# Replicape_B4.net
KiCad netlist of a schematic drawn in EAGLE
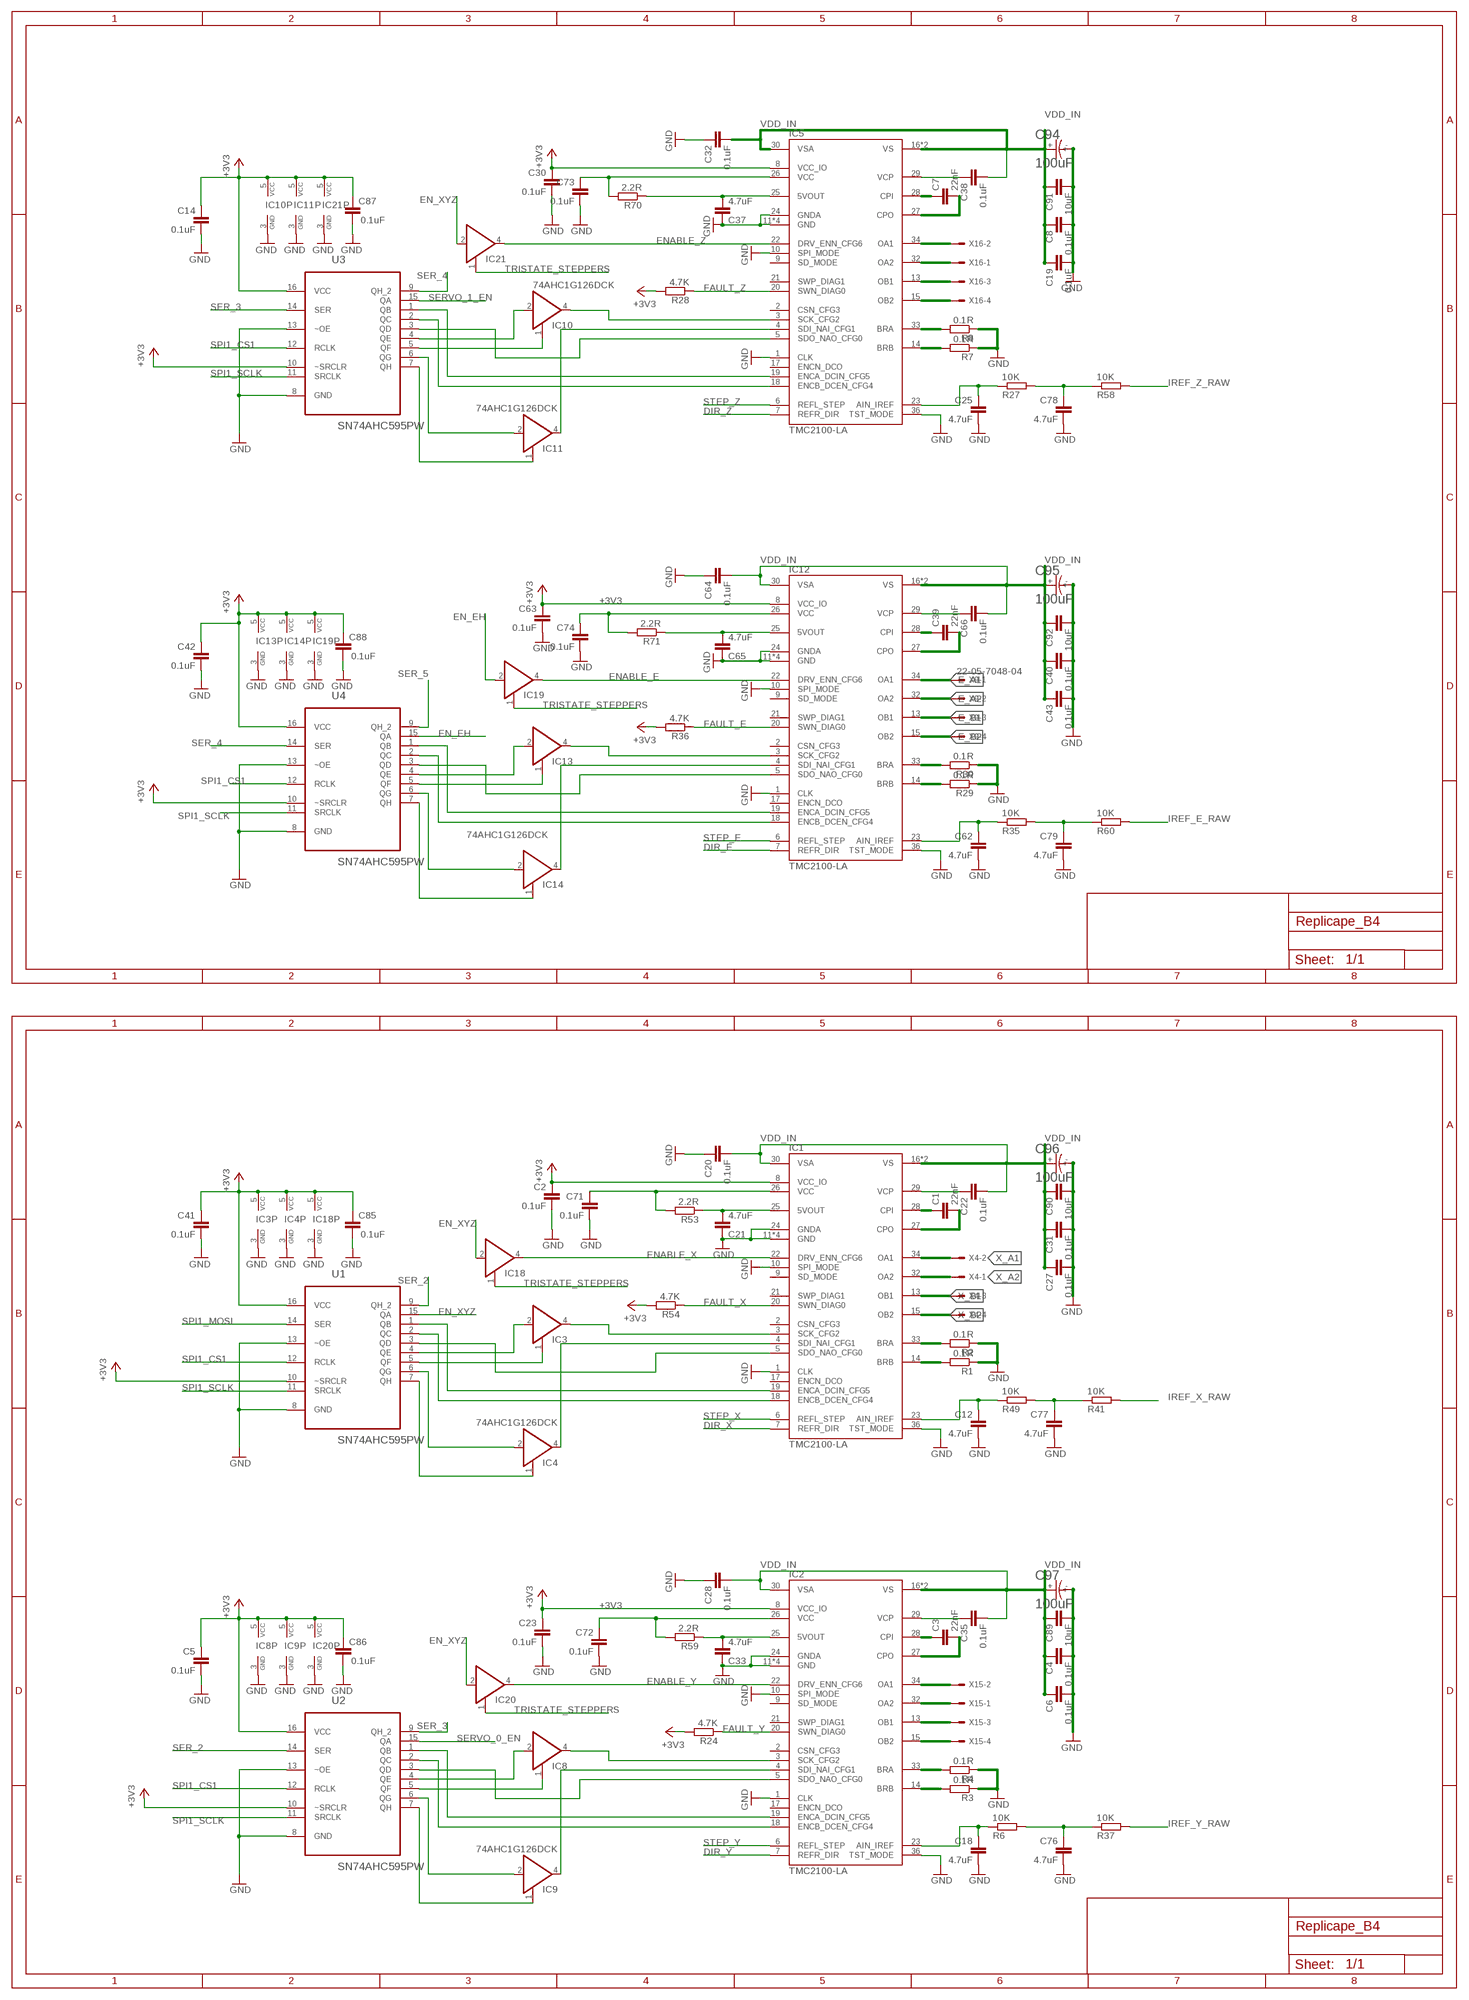
[diagram p0: schematic, sheet 1, part 1 of 3]
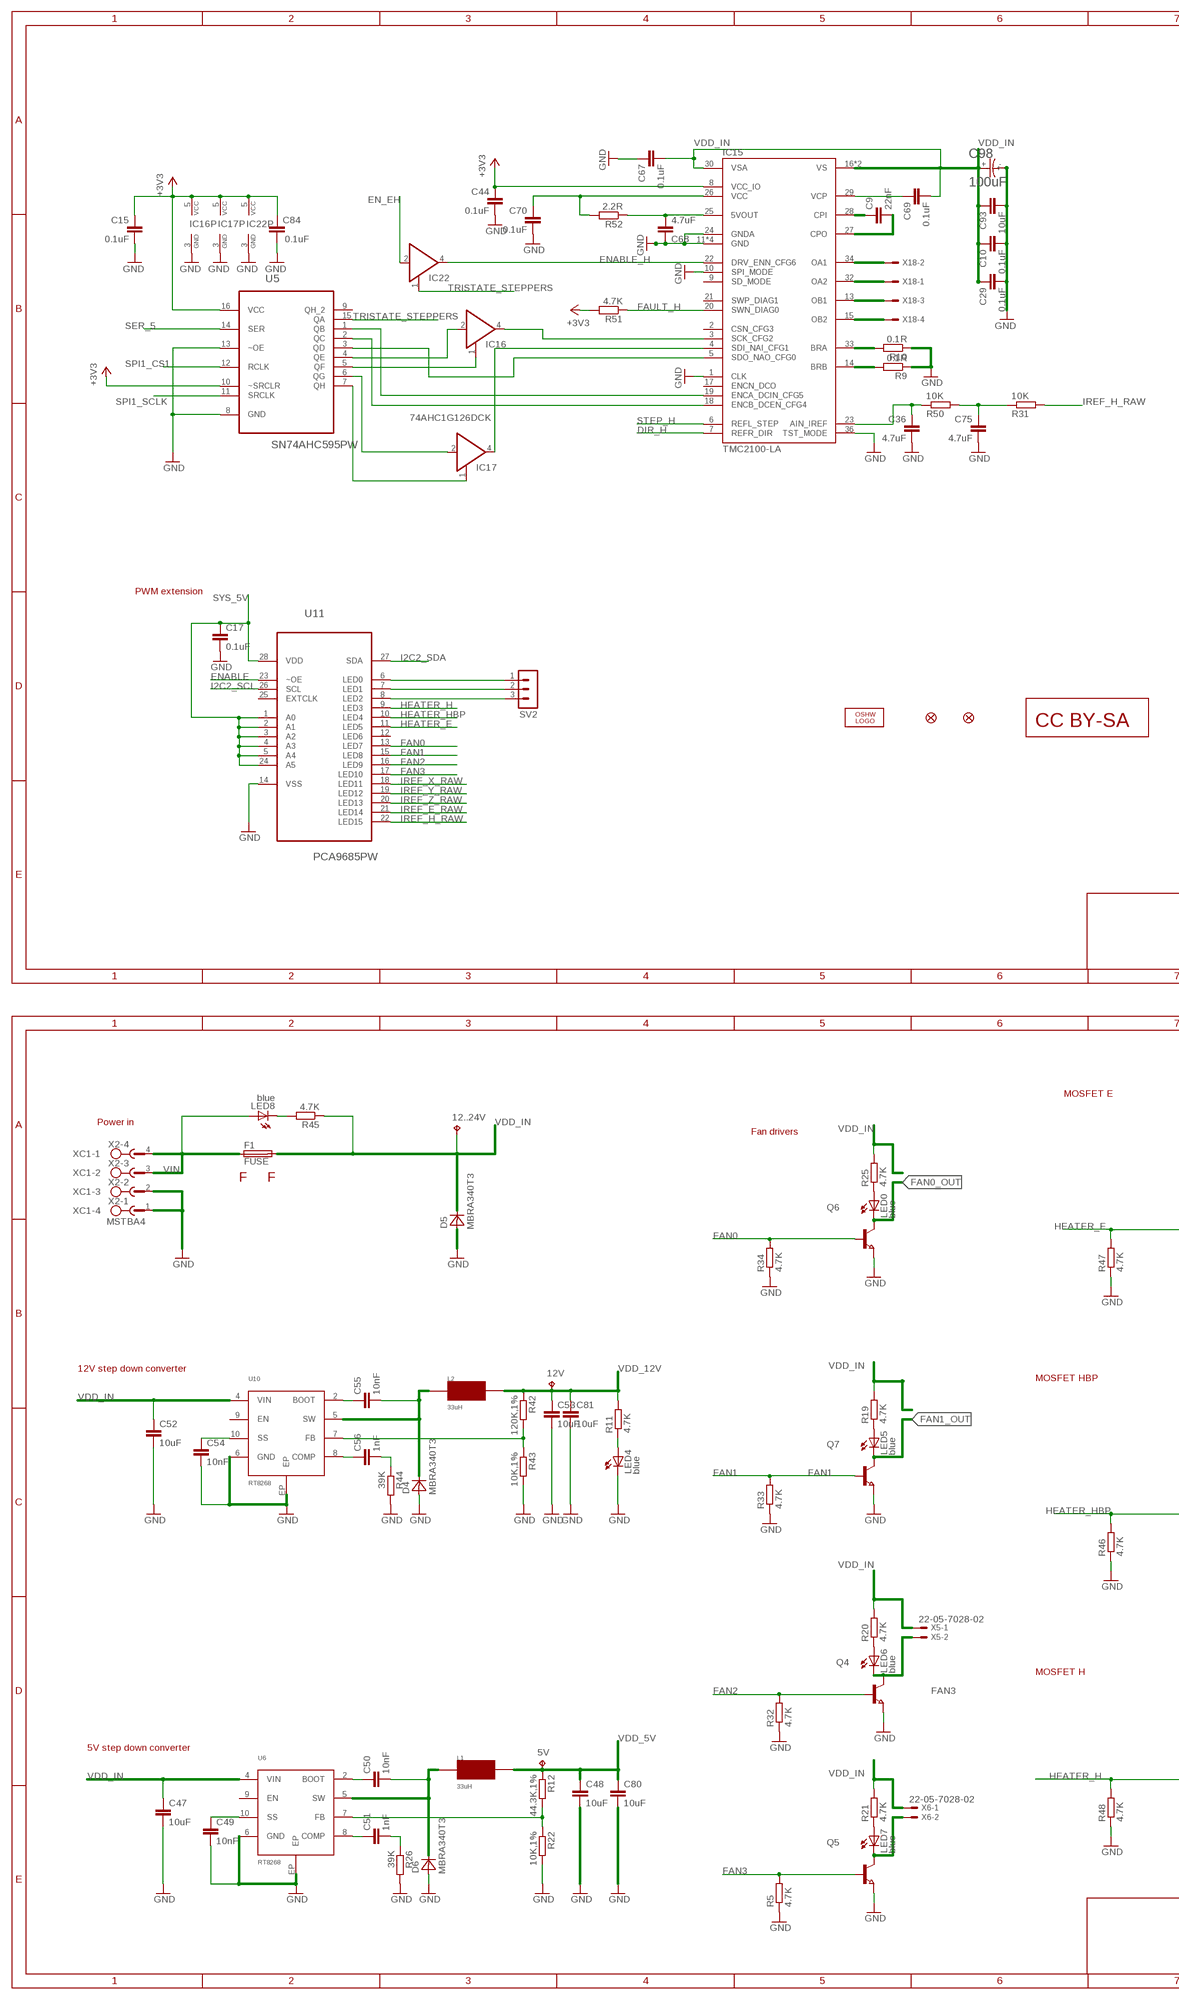
[diagram p1: schematic, sheet 1, part 2 of 3]
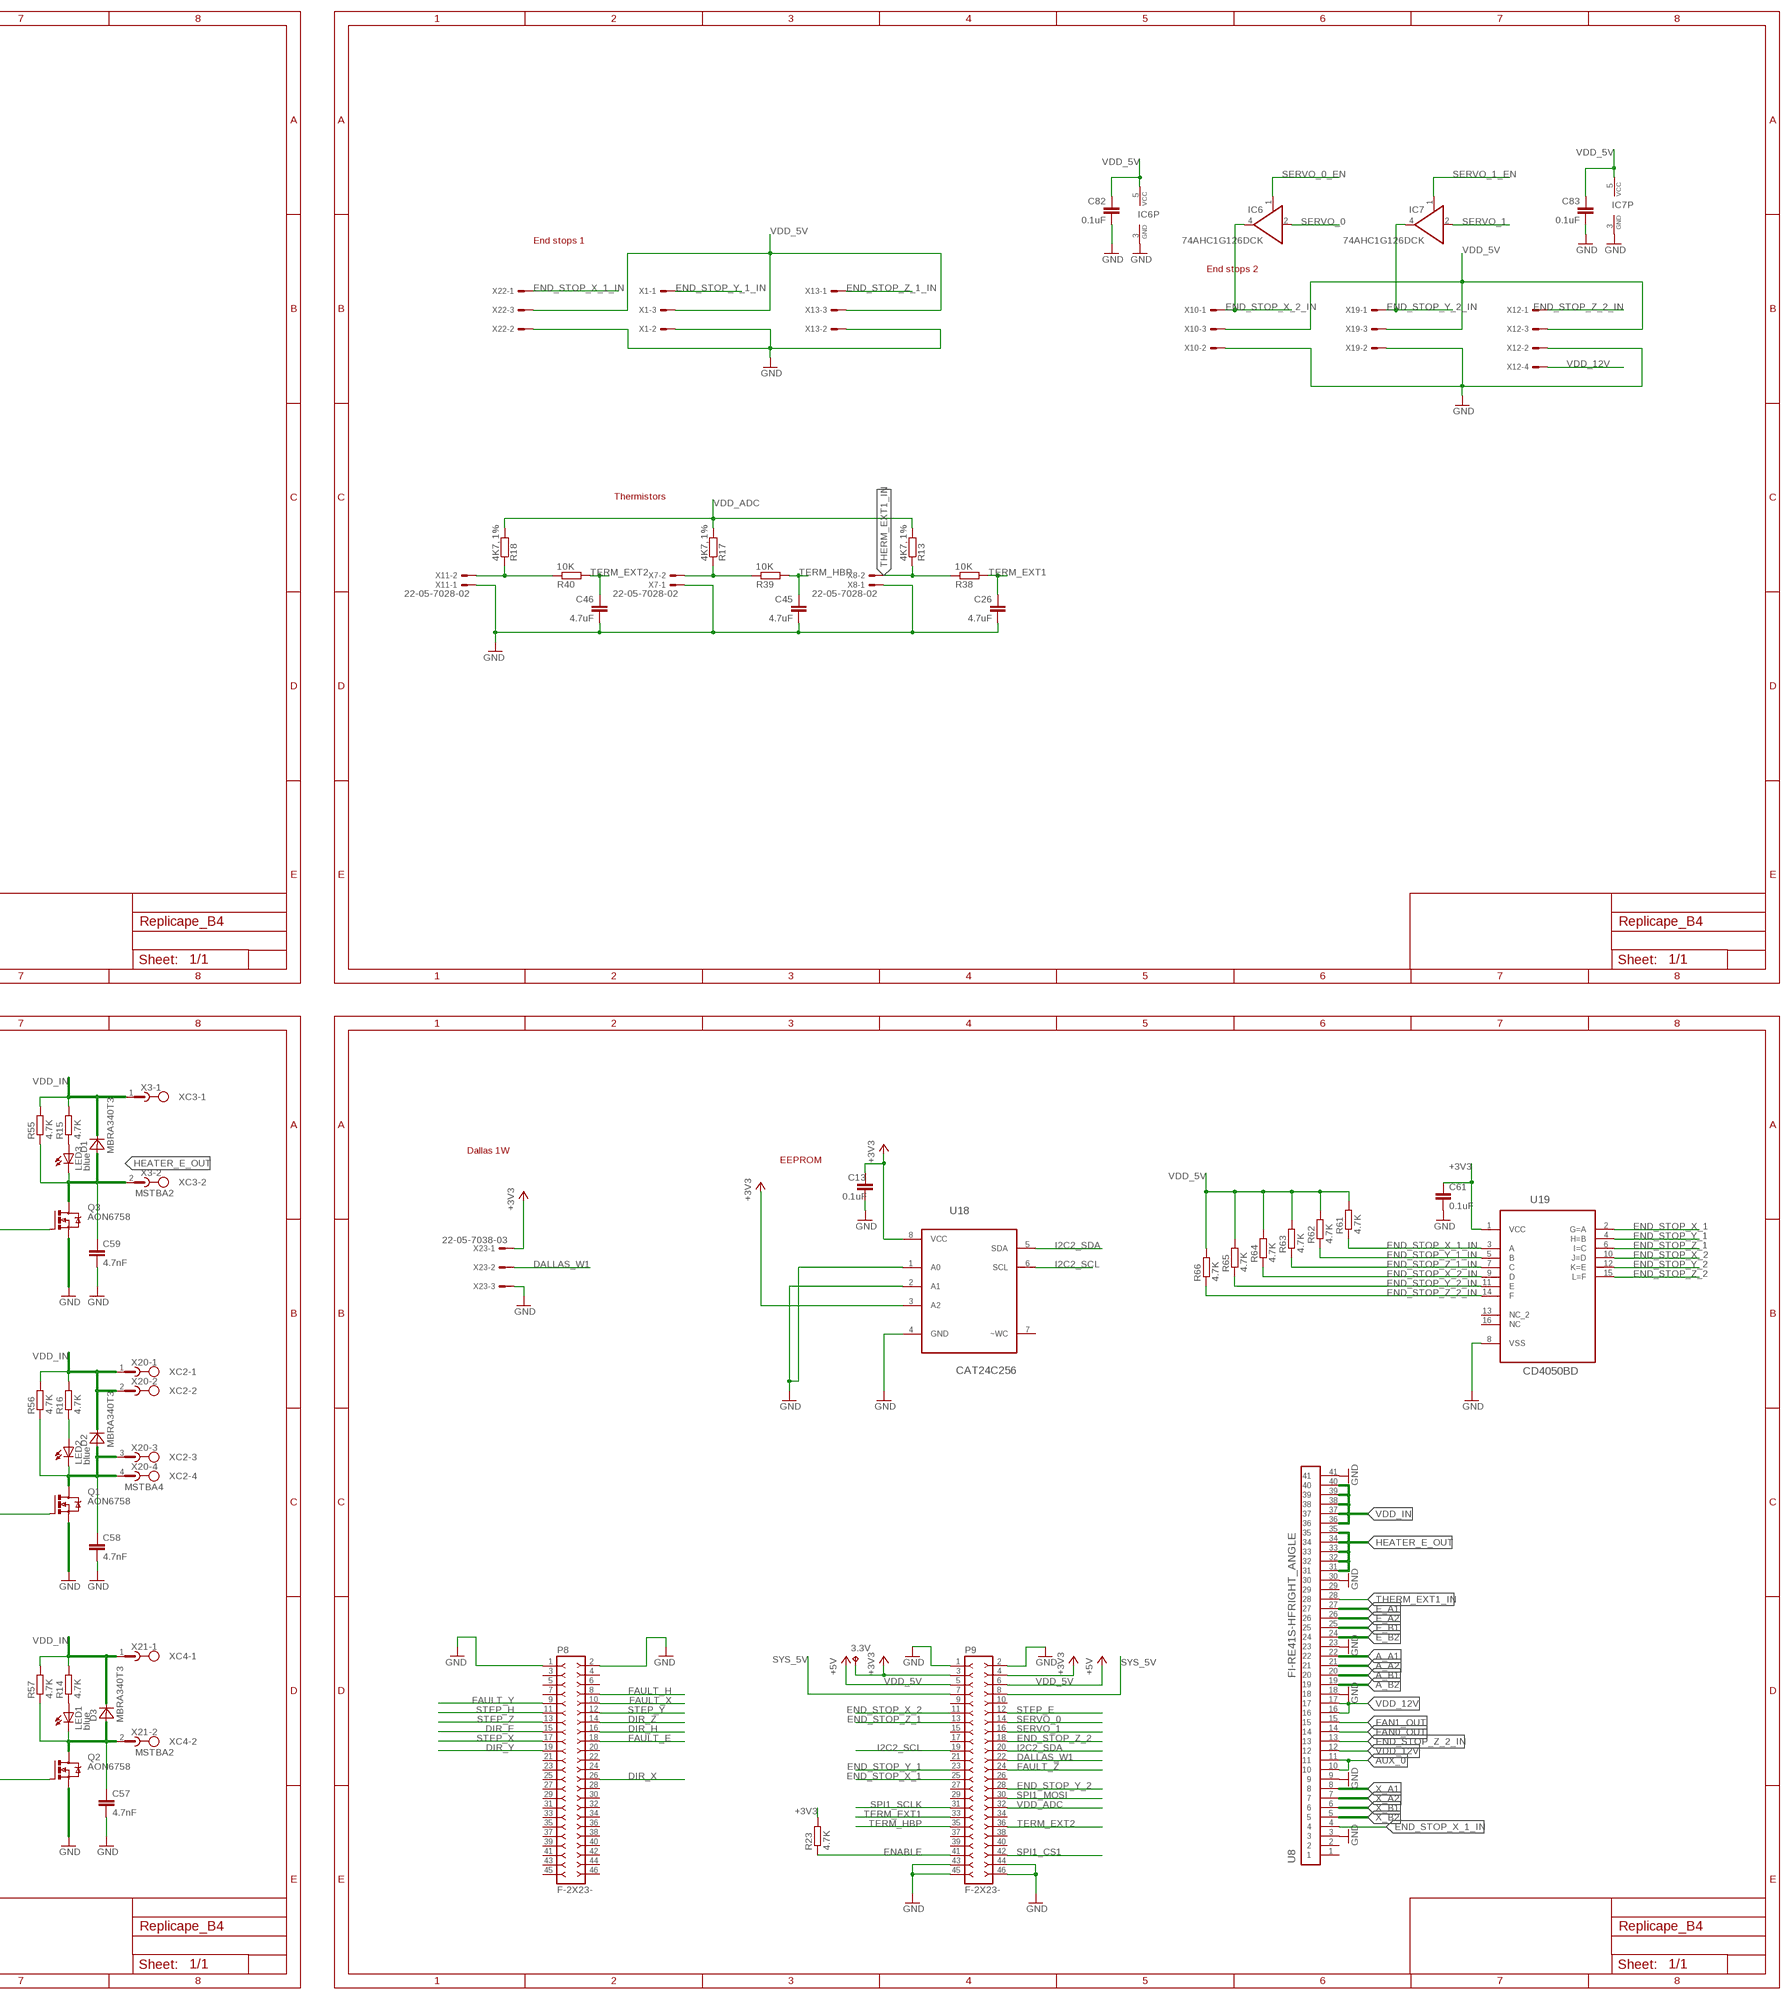
[diagram p2: schematic, sheet 1, part 3 of 3]

(export (version "E")
  (design (tool "Eeschema 10.0.6"))
  (components
    (comp (ref "3.3V")
      (value "TPB1,27")
      (footprint "eagle-import:B1,27")
      (libsource (lib "eagle-import") (part "TPB1,27"))
    )
    (comp (ref "5V")
      (value "TPB1,27")
      (footprint "eagle-import:B1,27")
      (libsource (lib "eagle-import") (part "TPB1,27"))
    )
    (comp (ref "12..24V")
      (value "TPB1,27")
      (footprint "eagle-import:B1,27")
      (libsource (lib "eagle-import") (part "TPB1,27"))
    )
    (comp (ref "12V")
      (value "TPB1,27")
      (footprint "eagle-import:B1,27")
      (libsource (lib "eagle-import") (part "TPB1,27"))
    )
    (comp (ref "C1")
      (value "22nF")
      (footprint "eagle-import:C0402")
      (fields (field (name "MPN") "C1005X7R1E223K050BB"))
      (libsource (lib "eagle-import") (part "C-EUC0402"))
    )
    (comp (ref "C2")
      (value "0.1uF")
      (footprint "eagle-import:C0402")
      (fields (field (name "MPN") "CL10B104KB8NNND"))
      (libsource (lib "eagle-import") (part "C-EUC0402"))
    )
    (comp (ref "C3")
      (value "22nF")
      (footprint "eagle-import:C0402")
      (fields (field (name "MPN") "C1005X7R1E223K050BB"))
      (libsource (lib "eagle-import") (part "C-EUC0402"))
    )
    (comp (ref "C4")
      (value "0.1uF")
      (footprint "eagle-import:C0402")
      (fields (field (name "MPN") "CL10B104KB8NNND"))
      (libsource (lib "eagle-import") (part "C-EUC0402"))
    )
    (comp (ref "C5")
      (value "0.1uF")
      (footprint "eagle-import:C0402")
      (fields (field (name "MPN") "CL10B104KB8NNND"))
      (libsource (lib "eagle-import") (part "C-EUC0402"))
    )
    (comp (ref "C6")
      (value "0.1uF")
      (footprint "eagle-import:C0402")
      (fields (field (name "MPN") "CL10B104KB8NNND"))
      (libsource (lib "eagle-import") (part "C-EUC0402"))
    )
    (comp (ref "C7")
      (value "22nF")
      (footprint "eagle-import:C0402")
      (fields (field (name "MPN") "C1005X7R1E223K050BB"))
      (libsource (lib "eagle-import") (part "C-EUC0402"))
    )
    (comp (ref "C8")
      (value "0.1uF")
      (footprint "eagle-import:C0402")
      (fields (field (name "MPN") "CL10B104KB8NNND"))
      (libsource (lib "eagle-import") (part "C-EUC0402"))
    )
    (comp (ref "C9")
      (value "22nF")
      (footprint "eagle-import:C0402")
      (fields (field (name "MPN") "C1005X7R1E223K050BB"))
      (libsource (lib "eagle-import") (part "C-EUC0402"))
    )
    (comp (ref "C10")
      (value "0.1uF")
      (footprint "eagle-import:C0402")
      (fields (field (name "MPN") "CL10B104KB8NNND"))
      (libsource (lib "eagle-import") (part "C-EUC0402"))
    )
    (comp (ref "C12")
      (value "4.7uF")
      (footprint "eagle-import:C0402")
      (fields (field (name "MPN") "GRM155R60J475ME47D"))
      (libsource (lib "eagle-import") (part "C-EUC0402"))
    )
    (comp (ref "C13")
      (value "0.1uF")
      (footprint "eagle-import:C0402")
      (fields (field (name "MPN") "CL10B104KB8NNND"))
      (libsource (lib "eagle-import") (part "C-EUC0402"))
    )
    (comp (ref "C14")
      (value "0.1uF")
      (footprint "eagle-import:C0402")
      (fields (field (name "MPN") "CL10B104KB8NNND"))
      (libsource (lib "eagle-import") (part "C-EUC0402"))
    )
    (comp (ref "C15")
      (value "0.1uF")
      (footprint "eagle-import:C0402")
      (fields (field (name "MPN") "CL10B104KB8NNND"))
      (libsource (lib "eagle-import") (part "C-EUC0402"))
    )
    (comp (ref "C17")
      (value "0.1uF")
      (footprint "eagle-import:C0402")
      (fields (field (name "MPN") "CL10B104KB8NNND"))
      (libsource (lib "eagle-import") (part "C-EUC0402"))
    )
    (comp (ref "C18")
      (value "4.7uF")
      (footprint "eagle-import:C0402")
      (fields (field (name "MPN") "GRM155R60J475ME47D"))
      (libsource (lib "eagle-import") (part "C-EUC0402"))
    )
    (comp (ref "C19")
      (value "0.1uF")
      (footprint "eagle-import:C0402")
      (fields (field (name "MPN") "CL10B104KB8NNND"))
      (libsource (lib "eagle-import") (part "C-EUC0402"))
    )
    (comp (ref "C20")
      (value "0.1uF")
      (footprint "eagle-import:C0402")
      (fields (field (name "MPN") "CL10B104KB8NNND"))
      (libsource (lib "eagle-import") (part "C-EUC0402"))
    )
    (comp (ref "C21")
      (value "4.7uF")
      (footprint "eagle-import:C0402")
      (fields (field (name "MPN") "GRM155R60J475ME47D"))
      (libsource (lib "eagle-import") (part "C-EUC0402"))
    )
    (comp (ref "C22")
      (value "0.1uF")
      (footprint "eagle-import:C0402")
      (fields (field (name "MPN") "CL10B104KB8NNND"))
      (libsource (lib "eagle-import") (part "C-EUC0402"))
    )
    (comp (ref "C23")
      (value "0.1uF")
      (footprint "eagle-import:C0402")
      (fields (field (name "MPN") "CL10B104KB8NNND"))
      (libsource (lib "eagle-import") (part "C-EUC0402"))
    )
    (comp (ref "C25")
      (value "4.7uF")
      (footprint "eagle-import:C0402")
      (fields (field (name "MPN") "GRM155R60J475ME47D"))
      (libsource (lib "eagle-import") (part "C-EUC0402"))
    )
    (comp (ref "C26")
      (value "4.7uF")
      (footprint "eagle-import:C0402")
      (fields (field (name "MPN") "GRM155R60J475ME47D"))
      (libsource (lib "eagle-import") (part "C-EUC0402"))
    )
    (comp (ref "C27")
      (value "0.1uF")
      (footprint "eagle-import:C0402")
      (fields (field (name "MPN") "CL10B104KB8NNND"))
      (libsource (lib "eagle-import") (part "C-EUC0402"))
    )
    (comp (ref "C28")
      (value "0.1uF")
      (footprint "eagle-import:C0402")
      (fields (field (name "MPN") "CL10B104KB8NNND"))
      (libsource (lib "eagle-import") (part "C-EUC0402"))
    )
    (comp (ref "C29")
      (value "0.1uF")
      (footprint "eagle-import:C0402")
      (fields (field (name "MPN") "CL10B104KB8NNND"))
      (libsource (lib "eagle-import") (part "C-EUC0402"))
    )
    (comp (ref "C30")
      (value "0.1uF")
      (footprint "eagle-import:C0402")
      (fields (field (name "MPN") "CL10B104KB8NNND"))
      (libsource (lib "eagle-import") (part "C-EUC0402"))
    )
    (comp (ref "C31")
      (value "0.1uF")
      (footprint "eagle-import:C0402")
      (fields (field (name "MPN") "CL10B104KB8NNND"))
      (libsource (lib "eagle-import") (part "C-EUC0402"))
    )
    (comp (ref "C32")
      (value "0.1uF")
      (footprint "eagle-import:C0402")
      (fields (field (name "MPN") "CL10B104KB8NNND"))
      (libsource (lib "eagle-import") (part "C-EUC0402"))
    )
    (comp (ref "C33")
      (value "4.7uF")
      (footprint "eagle-import:C0402")
      (fields (field (name "MPN") "GRM155R60J475ME47D"))
      (libsource (lib "eagle-import") (part "C-EUC0402"))
    )
    (comp (ref "C35")
      (value "0.1uF")
      (footprint "eagle-import:C0402")
      (fields (field (name "MPN") "CL10B104KB8NNND"))
      (libsource (lib "eagle-import") (part "C-EUC0402"))
    )
    (comp (ref "C36")
      (value "4.7uF")
      (footprint "eagle-import:C0402")
      (fields (field (name "MPN") "GRM155R60J475ME47D"))
      (libsource (lib "eagle-import") (part "C-EUC0402"))
    )
    (comp (ref "C37")
      (value "4.7uF")
      (footprint "eagle-import:C0402")
      (fields (field (name "MPN") "GRM155R60J475ME47D"))
      (libsource (lib "eagle-import") (part "C-EUC0402"))
    )
    (comp (ref "C38")
      (value "0.1uF")
      (footprint "eagle-import:C0402")
      (fields (field (name "MPN") "CL10B104KB8NNND"))
      (libsource (lib "eagle-import") (part "C-EUC0402"))
    )
    (comp (ref "C39")
      (value "22nF")
      (footprint "eagle-import:C0402")
      (fields (field (name "MPN") "C1005X7R1E223K050BB"))
      (libsource (lib "eagle-import") (part "C-EUC0402"))
    )
    (comp (ref "C40")
      (value "0.1uF")
      (footprint "eagle-import:C0402")
      (fields (field (name "MPN") "CL10B104KB8NNND"))
      (libsource (lib "eagle-import") (part "C-EUC0402"))
    )
    (comp (ref "C41")
      (value "0.1uF")
      (footprint "eagle-import:C0402")
      (fields (field (name "MPN") "CL10B104KB8NNND"))
      (libsource (lib "eagle-import") (part "C-EUC0402"))
    )
    (comp (ref "C42")
      (value "0.1uF")
      (footprint "eagle-import:C0402")
      (fields (field (name "MPN") "CL10B104KB8NNND"))
      (libsource (lib "eagle-import") (part "C-EUC0402"))
    )
    (comp (ref "C43")
      (value "0.1uF")
      (footprint "eagle-import:C0402")
      (fields (field (name "MPN") "CL10B104KB8NNND"))
      (libsource (lib "eagle-import") (part "C-EUC0402"))
    )
    (comp (ref "C44")
      (value "0.1uF")
      (footprint "eagle-import:C0402")
      (fields (field (name "MPN") "CL10B104KB8NNND"))
      (libsource (lib "eagle-import") (part "C-EUC0402"))
    )
    (comp (ref "C45")
      (value "4.7uF")
      (footprint "eagle-import:C0402")
      (fields (field (name "MPN") "GRM155R60J475ME47D"))
      (libsource (lib "eagle-import") (part "C-EUC0402"))
    )
    (comp (ref "C46")
      (value "4.7uF")
      (footprint "eagle-import:C0402")
      (fields (field (name "MPN") "GRM155R60J475ME47D"))
      (libsource (lib "eagle-import") (part "C-EUC0402"))
    )
    (comp (ref "C47")
      (value "10uF")
      (footprint "eagle-import:C1206")
      (fields (field (name "MPN") "CL31B106KAHNNNE"))
      (libsource (lib "eagle-import") (part "C-EUC1206"))
    )
    (comp (ref "C48")
      (value "10uF")
      (footprint "eagle-import:C1206")
      (fields (field (name "MPN") "CL31B106KAHNNNE"))
      (libsource (lib "eagle-import") (part "C-EUC1206"))
    )
    (comp (ref "C49")
      (value "10nF")
      (footprint "eagle-import:C0402")
      (fields (field (name "MPN") "CL05B103KB5NNNC"))
      (libsource (lib "eagle-import") (part "C-EUC0402"))
    )
    (comp (ref "C50")
      (value "10nF")
      (footprint "eagle-import:C0402")
      (fields (field (name "MPN") "CL05B103KB5NNNC"))
      (libsource (lib "eagle-import") (part "C-EUC0402"))
    )
    (comp (ref "C51")
      (value "1nF")
      (footprint "eagle-import:C0402")
      (fields (field (name "MPN") "C1005X7R1H102K050BA"))
      (libsource (lib "eagle-import") (part "C-EUC0402"))
    )
    (comp (ref "C52")
      (value "10uF")
      (footprint "eagle-import:C1206")
      (fields (field (name "MPN") "CL31B106KAHNNNE"))
      (libsource (lib "eagle-import") (part "C-EUC1206"))
    )
    (comp (ref "C53")
      (value "10uF")
      (footprint "eagle-import:C1206")
      (fields (field (name "MPN") "CL31B106KAHNNNE"))
      (libsource (lib "eagle-import") (part "C-EUC1206"))
    )
    (comp (ref "C54")
      (value "10nF")
      (footprint "eagle-import:C0402")
      (fields (field (name "MPN") "CL05B103KB5NNNC"))
      (libsource (lib "eagle-import") (part "C-EUC0402"))
    )
    (comp (ref "C55")
      (value "10nF")
      (footprint "eagle-import:C0402")
      (fields (field (name "MPN") "CL05B103KB5NNNC"))
      (libsource (lib "eagle-import") (part "C-EUC0402"))
    )
    (comp (ref "C56")
      (value "1nF")
      (footprint "eagle-import:C0402")
      (fields (field (name "MPN") "C1005X7R1H102K050BA"))
      (libsource (lib "eagle-import") (part "C-EUC0402"))
    )
    (comp (ref "C57")
      (value "4.7nF")
      (footprint "eagle-import:C0402")
      (fields (field (name "MPN") "CL05B472KA5NNNC"))
      (libsource (lib "eagle-import") (part "C-EUC0402"))
    )
    (comp (ref "C58")
      (value "4.7nF")
      (footprint "eagle-import:C0402")
      (fields (field (name "MPN") "CL05B472KA5NNNC"))
      (libsource (lib "eagle-import") (part "C-EUC0402"))
    )
    (comp (ref "C59")
      (value "4.7nF")
      (footprint "eagle-import:C0402")
      (fields (field (name "MPN") "CL05B472KA5NNNC"))
      (libsource (lib "eagle-import") (part "C-EUC0402"))
    )
    (comp (ref "C61")
      (value "0.1uF")
      (footprint "eagle-import:C0402")
      (fields (field (name "MPN") "CL10B104KB8NNND"))
      (libsource (lib "eagle-import") (part "C-EUC0402"))
    )
    (comp (ref "C62")
      (value "4.7uF")
      (footprint "eagle-import:C0402")
      (fields (field (name "MPN") "GRM155R60J475ME47D"))
      (libsource (lib "eagle-import") (part "C-EUC0402"))
    )
    (comp (ref "C63")
      (value "0.1uF")
      (footprint "eagle-import:C0402")
      (fields (field (name "MPN") "CL10B104KB8NNND"))
      (libsource (lib "eagle-import") (part "C-EUC0402"))
    )
    (comp (ref "C64")
      (value "0.1uF")
      (footprint "eagle-import:C0402")
      (fields (field (name "MPN") "CL10B104KB8NNND"))
      (libsource (lib "eagle-import") (part "C-EUC0402"))
    )
    (comp (ref "C65")
      (value "4.7uF")
      (footprint "eagle-import:C0402")
      (fields (field (name "MPN") "GRM155R60J475ME47D"))
      (libsource (lib "eagle-import") (part "C-EUC0402"))
    )
    (comp (ref "C66")
      (value "0.1uF")
      (footprint "eagle-import:C0402")
      (fields (field (name "MPN") "CL10B104KB8NNND"))
      (libsource (lib "eagle-import") (part "C-EUC0402"))
    )
    (comp (ref "C67")
      (value "0.1uF")
      (footprint "eagle-import:C0402")
      (fields (field (name "MPN") "CL10B104KB8NNND"))
      (libsource (lib "eagle-import") (part "C-EUC0402"))
    )
    (comp (ref "C68")
      (value "4.7uF")
      (footprint "eagle-import:C0402")
      (fields (field (name "MPN") "GRM155R60J475ME47D"))
      (libsource (lib "eagle-import") (part "C-EUC0402"))
    )
    (comp (ref "C69")
      (value "0.1uF")
      (footprint "eagle-import:C0402")
      (fields (field (name "MPN") "CL10B104KB8NNND"))
      (libsource (lib "eagle-import") (part "C-EUC0402"))
    )
    (comp (ref "C70")
      (value "0.1uF")
      (footprint "eagle-import:C0402")
      (fields (field (name "MPN") "CL10B104KB8NNND"))
      (libsource (lib "eagle-import") (part "C-EUC0402"))
    )
    (comp (ref "C71")
      (value "0.1uF")
      (footprint "eagle-import:C0402")
      (fields (field (name "MPN") "CL10B104KB8NNND"))
      (libsource (lib "eagle-import") (part "C-EUC0402"))
    )
    (comp (ref "C72")
      (value "0.1uF")
      (footprint "eagle-import:C0402")
      (fields (field (name "MPN") "CL10B104KB8NNND"))
      (libsource (lib "eagle-import") (part "C-EUC0402"))
    )
    (comp (ref "C73")
      (value "0.1uF")
      (footprint "eagle-import:C0402")
      (fields (field (name "MPN") "CL10B104KB8NNND"))
      (libsource (lib "eagle-import") (part "C-EUC0402"))
    )
    (comp (ref "C74")
      (value "0.1uF")
      (footprint "eagle-import:C0402")
      (fields (field (name "MPN") "CL10B104KB8NNND"))
      (libsource (lib "eagle-import") (part "C-EUC0402"))
    )
    (comp (ref "C75")
      (value "4.7uF")
      (footprint "eagle-import:C0402")
      (fields (field (name "MPN") "GRM155R60J475ME47D"))
      (libsource (lib "eagle-import") (part "C-EUC0402"))
    )
    (comp (ref "C76")
      (value "4.7uF")
      (footprint "eagle-import:C0402")
      (fields (field (name "MPN") "GRM155R60J475ME47D"))
      (libsource (lib "eagle-import") (part "C-EUC0402"))
    )
    (comp (ref "C77")
      (value "4.7uF")
      (footprint "eagle-import:C0402")
      (fields (field (name "MPN") "GRM155R60J475ME47D"))
      (libsource (lib "eagle-import") (part "C-EUC0402"))
    )
    (comp (ref "C78")
      (value "4.7uF")
      (footprint "eagle-import:C0402")
      (fields (field (name "MPN") "GRM155R60J475ME47D"))
      (libsource (lib "eagle-import") (part "C-EUC0402"))
    )
    (comp (ref "C79")
      (value "4.7uF")
      (footprint "eagle-import:C0402")
      (fields (field (name "MPN") "GRM155R60J475ME47D"))
      (libsource (lib "eagle-import") (part "C-EUC0402"))
    )
    (comp (ref "C80")
      (value "10uF")
      (footprint "eagle-import:C1206")
      (fields (field (name "MPN") "CL31B106KAHNNNE"))
      (libsource (lib "eagle-import") (part "C-EUC1206"))
    )
    (comp (ref "C81")
      (value "10uF")
      (footprint "eagle-import:C1206")
      (fields (field (name "MPN") "CL31B106KAHNNNE"))
      (libsource (lib "eagle-import") (part "C-EUC1206"))
    )
    (comp (ref "C82")
      (value "0.1uF")
      (footprint "eagle-import:C0402")
      (fields (field (name "MPN") "CL10B104KB8NNND"))
      (libsource (lib "eagle-import") (part "C-EUC0402"))
    )
    (comp (ref "C83")
      (value "0.1uF")
      (footprint "eagle-import:C0402")
      (fields (field (name "MPN") "CL10B104KB8NNND"))
      (libsource (lib "eagle-import") (part "C-EUC0402"))
    )
    (comp (ref "C84")
      (value "0.1uF")
      (footprint "eagle-import:C0402")
      (fields (field (name "MPN") "CL10B104KB8NNND"))
      (libsource (lib "eagle-import") (part "C-EUC0402"))
    )
    (comp (ref "C85")
      (value "0.1uF")
      (footprint "eagle-import:C0402")
      (fields (field (name "MPN") "CL10B104KB8NNND"))
      (libsource (lib "eagle-import") (part "C-EUC0402"))
    )
    (comp (ref "C86")
      (value "0.1uF")
      (footprint "eagle-import:C0402")
      (fields (field (name "MPN") "CL10B104KB8NNND"))
      (libsource (lib "eagle-import") (part "C-EUC0402"))
    )
    (comp (ref "C87")
      (value "0.1uF")
      (footprint "eagle-import:C0402")
      (fields (field (name "MPN") "CL10B104KB8NNND"))
      (libsource (lib "eagle-import") (part "C-EUC0402"))
    )
    (comp (ref "C88")
      (value "0.1uF")
      (footprint "eagle-import:C0402")
      (fields (field (name "MPN") "CL10B104KB8NNND"))
      (libsource (lib "eagle-import") (part "C-EUC0402"))
    )
    (comp (ref "C89")
      (value "10uF")
      (footprint "eagle-import:C0805")
      (fields (field (name "MPN") "C2012X5R1V106M085AC"))
      (libsource (lib "eagle-import") (part "C-EUC0805"))
    )
    (comp (ref "C90")
      (value "10uF")
      (footprint "eagle-import:C0805")
      (fields (field (name "MPN") "C2012X5R1V106M085AC"))
      (libsource (lib "eagle-import") (part "C-EUC0805"))
    )
    (comp (ref "C91")
      (value "10uF")
      (footprint "eagle-import:C0805")
      (fields (field (name "MPN") "C2012X5R1V106M085AC"))
      (libsource (lib "eagle-import") (part "C-EUC0805"))
    )
    (comp (ref "C92")
      (value "10uF")
      (footprint "eagle-import:C0805")
      (fields (field (name "MPN") "C2012X5R1V106M085AC"))
      (libsource (lib "eagle-import") (part "C-EUC0805"))
    )
    (comp (ref "C93")
      (value "10uF")
      (footprint "eagle-import:C0805")
      (fields (field (name "MPN") "C2012X5R1V106M085AC"))
      (libsource (lib "eagle-import") (part "C-EUC0805"))
    )
    (comp (ref "C94")
      (value "100uF")
      (footprint "eagle-import:RHS1V10MCN1GS")
      (fields (field (name "MPN") "RHS1V101MCN1GS"))
      (libsource (lib "eagle-import") (part "C"))
    )
    (comp (ref "C95")
      (value "100uF")
      (footprint "eagle-import:RHS1V10MCN1GS")
      (fields (field (name "MPN") "RHS1V101MCN1GS"))
      (libsource (lib "eagle-import") (part "C"))
    )
    (comp (ref "C96")
      (value "100uF")
      (footprint "eagle-import:RHS1V10MCN1GS")
      (fields (field (name "MPN") "RHS1V101MCN1GS"))
      (libsource (lib "eagle-import") (part "C"))
    )
    (comp (ref "C97")
      (value "100uF")
      (footprint "eagle-import:RHS1V10MCN1GS")
      (fields (field (name "MPN") "RHS1V101MCN1GS"))
      (libsource (lib "eagle-import") (part "C"))
    )
    (comp (ref "C98")
      (value "100uF")
      (footprint "eagle-import:RHS1V10MCN1GS")
      (fields (field (name "MPN") "RHS1V101MCN1GS"))
      (libsource (lib "eagle-import") (part "C"))
    )
    (comp (ref "D1")
      (value "MBRA340T3")
      (footprint "eagle-import:SMA")
      (fields (field (name "MPN") "MBRA340T3G"))
      (libsource (lib "eagle-import") (part "MBRA340T3"))
    )
    (comp (ref "D2")
      (value "MBRA340T3")
      (footprint "eagle-import:SMA")
      (fields (field (name "MPN") "MBRA340T3G"))
      (libsource (lib "eagle-import") (part "MBRA340T3"))
    )
    (comp (ref "D3")
      (value "MBRA340T3")
      (footprint "eagle-import:SMA")
      (fields (field (name "MPN") "MBRA340T3G"))
      (libsource (lib "eagle-import") (part "MBRA340T3"))
    )
    (comp (ref "D4")
      (value "MBRA340T3")
      (footprint "eagle-import:SMA")
      (fields (field (name "MPN") "MBRA340T3G"))
      (libsource (lib "eagle-import") (part "MBRA340T3"))
    )
    (comp (ref "D5")
      (value "MBRA340T3")
      (footprint "eagle-import:SMA")
      (fields (field (name "MPN") "MBRA340T3G"))
      (libsource (lib "eagle-import") (part "MBRA340T3"))
    )
    (comp (ref "D6")
      (value "MBRA340T3")
      (footprint "eagle-import:SMA")
      (fields (field (name "MPN") "MBRA340T3G"))
      (libsource (lib "eagle-import") (part "MBRA340T3"))
    )
    (comp (ref "F1")
      (value "FUSE")
      (footprint "eagle-import:3557")
      (fields (field (name "MPN") "0891020.NXS"))
      (libsource (lib "eagle-import") (part "FUSE"))
    )
    (comp (ref "FH1")
      (value "FUSE-HOLDER")
      (footprint "eagle-import:FUSE-HOLDER")
      (fields (field (name "MPN") "3557"))
      (libsource (lib "eagle-import") (part "FUSE-HOLDER"))
    )
    (comp (ref "FH2")
      (value "FUSE-HOLDER")
      (footprint "eagle-import:FUSE-HOLDER")
      (fields (field (name "MPN") "3557"))
      (libsource (lib "eagle-import") (part "FUSE-HOLDER"))
    )
    (comp (ref "IC1")
      (value "TMC2100-LA")
      (footprint "eagle-import:QFN36-PAD")
      (fields (field (name "MPN") "TMC2100-LA-T"))
      (libsource (lib "eagle-import") (part "TMC2100-LA"))
    )
    (comp (ref "IC2")
      (value "TMC2100-LA")
      (footprint "eagle-import:QFN36-PAD")
      (fields (field (name "MPN") "TMC2100-LA-T"))
      (libsource (lib "eagle-import") (part "TMC2100-LA"))
    )
    (comp (ref "IC3")
      (value "74AHC1G126DCK")
      (footprint "eagle-import:SC70-5")
      (fields (field (name "MPN") "M74VHC1GT126DF1G"))
      (libsource (lib "eagle-import") (part "741G126DCKAHC"))
    )
    (comp (ref "IC4")
      (value "74AHC1G126DCK")
      (footprint "eagle-import:SC70-5")
      (fields (field (name "MPN") "M74VHC1GT126DF1G"))
      (libsource (lib "eagle-import") (part "741G126DCKAHC"))
    )
    (comp (ref "IC5")
      (value "TMC2100-LA")
      (footprint "eagle-import:QFN36-PAD")
      (fields (field (name "MPN") "TMC2100-LA-T"))
      (libsource (lib "eagle-import") (part "TMC2100-LA"))
    )
    (comp (ref "IC6")
      (value "74AHC1G126DCK")
      (footprint "eagle-import:SC70-5")
      (fields (field (name "MPN") "M74VHC1GT126DF1G"))
      (libsource (lib "eagle-import") (part "741G126DCKAHC"))
    )
    (comp (ref "IC7")
      (value "74AHC1G126DCK")
      (footprint "eagle-import:SC70-5")
      (fields (field (name "MPN") "M74VHC1GT126DF1G"))
      (libsource (lib "eagle-import") (part "741G126DCKAHC"))
    )
    (comp (ref "IC8")
      (value "74AHC1G126DCK")
      (footprint "eagle-import:SC70-5")
      (fields (field (name "MPN") "M74VHC1GT126DF1G"))
      (libsource (lib "eagle-import") (part "741G126DCKAHC"))
    )
    (comp (ref "IC9")
      (value "74AHC1G126DCK")
      (footprint "eagle-import:SC70-5")
      (fields (field (name "MPN") "M74VHC1GT126DF1G"))
      (libsource (lib "eagle-import") (part "741G126DCKAHC"))
    )
    (comp (ref "IC10")
      (value "74AHC1G126DCK")
      (footprint "eagle-import:SC70-5")
      (fields (field (name "MPN") "M74VHC1GT126DF1G"))
      (libsource (lib "eagle-import") (part "741G126DCKAHC"))
    )
    (comp (ref "IC11")
      (value "74AHC1G126DCK")
      (footprint "eagle-import:SC70-5")
      (fields (field (name "MPN") "M74VHC1GT126DF1G"))
      (libsource (lib "eagle-import") (part "741G126DCKAHC"))
    )
    (comp (ref "IC12")
      (value "TMC2100-LA")
      (footprint "eagle-import:QFN36-PAD")
      (fields (field (name "MPN") "TMC2100-LA-T"))
      (libsource (lib "eagle-import") (part "TMC2100-LA"))
    )
    (comp (ref "IC13")
      (value "74AHC1G126DCK")
      (footprint "eagle-import:SC70-5")
      (fields (field (name "MPN") "M74VHC1GT126DF1G"))
      (libsource (lib "eagle-import") (part "741G126DCKAHC"))
    )
    (comp (ref "IC14")
      (value "74AHC1G126DCK")
      (footprint "eagle-import:SC70-5")
      (fields (field (name "MPN") "M74VHC1GT126DF1G"))
      (libsource (lib "eagle-import") (part "741G126DCKAHC"))
    )
    (comp (ref "IC15")
      (value "TMC2100-LA")
      (footprint "eagle-import:QFN36-PAD")
      (fields (field (name "MPN") "TMC2100-LA-T"))
      (libsource (lib "eagle-import") (part "TMC2100-LA"))
    )
    (comp (ref "IC16")
      (value "74AHC1G126DCK")
      (footprint "eagle-import:SC70-5")
      (fields (field (name "MPN") "M74VHC1GT126DF1G"))
      (libsource (lib "eagle-import") (part "741G126DCKAHC"))
    )
    (comp (ref "IC17")
      (value "74AHC1G126DCK")
      (footprint "eagle-import:SC70-5")
      (fields (field (name "MPN") "M74VHC1GT126DF1G"))
      (libsource (lib "eagle-import") (part "741G126DCKAHC"))
    )
    (comp (ref "IC18")
      (value "74AHC1G126DCK")
      (footprint "eagle-import:SC70-5")
      (fields (field (name "MPN") "M74VHC1GT126DF1G"))
      (libsource (lib "eagle-import") (part "741G126DCKAHC"))
    )
    (comp (ref "IC19")
      (value "74AHC1G126DCK")
      (footprint "eagle-import:SC70-5")
      (fields (field (name "MPN") "M74VHC1GT126DF1G"))
      (libsource (lib "eagle-import") (part "741G126DCKAHC"))
    )
    (comp (ref "IC20")
      (value "74AHC1G126DCK")
      (footprint "eagle-import:SC70-5")
      (fields (field (name "MPN") "M74VHC1GT126DF1G"))
      (libsource (lib "eagle-import") (part "741G126DCKAHC"))
    )
    (comp (ref "IC21")
      (value "74AHC1G126DCK")
      (footprint "eagle-import:SC70-5")
      (fields (field (name "MPN") "M74VHC1GT126DF1G"))
      (libsource (lib "eagle-import") (part "741G126DCKAHC"))
    )
    (comp (ref "IC22")
      (value "74AHC1G126DCK")
      (footprint "eagle-import:SC70-5")
      (fields (field (name "MPN") "M74VHC1GT126DF1G"))
      (libsource (lib "eagle-import") (part "741G126DCKAHC"))
    )
    (comp (ref "JP1")
      (value "FIDUCIAL1X2.5")
      (footprint "eagle-import:FIDUCIAL-1X2.5")
      (libsource (lib "eagle-import") (part "FIDUCIAL1X2.5"))
    )
    (comp (ref "JP2")
      (value "FIDUCIAL1X2.5")
      (footprint "eagle-import:FIDUCIAL-1X2.5")
      (libsource (lib "eagle-import") (part "FIDUCIAL1X2.5"))
    )
    (comp (ref "L1")
      (value "33uH")
      (footprint "eagle-import:NR8040T330")
      (fields (field (name "MPN") "NR8040T330M"))
      (libsource (lib "eagle-import") (part "RT8040T330"))
    )
    (comp (ref "L2")
      (value "33uH")
      (footprint "eagle-import:NR8040T330")
      (fields (field (name "MPN") "NR8040T330M"))
      (libsource (lib "eagle-import") (part "RT8040T330"))
    )
    (comp (ref "LED0")
      (value "blue")
      (footprint "eagle-import:CHIP-LED0603")
      (fields (field (name "MPN") "Q65110A7211"))
      (libsource (lib "eagle-import") (part "LEDCHIP-LED0603"))
    )
    (comp (ref "LED1")
      (value "blue")
      (footprint "eagle-import:CHIP-LED0603")
      (fields (field (name "MPN") "Q65110A7211"))
      (libsource (lib "eagle-import") (part "LEDCHIP-LED0603"))
    )
    (comp (ref "LED2")
      (value "blue")
      (footprint "eagle-import:CHIP-LED0603")
      (fields (field (name "MPN") "Q65110A7211"))
      (libsource (lib "eagle-import") (part "LEDCHIP-LED0603"))
    )
    (comp (ref "LED3")
      (value "blue")
      (footprint "eagle-import:CHIP-LED0603")
      (fields (field (name "MPN") "Q65110A7211"))
      (libsource (lib "eagle-import") (part "LEDCHIP-LED0603"))
    )
    (comp (ref "LED4")
      (value "blue")
      (footprint "eagle-import:CHIP-LED0603")
      (fields (field (name "MPN") "Q65110A7211"))
      (libsource (lib "eagle-import") (part "LEDCHIP-LED0603"))
    )
    (comp (ref "LED5")
      (value "blue")
      (footprint "eagle-import:CHIP-LED0603")
      (fields (field (name "MPN") "Q65110A7211"))
      (libsource (lib "eagle-import") (part "LEDCHIP-LED0603"))
    )
    (comp (ref "LED6")
      (value "blue")
      (footprint "eagle-import:CHIP-LED0603")
      (fields (field (name "MPN") "Q65110A7211"))
      (libsource (lib "eagle-import") (part "LEDCHIP-LED0603"))
    )
    (comp (ref "LED7")
      (value "blue")
      (footprint "eagle-import:CHIP-LED0603")
      (fields (field (name "MPN") "Q65110A7211"))
      (libsource (lib "eagle-import") (part "LEDCHIP-LED0603"))
    )
    (comp (ref "LED8")
      (value "blue")
      (footprint "eagle-import:CHIP-LED0603")
      (fields (field (name "MPN") "Q65110A7211"))
      (libsource (lib "eagle-import") (part "LEDCHIP-LED0603"))
    )
    (comp (ref "LOGO1")
      (value "OSHW_LOGO_FILLX0200-NT")
      (footprint "eagle-import:OSHW_FILLX200_NOTEXT")
      (libsource (lib "eagle-import") (part "OSHW_LOGO_FILLX0200-NT"))
    )
    (comp (ref "P8")
      (value "F-2X23-")
      (footprint "eagle-import:DIL-100-2X23")
      (fields (field (name "MPN") "SSHQ-123-D-08-F-LF"))
      (libsource (lib "eagle-import") (part "F-2X23-"))
    )
    (comp (ref "P9")
      (value "F-2X23-")
      (footprint "eagle-import:DIL-100-2X23")
      (fields (field (name "MPN") "SSHQ-123-D-08-F-LF"))
      (libsource (lib "eagle-import") (part "F-2X23-"))
    )
    (comp (ref "Q1")
      (value "AON6758")
      (footprint "eagle-import:8-DFN-EP-(5X6)")
      (fields (field (name "MPN") "SIRA34DP-T1-GE3"))
      (libsource (lib "eagle-import") (part "AON6758"))
    )
    (comp (ref "Q2")
      (value "AON6758")
      (footprint "eagle-import:8-DFN-EP-(5X6)")
      (fields (field (name "MPN") "SIRA34DP-T1-GE3"))
      (libsource (lib "eagle-import") (part "AON6758"))
    )
    (comp (ref "Q3")
      (value "AON6758")
      (footprint "eagle-import:8-DFN-EP-(5X6)")
      (fields (field (name "MPN") "SIRA34DP-T1-GE3"))
      (libsource (lib "eagle-import") (part "AON6758"))
    )
    (comp (ref "Q4")
      (value "NPN-TRANSISTOR_SOT23")
      (footprint "eagle-import:SOT23")
      (fields (field (name "MPN") "AO7400"))
      (libsource (lib "eagle-import") (part "NPN-TRANSISTOR_SOT23"))
    )
    (comp (ref "Q5")
      (value "NPN-TRANSISTOR_SOT23")
      (footprint "eagle-import:SOT23")
      (fields (field (name "MPN") "AO7400"))
      (libsource (lib "eagle-import") (part "NPN-TRANSISTOR_SOT23"))
    )
    (comp (ref "Q6")
      (value "NPN-TRANSISTOR_SOT23")
      (footprint "eagle-import:SOT23")
      (fields (field (name "MPN") "AO7400"))
      (libsource (lib "eagle-import") (part "NPN-TRANSISTOR_SOT23"))
    )
    (comp (ref "Q7")
      (value "NPN-TRANSISTOR_SOT23")
      (footprint "eagle-import:SOT23")
      (fields (field (name "MPN") "AO7400"))
      (libsource (lib "eagle-import") (part "NPN-TRANSISTOR_SOT23"))
    )
    (comp (ref "R1")
      (value "0.1R")
      (footprint "eagle-import:R0805")
      (fields (field (name "MPN") "RL1220S-R10-F"))
      (libsource (lib "eagle-import") (part "R-EU_R0805"))
    )
    (comp (ref "R2")
      (value "0.1R")
      (footprint "eagle-import:R0805")
      (fields (field (name "MPN") "RL1220S-R10-F"))
      (libsource (lib "eagle-import") (part "R-EU_R0805"))
    )
    (comp (ref "R3")
      (value "0.1R")
      (footprint "eagle-import:R0805")
      (fields (field (name "MPN") "RL1220S-R10-F"))
      (libsource (lib "eagle-import") (part "R-EU_R0805"))
    )
    (comp (ref "R4")
      (value "0.1R")
      (footprint "eagle-import:R0805")
      (fields (field (name "MPN") "RL1220S-R10-F"))
      (libsource (lib "eagle-import") (part "R-EU_R0805"))
    )
    (comp (ref "R5")
      (value "4.7K")
      (footprint "eagle-import:R0402")
      (fields (field (name "MPN") "RC0402JR-074K7L"))
      (libsource (lib "eagle-import") (part "R-EU_R0402"))
    )
    (comp (ref "R6")
      (value "10K")
      (footprint "eagle-import:R0402")
      (fields (field (name "MPN") "RC0402FR-0710KL"))
      (libsource (lib "eagle-import") (part "R-EU_R0402"))
    )
    (comp (ref "R7")
      (value "0.1R")
      (footprint "eagle-import:R0805")
      (fields (field (name "MPN") "RL1220S-R10-F"))
      (libsource (lib "eagle-import") (part "R-EU_R0805"))
    )
    (comp (ref "R8")
      (value "0.1R")
      (footprint "eagle-import:R0805")
      (fields (field (name "MPN") "RL1220S-R10-F"))
      (libsource (lib "eagle-import") (part "R-EU_R0805"))
    )
    (comp (ref "R9")
      (value "0.1R")
      (footprint "eagle-import:R0805")
      (fields (field (name "MPN") "RL1220S-R10-F"))
      (libsource (lib "eagle-import") (part "R-EU_R0805"))
    )
    (comp (ref "R10")
      (value "0.1R")
      (footprint "eagle-import:R0805")
      (fields (field (name "MPN") "RL1220S-R10-F"))
      (libsource (lib "eagle-import") (part "R-EU_R0805"))
    )
    (comp (ref "R11")
      (value "4.7K")
      (footprint "eagle-import:R0402")
      (fields (field (name "MPN") "RC0402JR-074K7L"))
      (libsource (lib "eagle-import") (part "R-EU_R0402"))
    )
    (comp (ref "R12")
      (value "44.3K,1%")
      (footprint "eagle-import:R0402")
      (fields (field (name "MPN") "RC1005F4422CS"))
      (libsource (lib "eagle-import") (part "R-EU_R0402"))
    )
    (comp (ref "R13")
      (value "4K7, 1%")
      (footprint "eagle-import:R0402")
      (fields (field (name "MPN") "RC0402FR-074K7L"))
      (libsource (lib "eagle-import") (part "R-EU_R0402"))
    )
    (comp (ref "R14")
      (value "4.7K")
      (footprint "eagle-import:R0402")
      (fields (field (name "MPN") "RC0402JR-074K7L"))
      (libsource (lib "eagle-import") (part "R-EU_R0402"))
    )
    (comp (ref "R15")
      (value "4.7K")
      (footprint "eagle-import:R0402")
      (fields (field (name "MPN") "RC0402JR-074K7L"))
      (libsource (lib "eagle-import") (part "R-EU_R0402"))
    )
    (comp (ref "R16")
      (value "4.7K")
      (footprint "eagle-import:R0402")
      (fields (field (name "MPN") "RC0402JR-074K7L"))
      (libsource (lib "eagle-import") (part "R-EU_R0402"))
    )
    (comp (ref "R17")
      (value "4K7, 1%")
      (footprint "eagle-import:R0402")
      (fields (field (name "MPN") "RC0402FR-074K7L"))
      (libsource (lib "eagle-import") (part "R-EU_R0402"))
    )
    (comp (ref "R18")
      (value "4K7, 1%")
      (footprint "eagle-import:R0402")
      (fields (field (name "MPN") "RC0402FR-074K7L"))
      (libsource (lib "eagle-import") (part "R-EU_R0402"))
    )
    (comp (ref "R19")
      (value "4.7K")
      (footprint "eagle-import:R0402")
      (fields (field (name "MPN") "RC0402JR-074K7L"))
      (libsource (lib "eagle-import") (part "R-EU_R0402"))
    )
    (comp (ref "R20")
      (value "4.7K")
      (footprint "eagle-import:R0402")
      (fields (field (name "MPN") "RC0402JR-074K7L"))
      (libsource (lib "eagle-import") (part "R-EU_R0402"))
    )
    (comp (ref "R21")
      (value "4.7K")
      (footprint "eagle-import:R0402")
      (fields (field (name "MPN") "RC0402JR-074K7L"))
      (libsource (lib "eagle-import") (part "R-EU_R0402"))
    )
    (comp (ref "R22")
      (value "10K,1%")
      (footprint "eagle-import:R0402")
      (fields (field (name "MPN") "RC0402FR-0710KL"))
      (libsource (lib "eagle-import") (part "R-EU_R0402"))
    )
    (comp (ref "R23")
      (value "4.7K")
      (footprint "eagle-import:R0402")
      (fields (field (name "MPN") "RC0402JR-074K7L"))
      (libsource (lib "eagle-import") (part "R-EU_R0402"))
    )
    (comp (ref "R24")
      (value "4.7K")
      (footprint "eagle-import:R0402")
      (fields (field (name "MPN") "RC0402JR-074K7L"))
      (libsource (lib "eagle-import") (part "R-EU_R0402"))
    )
    (comp (ref "R25")
      (value "4.7K")
      (footprint "eagle-import:R0402")
      (fields (field (name "MPN") "RC0402JR-074K7L"))
      (libsource (lib "eagle-import") (part "R-EU_R0402"))
    )
    (comp (ref "R26")
      (value "39K")
      (footprint "eagle-import:R0402")
      (fields (field (name "MPN") "RC1005J393CS"))
      (libsource (lib "eagle-import") (part "R-EU_R0402"))
    )
    (comp (ref "R27")
      (value "10K")
      (footprint "eagle-import:R0402")
      (fields (field (name "MPN") "RC0402FR-0710KL"))
      (libsource (lib "eagle-import") (part "R-EU_R0402"))
    )
    (comp (ref "R28")
      (value "4.7K")
      (footprint "eagle-import:R0402")
      (fields (field (name "MPN") "RC0402JR-074K7L"))
      (libsource (lib "eagle-import") (part "R-EU_R0402"))
    )
    (comp (ref "R29")
      (value "0.1R")
      (footprint "eagle-import:R0805")
      (fields (field (name "MPN") "RL1220S-R10-F"))
      (libsource (lib "eagle-import") (part "R-EU_R0805"))
    )
    (comp (ref "R30")
      (value "0.1R")
      (footprint "eagle-import:R0805")
      (fields (field (name "MPN") "RL1220S-R10-F"))
      (libsource (lib "eagle-import") (part "R-EU_R0805"))
    )
    (comp (ref "R31")
      (value "10K")
      (footprint "eagle-import:R0402")
      (fields (field (name "MPN") "RC0402FR-0710KL"))
      (libsource (lib "eagle-import") (part "R-EU_R0402"))
    )
    (comp (ref "R32")
      (value "4.7K")
      (footprint "eagle-import:R0402")
      (fields (field (name "MPN") "RC0402JR-074K7L"))
      (libsource (lib "eagle-import") (part "R-EU_R0402"))
    )
    (comp (ref "R33")
      (value "4.7K")
      (footprint "eagle-import:R0402")
      (fields (field (name "MPN") "RC0402JR-074K7L"))
      (libsource (lib "eagle-import") (part "R-EU_R0402"))
    )
    (comp (ref "R34")
      (value "4.7K")
      (footprint "eagle-import:R0402")
      (fields (field (name "MPN") "RC0402JR-074K7L"))
      (libsource (lib "eagle-import") (part "R-EU_R0402"))
    )
    (comp (ref "R35")
      (value "10K")
      (footprint "eagle-import:R0402")
      (fields (field (name "MPN") "RC0402FR-0710KL"))
      (libsource (lib "eagle-import") (part "R-EU_R0402"))
    )
    (comp (ref "R36")
      (value "4.7K")
      (footprint "eagle-import:R0402")
      (fields (field (name "MPN") "RC0402JR-074K7L"))
      (libsource (lib "eagle-import") (part "R-EU_R0402"))
    )
    (comp (ref "R37")
      (value "10K")
      (footprint "eagle-import:R0402")
      (fields (field (name "MPN") "RC0402FR-0710KL"))
      (libsource (lib "eagle-import") (part "R-EU_R0402"))
    )
    (comp (ref "R38")
      (value "10K")
      (footprint "eagle-import:R0402")
      (fields (field (name "MPN") "RC0402FR-0710KL"))
      (libsource (lib "eagle-import") (part "R-EU_R0402"))
    )
    (comp (ref "R39")
      (value "10K")
      (footprint "eagle-import:R0402")
      (fields (field (name "MPN") "RC0402FR-0710KL"))
      (libsource (lib "eagle-import") (part "R-EU_R0402"))
    )
    (comp (ref "R40")
      (value "10K")
      (footprint "eagle-import:R0402")
      (fields (field (name "MPN") "RC0402FR-0710KL"))
      (libsource (lib "eagle-import") (part "R-EU_R0402"))
    )
    (comp (ref "R41")
      (value "10K")
      (footprint "eagle-import:R0402")
      (fields (field (name "MPN") "RC0402FR-0710KL"))
      (libsource (lib "eagle-import") (part "R-EU_R0402"))
    )
    (comp (ref "R42")
      (value "120K,1%")
      (footprint "eagle-import:R0402")
      (fields (field (name "MPN") "RMCF0402FT120K"))
      (libsource (lib "eagle-import") (part "R-EU_R0402"))
    )
    (comp (ref "R43")
      (value "10K,1%")
      (footprint "eagle-import:R0402")
      (fields (field (name "MPN") "RC0402FR-0710KL"))
      (libsource (lib "eagle-import") (part "R-EU_R0402"))
    )
    (comp (ref "R44")
      (value "39K")
      (footprint "eagle-import:R0402")
      (fields (field (name "MPN") "RC1005J393CS"))
      (libsource (lib "eagle-import") (part "R-EU_R0402"))
    )
    (comp (ref "R45")
      (value "4.7K")
      (footprint "eagle-import:R0402")
      (fields (field (name "MPN") "RC0402JR-074K7L"))
      (libsource (lib "eagle-import") (part "R-EU_R0402"))
    )
    (comp (ref "R46")
      (value "4.7K")
      (footprint "eagle-import:R0402")
      (fields (field (name "MPN") "RC0402JR-074K7L"))
      (libsource (lib "eagle-import") (part "R-EU_R0402"))
    )
    (comp (ref "R47")
      (value "4.7K")
      (footprint "eagle-import:R0402")
      (fields (field (name "MPN") "RC0402JR-074K7L"))
      (libsource (lib "eagle-import") (part "R-EU_R0402"))
    )
    (comp (ref "R48")
      (value "4.7K")
      (footprint "eagle-import:R0402")
      (fields (field (name "MPN") "RC0402JR-074K7L"))
      (libsource (lib "eagle-import") (part "R-EU_R0402"))
    )
    (comp (ref "R49")
      (value "10K")
      (footprint "eagle-import:R0402")
      (fields (field (name "MPN") "RC0402FR-0710KL"))
      (libsource (lib "eagle-import") (part "R-EU_R0402"))
    )
    (comp (ref "R50")
      (value "10K")
      (footprint "eagle-import:R0402")
      (fields (field (name "MPN") "RC0402FR-0710KL"))
      (libsource (lib "eagle-import") (part "R-EU_R0402"))
    )
    (comp (ref "R51")
      (value "4.7K")
      (footprint "eagle-import:R0402")
      (fields (field (name "MPN") "RC0402JR-074K7L"))
      (libsource (lib "eagle-import") (part "R-EU_R0402"))
    )
    (comp (ref "R52")
      (value "2.2R")
      (footprint "eagle-import:R0402")
      (fields (field (name "MPN") "RC1005J2R2CS"))
      (libsource (lib "eagle-import") (part "R-EU_R0402"))
    )
    (comp (ref "R53")
      (value "2.2R")
      (footprint "eagle-import:R0402")
      (fields (field (name "MPN") "RC1005J2R2CS"))
      (libsource (lib "eagle-import") (part "R-EU_R0402"))
    )
    (comp (ref "R54")
      (value "4.7K")
      (footprint "eagle-import:R0402")
      (fields (field (name "MPN") "RC0402JR-074K7L"))
      (libsource (lib "eagle-import") (part "R-EU_R0402"))
    )
    (comp (ref "R55")
      (value "4.7K")
      (footprint "eagle-import:R0402")
      (fields (field (name "MPN") "RC0402JR-074K7L"))
      (libsource (lib "eagle-import") (part "R-EU_R0402"))
    )
    (comp (ref "R56")
      (value "4.7K")
      (footprint "eagle-import:R0402")
      (fields (field (name "MPN") "RC0402JR-074K7L"))
      (libsource (lib "eagle-import") (part "R-EU_R0402"))
    )
    (comp (ref "R57")
      (value "4.7K")
      (footprint "eagle-import:R0402")
      (fields (field (name "MPN") "RC0402JR-074K7L"))
      (libsource (lib "eagle-import") (part "R-EU_R0402"))
    )
    (comp (ref "R58")
      (value "10K")
      (footprint "eagle-import:R0402")
      (fields (field (name "MPN") "RC0402FR-0710KL"))
      (libsource (lib "eagle-import") (part "R-EU_R0402"))
    )
    (comp (ref "R59")
      (value "2.2R")
      (footprint "eagle-import:R0402")
      (fields (field (name "MPN") "RC1005J2R2CS"))
      (libsource (lib "eagle-import") (part "R-EU_R0402"))
    )
    (comp (ref "R60")
      (value "10K")
      (footprint "eagle-import:R0402")
      (fields (field (name "MPN") "RC0402FR-0710KL"))
      (libsource (lib "eagle-import") (part "R-EU_R0402"))
    )
    (comp (ref "R61")
      (value "4.7K")
      (footprint "eagle-import:R0402")
      (fields (field (name "MPN") "RC0402JR-074K7L"))
      (libsource (lib "eagle-import") (part "R-EU_R0402"))
    )
    (comp (ref "R62")
      (value "4.7K")
      (footprint "eagle-import:R0402")
      (fields (field (name "MPN") "RC0402JR-074K7L"))
      (libsource (lib "eagle-import") (part "R-EU_R0402"))
    )
    (comp (ref "R63")
      (value "4.7K")
      (footprint "eagle-import:R0402")
      (fields (field (name "MPN") "RC0402JR-074K7L"))
      (libsource (lib "eagle-import") (part "R-EU_R0402"))
    )
    (comp (ref "R64")
      (value "4.7K")
      (footprint "eagle-import:R0402")
      (fields (field (name "MPN") "RC0402JR-074K7L"))
      (libsource (lib "eagle-import") (part "R-EU_R0402"))
    )
    (comp (ref "R65")
      (value "4.7K")
      (footprint "eagle-import:R0402")
      (fields (field (name "MPN") "RC0402JR-074K7L"))
      (libsource (lib "eagle-import") (part "R-EU_R0402"))
    )
    (comp (ref "R66")
      (value "4.7K")
      (footprint "eagle-import:R0402")
      (fields (field (name "MPN") "RC0402JR-074K7L"))
      (libsource (lib "eagle-import") (part "R-EU_R0402"))
    )
    (comp (ref "R70")
      (value "2.2R")
      (footprint "eagle-import:R0402")
      (fields (field (name "MPN") "RC1005J2R2CS"))
      (libsource (lib "eagle-import") (part "R-EU_R0402"))
    )
    (comp (ref "R71")
      (value "2.2R")
      (footprint "eagle-import:R0402")
      (fields (field (name "MPN") "RC1005J2R2CS"))
      (libsource (lib "eagle-import") (part "R-EU_R0402"))
    )
    (comp (ref "SV2")
      (value "MA03-1")
      (footprint "eagle-import:MA03-1")
      (libsource (lib "eagle-import") (part "MA03-1"))
    )
    (comp (ref "U$4")
      (value "CC-BY-SA")
      (footprint "eagle-import:CC-BY-SA")
      (libsource (lib "eagle-import") (part "CC-BY-SA"))
    )
    (comp (ref "U1")
      (value "SN74AHC595PW")
      (footprint "eagle-import:SOP65P640X120-16N")
      (fields (field (name "MPN") "MC74HC595ADTR2G"))
      (libsource (lib "eagle-import") (part "SN74AHC595PW"))
    )
    (comp (ref "U2")
      (value "SN74AHC595PW")
      (footprint "eagle-import:SOP65P640X120-16N")
      (fields (field (name "MPN") "MC74HC595ADTR2G"))
      (libsource (lib "eagle-import") (part "SN74AHC595PW"))
    )
    (comp (ref "U3")
      (value "SN74AHC595PW")
      (footprint "eagle-import:SOP65P640X120-16N")
      (fields (field (name "MPN") "MC74HC595ADTR2G"))
      (libsource (lib "eagle-import") (part "SN74AHC595PW"))
    )
    (comp (ref "U4")
      (value "SN74AHC595PW")
      (footprint "eagle-import:SOP65P640X120-16N")
      (fields (field (name "MPN") "MC74HC595ADTR2G"))
      (libsource (lib "eagle-import") (part "SN74AHC595PW"))
    )
    (comp (ref "U5")
      (value "SN74AHC595PW")
      (footprint "eagle-import:SOP65P640X120-16N")
      (fields (field (name "MPN") "MC74HC595ADTR2G"))
      (libsource (lib "eagle-import") (part "SN74AHC595PW"))
    )
    (comp (ref "U6")
      (value "RT8268")
      (footprint "eagle-import:MSOP10")
      (fields (field (name "MPN") "RT8268GFP"))
      (libsource (lib "eagle-import") (part "RT8268"))
    )
    (comp (ref "U8")
      (value "FI-RE41S-HFRIGHT_ANGLE")
      (footprint "eagle-import:JAE_FI-RE41S-HF")
      (fields (field (name "MPN") "FI-RE41S-HF"))
      (libsource (lib "eagle-import") (part "FI-RE41S-HFRIGHT_ANGLE"))
    )
    (comp (ref "U10")
      (value "RT8268")
      (footprint "eagle-import:MSOP10")
      (fields (field (name "MPN") "RT8268GFP"))
      (libsource (lib "eagle-import") (part "RT8268"))
    )
    (comp (ref "U11")
      (value "PCA9685PW")
      (footprint "eagle-import:SOP65P640X110-28N")
      (fields (field (name "MPN") "PCA9685PW,112"))
      (libsource (lib "eagle-import") (part "PCA9685PW"))
    )
    (comp (ref "U18")
      (value "CAT24C256")
      (footprint "eagle-import:SOIC127P600X175-8N")
      (fields (field (name "MPN") "CAT24C256WI-GT3"))
      (libsource (lib "eagle-import") (part "CAT24C256"))
    )
    (comp (ref "U19")
      (value "CD4050BD")
      (footprint "eagle-import:SOIC127P600X175-16N")
      (fields (field (name "MPN") "CD4050BDR"))
      (libsource (lib "eagle-import") (part "CD4050BD"))
    )
    (comp (ref "X1")
      (value "22-05-7038-03")
      (footprint "eagle-import:7395-03")
      (fields (field (name "MPN") "640455-3"))
      (libsource (lib "eagle-import") (part "22-?-0305-7038"))
    )
    (comp (ref "X2")
      (value "MSTBA4")
      (footprint "eagle-import:MSTBA4")
      (fields
        (field (name "MF") "FARNELL")
        (field (name "MPN") "1757268")
        (field (name "MPN_1") "39532-1004")
      )
      (libsource (lib "eagle-import") (part "MSTBA4"))
    )
    (comp (ref "X3")
      (value "MSTBA2")
      (footprint "eagle-import:MSTBA2")
      (fields
        (field (name "MF") "FARNELL")
        (field (name "MPN") "1757242")
        (field (name "MPN_1") "39532-1002")
      )
      (libsource (lib "eagle-import") (part "MSTBA2"))
    )
    (comp (ref "X4")
      (value "22-05-7048-04")
      (footprint "eagle-import:7395-04")
      (fields (field (name "MPN") "640455-4"))
      (libsource (lib "eagle-import") (part "22-?-0405-7048"))
    )
    (comp (ref "X5")
      (value "22-05-7028-02")
      (footprint "eagle-import:7395-02")
      (fields (field (name "MPN") "640455-2"))
      (libsource (lib "eagle-import") (part "22-?-0205-7028"))
    )
    (comp (ref "X6")
      (value "22-05-7028-02")
      (footprint "eagle-import:7395-02")
      (fields (field (name "MPN") "640455-2"))
      (libsource (lib "eagle-import") (part "22-?-0205-7028"))
    )
    (comp (ref "X7")
      (value "22-05-7028-02")
      (footprint "eagle-import:7395-02")
      (fields (field (name "MPN") "640455-2"))
      (libsource (lib "eagle-import") (part "22-?-0205-7028"))
    )
    (comp (ref "X8")
      (value "22-05-7028-02")
      (footprint "eagle-import:7395-02")
      (fields (field (name "MPN") "640455-2"))
      (libsource (lib "eagle-import") (part "22-?-0205-7028"))
    )
    (comp (ref "X9")
      (value "22-05-7048-04")
      (footprint "eagle-import:7395-04")
      (fields (field (name "MPN") "640455-4"))
      (libsource (lib "eagle-import") (part "22-?-0405-7048"))
    )
    (comp (ref "X10")
      (value "22-05-7038-03")
      (footprint "eagle-import:7395-03")
      (fields (field (name "MPN") "640455-3"))
      (libsource (lib "eagle-import") (part "22-?-0305-7038"))
    )
    (comp (ref "X11")
      (value "22-05-7028-02")
      (footprint "eagle-import:7395-02")
      (fields (field (name "MPN") "640455-2"))
      (libsource (lib "eagle-import") (part "22-?-0205-7028"))
    )
    (comp (ref "X12")
      (value "22-05-7048-04")
      (footprint "eagle-import:7395-04")
      (fields (field (name "MPN") "640455-4"))
      (libsource (lib "eagle-import") (part "22-?-0405-7048"))
    )
    (comp (ref "X13")
      (value "22-05-7038-03")
      (footprint "eagle-import:7395-03")
      (fields (field (name "MPN") "640455-3"))
      (libsource (lib "eagle-import") (part "22-?-0305-7038"))
    )
    (comp (ref "X15")
      (value "22-05-7048-04")
      (footprint "eagle-import:7395-04")
      (fields (field (name "MPN") "640455-4"))
      (libsource (lib "eagle-import") (part "22-?-0405-7048"))
    )
    (comp (ref "X16")
      (value "22-05-7048-04")
      (footprint "eagle-import:7395-04")
      (fields (field (name "MPN") "640455-4"))
      (libsource (lib "eagle-import") (part "22-?-0405-7048"))
    )
    (comp (ref "X18")
      (value "22-05-7048-04")
      (footprint "eagle-import:7395-04")
      (fields (field (name "MPN") "640455-4"))
      (libsource (lib "eagle-import") (part "22-?-0405-7048"))
    )
    (comp (ref "X19")
      (value "22-05-7038-03")
      (footprint "eagle-import:7395-03")
      (fields (field (name "MPN") "640455-3"))
      (libsource (lib "eagle-import") (part "22-?-0305-7038"))
    )
    (comp (ref "X20")
      (value "MSTBA4")
      (footprint "eagle-import:MSTBA4")
      (fields
        (field (name "MF") "FARNELL")
        (field (name "MPN") "1757268")
        (field (name "MPN_1") "39532-1004")
      )
      (libsource (lib "eagle-import") (part "MSTBA4"))
    )
    (comp (ref "X21")
      (value "MSTBA2")
      (footprint "eagle-import:MSTBA2")
      (fields
        (field (name "MF") "FARNELL")
        (field (name "MPN") "1757242")
        (field (name "MPN_1") "39532-1002")
      )
      (libsource (lib "eagle-import") (part "MSTBA2"))
    )
    (comp (ref "X22")
      (value "22-05-7038-03")
      (footprint "eagle-import:7395-03")
      (fields (field (name "MPN") "640455-3"))
      (libsource (lib "eagle-import") (part "22-?-0305-7038"))
    )
    (comp (ref "X23")
      (value "22-05-7038-03")
      (footprint "eagle-import:7395-03")
      (fields (field (name "MPN") "640455-3"))
      (libsource (lib "eagle-import") (part "22-?-0305-7038"))
    )
    (comp (ref "XC1")
      (value "MSTBA4-CONNECTOR")
      (footprint "eagle-import:MSTBA4-CONNECTOR")
      (fields (field (name "MPN") "39530-0004"))
      (libsource (lib "eagle-import") (part "MSTBA4-CONNECTOR"))
    )
    (comp (ref "XC2")
      (value "MSTBA4-CONNECTOR")
      (footprint "eagle-import:MSTBA4-CONNECTOR")
      (fields (field (name "MPN") "39530-0004"))
      (libsource (lib "eagle-import") (part "MSTBA4-CONNECTOR"))
    )
    (comp (ref "XC3")
      (value "MSTBV2-CONNECTOR")
      (footprint "eagle-import:MSTBA2-CONNECTOR")
      (fields (field (name "MPN") "39530-0002"))
      (libsource (lib "eagle-import") (part "MSTBV2-CONNECTOR"))
    )
    (comp (ref "XC4")
      (value "MSTBV2-CONNECTOR")
      (footprint "eagle-import:MSTBA2-CONNECTOR")
      (fields (field (name "MPN") "39530-0002"))
      (libsource (lib "eagle-import") (part "MSTBV2-CONNECTOR"))
    )
  )
  (nets
    (net (code "1") (name "+3V3") (class "Default")
      (node (ref "3.3V") (pin "TP") (pinfunction "TP_TP") (pintype "input"))
      (node (ref "C13") (pin "1") (pinfunction "1_1") (pintype "passive"))
      (node (ref "C14") (pin "1") (pinfunction "1_1") (pintype "passive"))
      (node (ref "C15") (pin "1") (pinfunction "1_1") (pintype "passive"))
      (node (ref "C2") (pin "1") (pinfunction "1_1") (pintype "passive"))
      (node (ref "C23") (pin "1") (pinfunction "1_1") (pintype "passive"))
      (node (ref "C30") (pin "1") (pinfunction "1_1") (pintype "passive"))
      (node (ref "C41") (pin "1") (pinfunction "1_1") (pintype "passive"))
      (node (ref "C42") (pin "1") (pinfunction "1_1") (pintype "passive"))
      (node (ref "C44") (pin "1") (pinfunction "1_1") (pintype "passive"))
      (node (ref "C5") (pin "1") (pinfunction "1_1") (pintype "passive"))
      (node (ref "C61") (pin "1") (pinfunction "1_1") (pintype "passive"))
      (node (ref "C63") (pin "1") (pinfunction "1_1") (pintype "passive"))
      (node (ref "C84") (pin "1") (pinfunction "1_1") (pintype "passive"))
      (node (ref "C85") (pin "1") (pinfunction "1_1") (pintype "passive"))
      (node (ref "C86") (pin "1") (pinfunction "1_1") (pintype "passive"))
      (node (ref "C87") (pin "1") (pinfunction "1_1") (pintype "passive"))
      (node (ref "C88") (pin "1") (pinfunction "1_1") (pintype "passive"))
      (node (ref "IC1") (pin "8") (pinfunction "VCC_IO_8") (pintype "bidirectional"))
      (node (ref "IC10") (pin "5") (pinfunction "VCC_5") (pintype "power_in"))
      (node (ref "IC11") (pin "5") (pinfunction "VCC_5") (pintype "power_in"))
      (node (ref "IC12") (pin "8") (pinfunction "VCC_IO_8") (pintype "bidirectional"))
      (node (ref "IC13") (pin "5") (pinfunction "VCC_5") (pintype "power_in"))
      (node (ref "IC14") (pin "5") (pinfunction "VCC_5") (pintype "power_in"))
      (node (ref "IC15") (pin "8") (pinfunction "VCC_IO_8") (pintype "bidirectional"))
      (node (ref "IC16") (pin "5") (pinfunction "VCC_5") (pintype "power_in"))
      (node (ref "IC17") (pin "5") (pinfunction "VCC_5") (pintype "power_in"))
      (node (ref "IC18") (pin "5") (pinfunction "VCC_5") (pintype "power_in"))
      (node (ref "IC19") (pin "5") (pinfunction "VCC_5") (pintype "power_in"))
      (node (ref "IC2") (pin "8") (pinfunction "VCC_IO_8") (pintype "bidirectional"))
      (node (ref "IC20") (pin "5") (pinfunction "VCC_5") (pintype "power_in"))
      (node (ref "IC21") (pin "5") (pinfunction "VCC_5") (pintype "power_in"))
      (node (ref "IC22") (pin "5") (pinfunction "VCC_5") (pintype "power_in"))
      (node (ref "IC3") (pin "5") (pinfunction "VCC_5") (pintype "power_in"))
      (node (ref "IC4") (pin "5") (pinfunction "VCC_5") (pintype "power_in"))
      (node (ref "IC5") (pin "8") (pinfunction "VCC_IO_8") (pintype "bidirectional"))
      (node (ref "IC8") (pin "5") (pinfunction "VCC_5") (pintype "power_in"))
      (node (ref "IC9") (pin "5") (pinfunction "VCC_5") (pintype "power_in"))
      (node (ref "P9") (pin "3") (pinfunction "3_3") (pintype "passive"))
      (node (ref "P9") (pin "4") (pinfunction "4_4") (pintype "passive"))
      (node (ref "R23") (pin "2") (pinfunction "2_2") (pintype "passive"))
      (node (ref "R24") (pin "2") (pinfunction "2_2") (pintype "passive"))
      (node (ref "R28") (pin "2") (pinfunction "2_2") (pintype "passive"))
      (node (ref "R36") (pin "2") (pinfunction "2_2") (pintype "passive"))
      (node (ref "R51") (pin "2") (pinfunction "2_2") (pintype "passive"))
      (node (ref "R54") (pin "2") (pinfunction "2_2") (pintype "passive"))
      (node (ref "U1") (pin "10") (pinfunction "~{SRCLR}_10") (pintype "input"))
      (node (ref "U1") (pin "16") (pinfunction "VCC_16") (pintype "power_in"))
      (node (ref "U18") (pin "3") (pinfunction "A2_3") (pintype "input"))
      (node (ref "U18") (pin "8") (pinfunction "VCC_8") (pintype "power_in"))
      (node (ref "U19") (pin "1") (pinfunction "VCC_1") (pintype "power_in"))
      (node (ref "U2") (pin "10") (pinfunction "~{SRCLR}_10") (pintype "input"))
      (node (ref "U2") (pin "16") (pinfunction "VCC_16") (pintype "power_in"))
      (node (ref "U3") (pin "10") (pinfunction "~{SRCLR}_10") (pintype "input"))
      (node (ref "U3") (pin "16") (pinfunction "VCC_16") (pintype "power_in"))
      (node (ref "U4") (pin "10") (pinfunction "~{SRCLR}_10") (pintype "input"))
      (node (ref "U4") (pin "16") (pinfunction "VCC_16") (pintype "power_in"))
      (node (ref "U5") (pin "10") (pinfunction "~{SRCLR}_10") (pintype "input"))
      (node (ref "U5") (pin "16") (pinfunction "VCC_16") (pintype "power_in"))
      (node (ref "X23") (pin "1") (pinfunction "S_1") (pintype "passive"))
    )
    (net (code "2") (name "+5V") (class "Default")
      (node (ref "5V") (pin "TP") (pinfunction "TP_TP") (pintype "input"))
      (node (ref "C48") (pin "1") (pinfunction "1_1") (pintype "passive"))
      (node (ref "C80") (pin "1") (pinfunction "1_1") (pintype "passive"))
      (node (ref "C82") (pin "1") (pinfunction "1_1") (pintype "passive"))
      (node (ref "C83") (pin "1") (pinfunction "1_1") (pintype "passive"))
      (node (ref "IC6") (pin "5") (pinfunction "VCC_5") (pintype "power_in"))
      (node (ref "IC7") (pin "5") (pinfunction "VCC_5") (pintype "power_in"))
      (node (ref "L1") (pin "P$1") (pinfunction "P$1_P$1") (pintype "passive"))
      (node (ref "P9") (pin "5") (pinfunction "5_5") (pintype "passive"))
      (node (ref "P9") (pin "6") (pinfunction "6_6") (pintype "passive"))
      (node (ref "R12") (pin "1") (pinfunction "1_1") (pintype "passive"))
      (node (ref "R61") (pin "2") (pinfunction "2_2") (pintype "passive"))
      (node (ref "R62") (pin "2") (pinfunction "2_2") (pintype "passive"))
      (node (ref "R63") (pin "2") (pinfunction "2_2") (pintype "passive"))
      (node (ref "R64") (pin "2") (pinfunction "2_2") (pintype "passive"))
      (node (ref "R65") (pin "2") (pinfunction "2_2") (pintype "passive"))
      (node (ref "R66") (pin "2") (pinfunction "2_2") (pintype "passive"))
      (node (ref "X1") (pin "3") (pinfunction "S_3") (pintype "passive"))
      (node (ref "X10") (pin "3") (pinfunction "S_3") (pintype "passive"))
      (node (ref "X12") (pin "3") (pinfunction "S_3") (pintype "passive"))
      (node (ref "X13") (pin "3") (pinfunction "S_3") (pintype "passive"))
      (node (ref "X19") (pin "3") (pinfunction "S_3") (pintype "passive"))
      (node (ref "X22") (pin "3") (pinfunction "S_3") (pintype "passive"))
    )
    (net (code "3") (name "/DALLAS_W1") (class "Default")
      (node (ref "P9") (pin "22") (pinfunction "22_22") (pintype "passive"))
      (node (ref "X23") (pin "2") (pinfunction "S_2") (pintype "passive"))
    )
    (net (code "4") (name "/DIR_E") (class "Default")
      (node (ref "IC12") (pin "7") (pinfunction "REFR_DIR_7") (pintype "bidirectional"))
      (node (ref "P8") (pin "15") (pinfunction "15_15") (pintype "passive"))
    )
    (net (code "5") (name "/DIR_H") (class "Default")
      (node (ref "IC15") (pin "7") (pinfunction "REFR_DIR_7") (pintype "bidirectional"))
      (node (ref "P8") (pin "16") (pinfunction "16_16") (pintype "passive"))
    )
    (net (code "6") (name "/DIR_X") (class "Default")
      (node (ref "IC1") (pin "7") (pinfunction "REFR_DIR_7") (pintype "bidirectional"))
      (node (ref "P8") (pin "26") (pinfunction "26_26") (pintype "passive"))
    )
    (net (code "7") (name "/DIR_Y") (class "Default")
      (node (ref "IC2") (pin "7") (pinfunction "REFR_DIR_7") (pintype "bidirectional"))
      (node (ref "P8") (pin "19") (pinfunction "19_19") (pintype "passive"))
    )
    (net (code "8") (name "/DIR_Z") (class "Default")
      (node (ref "IC5") (pin "7") (pinfunction "REFR_DIR_7") (pintype "bidirectional"))
      (node (ref "P8") (pin "14") (pinfunction "14_14") (pintype "passive"))
    )
    (net (code "9") (name "/ENABLE") (class "Default")
      (node (ref "P9") (pin "41") (pinfunction "41_41") (pintype "passive"))
      (node (ref "R23") (pin "1") (pinfunction "1_1") (pintype "passive"))
      (node (ref "U11") (pin "23") (pinfunction "~{OE}_23") (pintype "input"))
    )
    (net (code "10") (name "/ENABLE_E") (class "Default")
      (node (ref "IC12") (pin "22") (pinfunction "DRV_ENN_CFG6_22") (pintype "bidirectional"))
      (node (ref "IC19") (pin "4") (pinfunction "O_4") (pintype "output"))
    )
    (net (code "11") (name "/ENABLE_H") (class "Default")
      (node (ref "IC15") (pin "22") (pinfunction "DRV_ENN_CFG6_22") (pintype "bidirectional"))
      (node (ref "IC22") (pin "4") (pinfunction "O_4") (pintype "output"))
    )
    (net (code "12") (name "/ENABLE_X") (class "Default")
      (node (ref "IC1") (pin "22") (pinfunction "DRV_ENN_CFG6_22") (pintype "bidirectional"))
      (node (ref "IC18") (pin "4") (pinfunction "O_4") (pintype "output"))
    )
    (net (code "13") (name "/ENABLE_Y") (class "Default")
      (node (ref "IC2") (pin "22") (pinfunction "DRV_ENN_CFG6_22") (pintype "bidirectional"))
      (node (ref "IC20") (pin "4") (pinfunction "O_4") (pintype "output"))
    )
    (net (code "14") (name "/ENABLE_Z") (class "Default")
      (node (ref "IC21") (pin "4") (pinfunction "O_4") (pintype "output"))
      (node (ref "IC5") (pin "22") (pinfunction "DRV_ENN_CFG6_22") (pintype "bidirectional"))
    )
    (net (code "15") (name "/END_STOP_X_1") (class "Default")
      (node (ref "P9") (pin "25") (pinfunction "25_25") (pintype "passive"))
      (node (ref "U19") (pin "2") (pinfunction "G=A_2") (pintype "output"))
    )
    (net (code "16") (name "/END_STOP_X_2") (class "Default")
      (node (ref "P9") (pin "11") (pinfunction "11_11") (pintype "passive"))
      (node (ref "U19") (pin "10") (pinfunction "J=D_10") (pintype "output"))
    )
    (net (code "17") (name "/END_STOP_X_2_IN") (class "Default")
      (node (ref "IC6") (pin "4") (pinfunction "O_4") (pintype "output"))
      (node (ref "R64") (pin "1") (pinfunction "1_1") (pintype "passive"))
      (node (ref "U19") (pin "9") (pinfunction "D_9") (pintype "input"))
      (node (ref "X10") (pin "1") (pinfunction "S_1") (pintype "passive"))
    )
    (net (code "18") (name "/END_STOP_Y_1") (class "Default")
      (node (ref "P9") (pin "23") (pinfunction "23_23") (pintype "passive"))
      (node (ref "U19") (pin "4") (pinfunction "H=B_4") (pintype "output"))
    )
    (net (code "19") (name "/END_STOP_Y_1_IN") (class "Default")
      (node (ref "R62") (pin "1") (pinfunction "1_1") (pintype "passive"))
      (node (ref "U19") (pin "5") (pinfunction "B_5") (pintype "input"))
      (node (ref "X1") (pin "1") (pinfunction "S_1") (pintype "passive"))
    )
    (net (code "20") (name "/END_STOP_Y_2") (class "Default")
      (node (ref "P9") (pin "28") (pinfunction "28_28") (pintype "passive"))
      (node (ref "U19") (pin "12") (pinfunction "K=E_12") (pintype "output"))
    )
    (net (code "21") (name "/END_STOP_Y_2_IN") (class "Default")
      (node (ref "IC7") (pin "4") (pinfunction "O_4") (pintype "output"))
      (node (ref "R65") (pin "1") (pinfunction "1_1") (pintype "passive"))
      (node (ref "U19") (pin "11") (pinfunction "E_11") (pintype "input"))
      (node (ref "X19") (pin "1") (pinfunction "S_1") (pintype "passive"))
    )
    (net (code "22") (name "/END_STOP_Z_1") (class "Default")
      (node (ref "P9") (pin "13") (pinfunction "13_13") (pintype "passive"))
      (node (ref "U19") (pin "6") (pinfunction "I=C_6") (pintype "output"))
    )
    (net (code "23") (name "/END_STOP_Z_1_IN") (class "Default")
      (node (ref "R63") (pin "1") (pinfunction "1_1") (pintype "passive"))
      (node (ref "U19") (pin "7") (pinfunction "C_7") (pintype "input"))
      (node (ref "X13") (pin "1") (pinfunction "S_1") (pintype "passive"))
    )
    (net (code "24") (name "/END_STOP_Z_2") (class "Default")
      (node (ref "P9") (pin "18") (pinfunction "18_18") (pintype "passive"))
      (node (ref "U19") (pin "15") (pinfunction "L=F_15") (pintype "output"))
    )
    (net (code "25") (name "/EN_EH") (class "Default")
      (node (ref "IC19") (pin "2") (pinfunction "I_2") (pintype "input"))
      (node (ref "IC22") (pin "2") (pinfunction "I_2") (pintype "input"))
      (node (ref "U4") (pin "15") (pinfunction "QA_15") (pintype "output"))
    )
    (net (code "26") (name "/EN_XYZ") (class "Default")
      (node (ref "IC18") (pin "2") (pinfunction "I_2") (pintype "input"))
      (node (ref "IC20") (pin "2") (pinfunction "I_2") (pintype "input"))
      (node (ref "IC21") (pin "2") (pinfunction "I_2") (pintype "input"))
      (node (ref "U1") (pin "15") (pinfunction "QA_15") (pintype "output"))
    )
    (net (code "27") (name "/FAN0") (class "Default")
      (node (ref "Q6") (pin "1") (pinfunction "B_1") (pintype "passive"))
      (node (ref "R34") (pin "2") (pinfunction "2_2") (pintype "passive"))
      (node (ref "U11") (pin "13") (pinfunction "LED7_13") (pintype "output"))
    )
    (net (code "28") (name "/FAN1") (class "Default")
      (node (ref "Q7") (pin "1") (pinfunction "B_1") (pintype "passive"))
      (node (ref "R33") (pin "2") (pinfunction "2_2") (pintype "passive"))
      (node (ref "U11") (pin "15") (pinfunction "LED8_15") (pintype "output"))
    )
    (net (code "29") (name "/FAN2") (class "Default")
      (node (ref "Q4") (pin "1") (pinfunction "B_1") (pintype "passive"))
      (node (ref "R32") (pin "2") (pinfunction "2_2") (pintype "passive"))
      (node (ref "U11") (pin "16") (pinfunction "LED9_16") (pintype "output"))
    )
    (net (code "30") (name "/FAN3") (class "Default")
      (node (ref "Q5") (pin "1") (pinfunction "B_1") (pintype "passive"))
      (node (ref "R5") (pin "2") (pinfunction "2_2") (pintype "passive"))
      (node (ref "U11") (pin "17") (pinfunction "LED10_17") (pintype "output"))
    )
    (net (code "31") (name "/FAULT_E") (class "Default")
      (node (ref "IC12") (pin "20") (pinfunction "SWN_DIAG0_20") (pintype "bidirectional"))
      (node (ref "P8") (pin "18") (pinfunction "18_18") (pintype "passive"))
      (node (ref "R36") (pin "1") (pinfunction "1_1") (pintype "passive"))
    )
    (net (code "32") (name "/FAULT_H") (class "Default")
      (node (ref "IC15") (pin "20") (pinfunction "SWN_DIAG0_20") (pintype "bidirectional"))
      (node (ref "P8") (pin "8") (pinfunction "8_8") (pintype "passive"))
      (node (ref "R51") (pin "1") (pinfunction "1_1") (pintype "passive"))
    )
    (net (code "33") (name "/FAULT_X") (class "Default")
      (node (ref "IC1") (pin "20") (pinfunction "SWN_DIAG0_20") (pintype "bidirectional"))
      (node (ref "P8") (pin "10") (pinfunction "10_10") (pintype "passive"))
      (node (ref "R54") (pin "1") (pinfunction "1_1") (pintype "passive"))
    )
    (net (code "34") (name "/FAULT_Y") (class "Default")
      (node (ref "IC2") (pin "20") (pinfunction "SWN_DIAG0_20") (pintype "bidirectional"))
      (node (ref "P8") (pin "9") (pinfunction "9_9") (pintype "passive"))
      (node (ref "R24") (pin "1") (pinfunction "1_1") (pintype "passive"))
    )
    (net (code "35") (name "/FAULT_Z") (class "Default")
      (node (ref "IC5") (pin "20") (pinfunction "SWN_DIAG0_20") (pintype "bidirectional"))
      (node (ref "P9") (pin "24") (pinfunction "24_24") (pintype "passive"))
      (node (ref "R28") (pin "1") (pinfunction "1_1") (pintype "passive"))
    )
    (net (code "36") (name "/HEATER_E") (class "Default")
      (node (ref "Q3") (pin "4") (pinfunction "G_4") (pintype "passive"))
      (node (ref "R47") (pin "2") (pinfunction "2_2") (pintype "passive"))
      (node (ref "U11") (pin "11") (pinfunction "LED5_11") (pintype "output"))
    )
    (net (code "37") (name "/HEATER_H") (class "Default")
      (node (ref "Q2") (pin "4") (pinfunction "G_4") (pintype "passive"))
      (node (ref "R48") (pin "2") (pinfunction "2_2") (pintype "passive"))
      (node (ref "U11") (pin "9") (pinfunction "LED3_9") (pintype "output"))
    )
    (net (code "38") (name "/HEATER_HBP") (class "Default")
      (node (ref "Q1") (pin "4") (pinfunction "G_4") (pintype "passive"))
      (node (ref "R46") (pin "2") (pinfunction "2_2") (pintype "passive"))
      (node (ref "U11") (pin "10") (pinfunction "LED4_10") (pintype "output"))
    )
    (net (code "39") (name "/I2C2_SCL") (class "Default")
      (node (ref "P9") (pin "19") (pinfunction "19_19") (pintype "passive"))
      (node (ref "U11") (pin "26") (pinfunction "SCL_26") (pintype "input"))
      (node (ref "U18") (pin "6") (pinfunction "SCL_6") (pintype "input"))
    )
    (net (code "40") (name "/I2C2_SDA") (class "Default")
      (node (ref "P9") (pin "20") (pinfunction "20_20") (pintype "passive"))
      (node (ref "U11") (pin "27") (pinfunction "SDA_27") (pintype "bidirectional"))
      (node (ref "U18") (pin "5") (pinfunction "SDA_5") (pintype "bidirectional"))
    )
    (net (code "41") (name "/IREF_E_RAW") (class "Default")
      (node (ref "R60") (pin "2") (pinfunction "2_2") (pintype "passive"))
      (node (ref "U11") (pin "21") (pinfunction "LED14_21") (pintype "output"))
    )
    (net (code "42") (name "/IREF_H_RAW") (class "Default")
      (node (ref "R31") (pin "2") (pinfunction "2_2") (pintype "passive"))
      (node (ref "U11") (pin "22") (pinfunction "LED15_22") (pintype "output"))
    )
    (net (code "43") (name "/IREF_X_RAW") (class "Default")
      (node (ref "R41") (pin "2") (pinfunction "2_2") (pintype "passive"))
      (node (ref "U11") (pin "18") (pinfunction "LED11_18") (pintype "output"))
    )
    (net (code "44") (name "/IREF_Y_RAW") (class "Default")
      (node (ref "R37") (pin "2") (pinfunction "2_2") (pintype "passive"))
      (node (ref "U11") (pin "19") (pinfunction "LED12_19") (pintype "output"))
    )
    (net (code "45") (name "/IREF_Z_RAW") (class "Default")
      (node (ref "R58") (pin "2") (pinfunction "2_2") (pintype "passive"))
      (node (ref "U11") (pin "20") (pinfunction "LED13_20") (pintype "output"))
    )
    (net (code "46") (name "/SERVO_0") (class "Default")
      (node (ref "IC6") (pin "2") (pinfunction "I_2") (pintype "input"))
      (node (ref "P9") (pin "14") (pinfunction "14_14") (pintype "passive"))
    )
    (net (code "47") (name "/SERVO_0_EN") (class "Default")
      (node (ref "IC6") (pin "1") (pinfunction "OE_1") (pintype "input"))
      (node (ref "U2") (pin "15") (pinfunction "QA_15") (pintype "output"))
    )
    (net (code "48") (name "/SERVO_1") (class "Default")
      (node (ref "IC7") (pin "2") (pinfunction "I_2") (pintype "input"))
      (node (ref "P9") (pin "16") (pinfunction "16_16") (pintype "passive"))
    )
    (net (code "49") (name "/SERVO_1_EN") (class "Default")
      (node (ref "IC7") (pin "1") (pinfunction "OE_1") (pintype "input"))
      (node (ref "U3") (pin "15") (pinfunction "QA_15") (pintype "output"))
    )
    (net (code "50") (name "/SER_2") (class "Default")
      (node (ref "U1") (pin "9") (pinfunction "QH_2_9") (pintype "output"))
      (node (ref "U2") (pin "14") (pinfunction "SER_14") (pintype "input"))
    )
    (net (code "51") (name "/SER_3") (class "Default")
      (node (ref "U2") (pin "9") (pinfunction "QH_2_9") (pintype "output"))
      (node (ref "U3") (pin "14") (pinfunction "SER_14") (pintype "input"))
    )
    (net (code "52") (name "/SER_4") (class "Default")
      (node (ref "U3") (pin "9") (pinfunction "QH_2_9") (pintype "output"))
      (node (ref "U4") (pin "14") (pinfunction "SER_14") (pintype "input"))
    )
    (net (code "53") (name "/SER_5") (class "Default")
      (node (ref "U4") (pin "9") (pinfunction "QH_2_9") (pintype "output"))
      (node (ref "U5") (pin "14") (pinfunction "SER_14") (pintype "input"))
    )
    (net (code "54") (name "/SPI1_CS1") (class "Default")
      (node (ref "P9") (pin "42") (pinfunction "42_42") (pintype "passive"))
      (node (ref "U1") (pin "12") (pinfunction "RCLK_12") (pintype "input"))
      (node (ref "U2") (pin "12") (pinfunction "RCLK_12") (pintype "input"))
      (node (ref "U3") (pin "12") (pinfunction "RCLK_12") (pintype "input"))
      (node (ref "U4") (pin "12") (pinfunction "RCLK_12") (pintype "input"))
      (node (ref "U5") (pin "12") (pinfunction "RCLK_12") (pintype "input"))
    )
    (net (code "55") (name "/SPI1_MOSI") (class "Default")
      (node (ref "P9") (pin "30") (pinfunction "30_30") (pintype "passive"))
      (node (ref "U1") (pin "14") (pinfunction "SER_14") (pintype "input"))
    )
    (net (code "56") (name "/SPI1_SCLK") (class "Default")
      (node (ref "P9") (pin "31") (pinfunction "31_31") (pintype "passive"))
      (node (ref "U1") (pin "11") (pinfunction "SRCLK_11") (pintype "input"))
      (node (ref "U2") (pin "11") (pinfunction "SRCLK_11") (pintype "input"))
      (node (ref "U3") (pin "11") (pinfunction "SRCLK_11") (pintype "input"))
      (node (ref "U4") (pin "11") (pinfunction "SRCLK_11") (pintype "input"))
      (node (ref "U5") (pin "11") (pinfunction "SRCLK_11") (pintype "input"))
    )
    (net (code "57") (name "/STEP_E") (class "Default")
      (node (ref "IC12") (pin "6") (pinfunction "REFL_STEP_6") (pintype "bidirectional"))
      (node (ref "P9") (pin "12") (pinfunction "12_12") (pintype "passive"))
    )
    (net (code "58") (name "/STEP_H") (class "Default")
      (node (ref "IC15") (pin "6") (pinfunction "REFL_STEP_6") (pintype "bidirectional"))
      (node (ref "P8") (pin "11") (pinfunction "11_11") (pintype "passive"))
    )
    (net (code "59") (name "/STEP_X") (class "Default")
      (node (ref "IC1") (pin "6") (pinfunction "REFL_STEP_6") (pintype "bidirectional"))
      (node (ref "P8") (pin "17") (pinfunction "17_17") (pintype "passive"))
    )
    (net (code "60") (name "/STEP_Y") (class "Default")
      (node (ref "IC2") (pin "6") (pinfunction "REFL_STEP_6") (pintype "bidirectional"))
      (node (ref "P8") (pin "12") (pinfunction "12_12") (pintype "passive"))
    )
    (net (code "61") (name "/STEP_Z") (class "Default")
      (node (ref "IC5") (pin "6") (pinfunction "REFL_STEP_6") (pintype "bidirectional"))
      (node (ref "P8") (pin "13") (pinfunction "13_13") (pintype "passive"))
    )
    (net (code "62") (name "/SYS_5V") (class "Default")
      (node (ref "C17") (pin "1") (pinfunction "1_1") (pintype "passive"))
      (node (ref "P9") (pin "7") (pinfunction "7_7") (pintype "passive"))
      (node (ref "P9") (pin "8") (pinfunction "8_8") (pintype "passive"))
      (node (ref "U11") (pin "1") (pinfunction "A0_1") (pintype "input"))
      (node (ref "U11") (pin "2") (pinfunction "A1_2") (pintype "input"))
      (node (ref "U11") (pin "24") (pinfunction "A5_24") (pintype "input"))
      (node (ref "U11") (pin "28") (pinfunction "VDD_28") (pintype "power_in"))
      (node (ref "U11") (pin "3") (pinfunction "A2_3") (pintype "input"))
      (node (ref "U11") (pin "4") (pinfunction "A3_4") (pintype "input"))
      (node (ref "U11") (pin "5") (pinfunction "A4_5") (pintype "input"))
    )
    (net (code "63") (name "/TERM_EXT1") (class "Default")
      (node (ref "C26") (pin "1") (pinfunction "1_1") (pintype "passive"))
      (node (ref "P9") (pin "33") (pinfunction "33_33") (pintype "passive"))
      (node (ref "R38") (pin "2") (pinfunction "2_2") (pintype "passive"))
    )
    (net (code "64") (name "/TERM_EXT2") (class "Default")
      (node (ref "C46") (pin "1") (pinfunction "1_1") (pintype "passive"))
      (node (ref "P9") (pin "36") (pinfunction "36_36") (pintype "passive"))
      (node (ref "R40") (pin "2") (pinfunction "2_2") (pintype "passive"))
    )
    (net (code "65") (name "/TERM_HBP") (class "Default")
      (node (ref "C45") (pin "1") (pinfunction "1_1") (pintype "passive"))
      (node (ref "P9") (pin "35") (pinfunction "35_35") (pintype "passive"))
      (node (ref "R39") (pin "2") (pinfunction "2_2") (pintype "passive"))
    )
    (net (code "66") (name "/TRISTATE_STEPPERS") (class "Default")
      (node (ref "IC18") (pin "1") (pinfunction "OE_1") (pintype "input"))
      (node (ref "IC19") (pin "1") (pinfunction "OE_1") (pintype "input"))
      (node (ref "IC20") (pin "1") (pinfunction "OE_1") (pintype "input"))
      (node (ref "IC21") (pin "1") (pinfunction "OE_1") (pintype "input"))
      (node (ref "IC22") (pin "1") (pinfunction "OE_1") (pintype "input"))
      (node (ref "U5") (pin "15") (pinfunction "QA_15") (pintype "output"))
    )
    (net (code "67") (name "/VDD_ADC") (class "Default")
      (node (ref "P9") (pin "32") (pinfunction "32_32") (pintype "passive"))
      (node (ref "R13") (pin "2") (pinfunction "2_2") (pintype "passive"))
      (node (ref "R17") (pin "2") (pinfunction "2_2") (pintype "passive"))
      (node (ref "R18") (pin "2") (pinfunction "2_2") (pintype "passive"))
    )
    (net (code "68") (name "/VIN") (class "Default")
      (node (ref "F1") (pin "P$1") (pinfunction "1_P$1") (pintype "passive"))
      (node (ref "F1") (pin "P$2") (pinfunction "1_P$2") (pintype "passive"))
      (node (ref "LED8") (pin "A") (pinfunction "A_A") (pintype "passive"))
      (node (ref "X2") (pin "3") (pinfunction "1_3") (pintype "passive"))
      (node (ref "X2") (pin "4") (pinfunction "1_4") (pintype "passive"))
    )
    (net (code "69") (name "AUX_0") (class "Default")
      (node (ref "U8") (pin "10") (pinfunction "10_10") (pintype "passive"))
      (node (ref "U8") (pin "11") (pinfunction "11_11") (pintype "passive"))
    )
    (net (code "70") (name "A_A1") (class "Default")
      (node (ref "U8") (pin "22") (pinfunction "22_22") (pintype "passive"))
    )
    (net (code "71") (name "A_A2") (class "Default")
      (node (ref "U8") (pin "21") (pinfunction "21_21") (pintype "passive"))
    )
    (net (code "72") (name "A_B1") (class "Default")
      (node (ref "U8") (pin "20") (pinfunction "20_20") (pintype "passive"))
    )
    (net (code "73") (name "A_B2") (class "Default")
      (node (ref "U8") (pin "19") (pinfunction "19_19") (pintype "passive"))
    )
    (net (code "74") (name "END_STOP_X_1_IN") (class "Default")
      (node (ref "R61") (pin "1") (pinfunction "1_1") (pintype "passive"))
      (node (ref "U19") (pin "3") (pinfunction "A_3") (pintype "input"))
      (node (ref "U8") (pin "4") (pinfunction "4_4") (pintype "passive"))
      (node (ref "X22") (pin "1") (pinfunction "S_1") (pintype "passive"))
    )
    (net (code "75") (name "END_STOP_Z_2_IN") (class "Default")
      (node (ref "R66") (pin "1") (pinfunction "1_1") (pintype "passive"))
      (node (ref "U19") (pin "14") (pinfunction "F_14") (pintype "input"))
      (node (ref "U8") (pin "13") (pinfunction "13_13") (pintype "passive"))
      (node (ref "X12") (pin "1") (pinfunction "S_1") (pintype "passive"))
    )
    (net (code "76") (name "E_A1") (class "Default")
      (node (ref "IC12") (pin "34") (pinfunction "OA1_34") (pintype "bidirectional"))
      (node (ref "U8") (pin "27") (pinfunction "27_27") (pintype "passive"))
      (node (ref "X9") (pin "1") (pinfunction "S_1") (pintype "passive"))
    )
    (net (code "77") (name "E_A2") (class "Default")
      (node (ref "IC12") (pin "32") (pinfunction "OA2_32") (pintype "bidirectional"))
      (node (ref "U8") (pin "26") (pinfunction "26_26") (pintype "passive"))
      (node (ref "X9") (pin "2") (pinfunction "S_2") (pintype "passive"))
    )
    (net (code "78") (name "E_B1") (class "Default")
      (node (ref "IC12") (pin "13") (pinfunction "OB1_13") (pintype "bidirectional"))
      (node (ref "U8") (pin "25") (pinfunction "25_25") (pintype "passive"))
      (node (ref "X9") (pin "3") (pinfunction "S_3") (pintype "passive"))
    )
    (net (code "79") (name "E_B2") (class "Default")
      (node (ref "IC12") (pin "15") (pinfunction "OB2_15") (pintype "bidirectional"))
      (node (ref "U8") (pin "24") (pinfunction "24_24") (pintype "passive"))
      (node (ref "X9") (pin "4") (pinfunction "S_4") (pintype "passive"))
    )
    (net (code "80") (name "FAN0_OUT") (class "Default")
      (node (ref "LED0") (pin "C") (pinfunction "C_C") (pintype "passive"))
      (node (ref "Q6") (pin "3") (pinfunction "C_3") (pintype "passive"))
      (node (ref "U8") (pin "14") (pinfunction "14_14") (pintype "passive"))
    )
    (net (code "81") (name "FAN1_OUT") (class "Default")
      (node (ref "LED5") (pin "C") (pinfunction "C_C") (pintype "passive"))
      (node (ref "Q7") (pin "3") (pinfunction "C_3") (pintype "passive"))
      (node (ref "U8") (pin "15") (pinfunction "15_15") (pintype "passive"))
    )
    (net (code "82") (name "GND") (class "Default")
      (node (ref "C10") (pin "2") (pinfunction "2_2") (pintype "passive"))
      (node (ref "C12") (pin "2") (pinfunction "2_2") (pintype "passive"))
      (node (ref "C13") (pin "2") (pinfunction "2_2") (pintype "passive"))
      (node (ref "C14") (pin "2") (pinfunction "2_2") (pintype "passive"))
      (node (ref "C15") (pin "2") (pinfunction "2_2") (pintype "passive"))
      (node (ref "C17") (pin "2") (pinfunction "2_2") (pintype "passive"))
      (node (ref "C18") (pin "2") (pinfunction "2_2") (pintype "passive"))
      (node (ref "C19") (pin "2") (pinfunction "2_2") (pintype "passive"))
      (node (ref "C2") (pin "2") (pinfunction "2_2") (pintype "passive"))
      (node (ref "C20") (pin "1") (pinfunction "1_1") (pintype "passive"))
      (node (ref "C21") (pin "1") (pinfunction "1_1") (pintype "passive"))
      (node (ref "C23") (pin "2") (pinfunction "2_2") (pintype "passive"))
      (node (ref "C25") (pin "2") (pinfunction "2_2") (pintype "passive"))
      (node (ref "C26") (pin "2") (pinfunction "2_2") (pintype "passive"))
      (node (ref "C27") (pin "2") (pinfunction "2_2") (pintype "passive"))
      (node (ref "C28") (pin "1") (pinfunction "1_1") (pintype "passive"))
      (node (ref "C29") (pin "2") (pinfunction "2_2") (pintype "passive"))
      (node (ref "C30") (pin "2") (pinfunction "2_2") (pintype "passive"))
      (node (ref "C31") (pin "2") (pinfunction "2_2") (pintype "passive"))
      (node (ref "C32") (pin "1") (pinfunction "1_1") (pintype "passive"))
      (node (ref "C33") (pin "1") (pinfunction "1_1") (pintype "passive"))
      (node (ref "C36") (pin "2") (pinfunction "2_2") (pintype "passive"))
      (node (ref "C37") (pin "1") (pinfunction "1_1") (pintype "passive"))
      (node (ref "C4") (pin "2") (pinfunction "2_2") (pintype "passive"))
      (node (ref "C40") (pin "2") (pinfunction "2_2") (pintype "passive"))
      (node (ref "C41") (pin "2") (pinfunction "2_2") (pintype "passive"))
      (node (ref "C42") (pin "2") (pinfunction "2_2") (pintype "passive"))
      (node (ref "C43") (pin "2") (pinfunction "2_2") (pintype "passive"))
      (node (ref "C44") (pin "2") (pinfunction "2_2") (pintype "passive"))
      (node (ref "C45") (pin "2") (pinfunction "2_2") (pintype "passive"))
      (node (ref "C46") (pin "2") (pinfunction "2_2") (pintype "passive"))
      (node (ref "C47") (pin "2") (pinfunction "2_2") (pintype "passive"))
      (node (ref "C48") (pin "2") (pinfunction "2_2") (pintype "passive"))
      (node (ref "C49") (pin "2") (pinfunction "2_2") (pintype "passive"))
      (node (ref "C5") (pin "2") (pinfunction "2_2") (pintype "passive"))
      (node (ref "C52") (pin "2") (pinfunction "2_2") (pintype "passive"))
      (node (ref "C53") (pin "2") (pinfunction "2_2") (pintype "passive"))
      (node (ref "C54") (pin "2") (pinfunction "2_2") (pintype "passive"))
      (node (ref "C57") (pin "2") (pinfunction "2_2") (pintype "passive"))
      (node (ref "C58") (pin "2") (pinfunction "2_2") (pintype "passive"))
      (node (ref "C59") (pin "2") (pinfunction "2_2") (pintype "passive"))
      (node (ref "C6") (pin "2") (pinfunction "2_2") (pintype "passive"))
      (node (ref "C61") (pin "2") (pinfunction "2_2") (pintype "passive"))
      (node (ref "C62") (pin "2") (pinfunction "2_2") (pintype "passive"))
      (node (ref "C63") (pin "2") (pinfunction "2_2") (pintype "passive"))
      (node (ref "C64") (pin "1") (pinfunction "1_1") (pintype "passive"))
      (node (ref "C65") (pin "1") (pinfunction "1_1") (pintype "passive"))
      (node (ref "C67") (pin "1") (pinfunction "1_1") (pintype "passive"))
      (node (ref "C68") (pin "1") (pinfunction "1_1") (pintype "passive"))
      (node (ref "C70") (pin "2") (pinfunction "2_2") (pintype "passive"))
      (node (ref "C71") (pin "2") (pinfunction "2_2") (pintype "passive"))
      (node (ref "C72") (pin "2") (pinfunction "2_2") (pintype "passive"))
      (node (ref "C73") (pin "2") (pinfunction "2_2") (pintype "passive"))
      (node (ref "C74") (pin "2") (pinfunction "2_2") (pintype "passive"))
      (node (ref "C75") (pin "2") (pinfunction "2_2") (pintype "passive"))
      (node (ref "C76") (pin "2") (pinfunction "2_2") (pintype "passive"))
      (node (ref "C77") (pin "2") (pinfunction "2_2") (pintype "passive"))
      (node (ref "C78") (pin "2") (pinfunction "2_2") (pintype "passive"))
      (node (ref "C79") (pin "2") (pinfunction "2_2") (pintype "passive"))
      (node (ref "C8") (pin "2") (pinfunction "2_2") (pintype "passive"))
      (node (ref "C80") (pin "2") (pinfunction "2_2") (pintype "passive"))
      (node (ref "C81") (pin "2") (pinfunction "2_2") (pintype "passive"))
      (node (ref "C82") (pin "2") (pinfunction "2_2") (pintype "passive"))
      (node (ref "C83") (pin "2") (pinfunction "2_2") (pintype "passive"))
      (node (ref "C84") (pin "2") (pinfunction "2_2") (pintype "passive"))
      (node (ref "C85") (pin "2") (pinfunction "2_2") (pintype "passive"))
      (node (ref "C86") (pin "2") (pinfunction "2_2") (pintype "passive"))
      (node (ref "C87") (pin "2") (pinfunction "2_2") (pintype "passive"))
      (node (ref "C88") (pin "2") (pinfunction "2_2") (pintype "passive"))
      (node (ref "C89") (pin "2") (pinfunction "2_2") (pintype "passive"))
      (node (ref "C90") (pin "2") (pinfunction "2_2") (pintype "passive"))
      (node (ref "C91") (pin "2") (pinfunction "2_2") (pintype "passive"))
      (node (ref "C92") (pin "2") (pinfunction "2_2") (pintype "passive"))
      (node (ref "C93") (pin "2") (pinfunction "2_2") (pintype "passive"))
      (node (ref "C94") (pin "-") (pinfunction "-_-") (pintype "passive"))
      (node (ref "C95") (pin "-") (pinfunction "-_-") (pintype "passive"))
      (node (ref "C96") (pin "-") (pinfunction "-_-") (pintype "passive"))
      (node (ref "C97") (pin "-") (pinfunction "-_-") (pintype "passive"))
      (node (ref "C98") (pin "-") (pinfunction "-_-") (pintype "passive"))
      (node (ref "D4") (pin "A") (pinfunction "A_A") (pintype "passive"))
      (node (ref "D5") (pin "A") (pinfunction "A_A") (pintype "passive"))
      (node (ref "D6") (pin "A") (pinfunction "A_A") (pintype "passive"))
      (node (ref "IC1") (pin "1") (pinfunction "CLK_1") (pintype "bidirectional"))
      (node (ref "IC1") (pin "10") (pinfunction "SPI_MODE_10") (pintype "bidirectional"))
      (node (ref "IC1") (pin "11") (pinfunction "GND_11") (pintype "bidirectional"))
      (node (ref "IC1") (pin "12") (pinfunction "GND_12") (pintype "bidirectional"))
      (node (ref "IC1") (pin "24") (pinfunction "GNDA_24") (pintype "bidirectional"))
      (node (ref "IC1") (pin "35") (pinfunction "GND_35") (pintype "bidirectional"))
      (node (ref "IC1") (pin "36") (pinfunction "TST_MODE_36") (pintype "bidirectional"))
      (node (ref "IC1") (pin "TP") (pinfunction "GND_TP") (pintype "bidirectional"))
      (node (ref "IC10") (pin "3") (pinfunction "GND_3") (pintype "power_in"))
      (node (ref "IC11") (pin "3") (pinfunction "GND_3") (pintype "power_in"))
      (node (ref "IC12") (pin "1") (pinfunction "CLK_1") (pintype "bidirectional"))
      (node (ref "IC12") (pin "10") (pinfunction "SPI_MODE_10") (pintype "bidirectional"))
      (node (ref "IC12") (pin "11") (pinfunction "GND_11") (pintype "bidirectional"))
      (node (ref "IC12") (pin "12") (pinfunction "GND_12") (pintype "bidirectional"))
      (node (ref "IC12") (pin "24") (pinfunction "GNDA_24") (pintype "bidirectional"))
      (node (ref "IC12") (pin "35") (pinfunction "GND_35") (pintype "bidirectional"))
      (node (ref "IC12") (pin "36") (pinfunction "TST_MODE_36") (pintype "bidirectional"))
      (node (ref "IC12") (pin "TP") (pinfunction "GND_TP") (pintype "bidirectional"))
      (node (ref "IC13") (pin "3") (pinfunction "GND_3") (pintype "power_in"))
      (node (ref "IC14") (pin "3") (pinfunction "GND_3") (pintype "power_in"))
      (node (ref "IC15") (pin "1") (pinfunction "CLK_1") (pintype "bidirectional"))
      (node (ref "IC15") (pin "10") (pinfunction "SPI_MODE_10") (pintype "bidirectional"))
      (node (ref "IC15") (pin "11") (pinfunction "GND_11") (pintype "bidirectional"))
      (node (ref "IC15") (pin "12") (pinfunction "GND_12") (pintype "bidirectional"))
      (node (ref "IC15") (pin "24") (pinfunction "GNDA_24") (pintype "bidirectional"))
      (node (ref "IC15") (pin "35") (pinfunction "GND_35") (pintype "bidirectional"))
      (node (ref "IC15") (pin "36") (pinfunction "TST_MODE_36") (pintype "bidirectional"))
      (node (ref "IC15") (pin "TP") (pinfunction "GND_TP") (pintype "bidirectional"))
      (node (ref "IC16") (pin "3") (pinfunction "GND_3") (pintype "power_in"))
      (node (ref "IC17") (pin "3") (pinfunction "GND_3") (pintype "power_in"))
      (node (ref "IC18") (pin "3") (pinfunction "GND_3") (pintype "power_in"))
      (node (ref "IC19") (pin "3") (pinfunction "GND_3") (pintype "power_in"))
      (node (ref "IC2") (pin "1") (pinfunction "CLK_1") (pintype "bidirectional"))
      (node (ref "IC2") (pin "10") (pinfunction "SPI_MODE_10") (pintype "bidirectional"))
      (node (ref "IC2") (pin "11") (pinfunction "GND_11") (pintype "bidirectional"))
      (node (ref "IC2") (pin "12") (pinfunction "GND_12") (pintype "bidirectional"))
      (node (ref "IC2") (pin "24") (pinfunction "GNDA_24") (pintype "bidirectional"))
      (node (ref "IC2") (pin "35") (pinfunction "GND_35") (pintype "bidirectional"))
      (node (ref "IC2") (pin "36") (pinfunction "TST_MODE_36") (pintype "bidirectional"))
      (node (ref "IC2") (pin "TP") (pinfunction "GND_TP") (pintype "bidirectional"))
      (node (ref "IC20") (pin "3") (pinfunction "GND_3") (pintype "power_in"))
      (node (ref "IC21") (pin "3") (pinfunction "GND_3") (pintype "power_in"))
      (node (ref "IC22") (pin "3") (pinfunction "GND_3") (pintype "power_in"))
      (node (ref "IC3") (pin "3") (pinfunction "GND_3") (pintype "power_in"))
      (node (ref "IC4") (pin "3") (pinfunction "GND_3") (pintype "power_in"))
      (node (ref "IC5") (pin "1") (pinfunction "CLK_1") (pintype "bidirectional"))
      (node (ref "IC5") (pin "10") (pinfunction "SPI_MODE_10") (pintype "bidirectional"))
      (node (ref "IC5") (pin "11") (pinfunction "GND_11") (pintype "bidirectional"))
      (node (ref "IC5") (pin "12") (pinfunction "GND_12") (pintype "bidirectional"))
      (node (ref "IC5") (pin "24") (pinfunction "GNDA_24") (pintype "bidirectional"))
      (node (ref "IC5") (pin "35") (pinfunction "GND_35") (pintype "bidirectional"))
      (node (ref "IC5") (pin "36") (pinfunction "TST_MODE_36") (pintype "bidirectional"))
      (node (ref "IC5") (pin "TP") (pinfunction "GND_TP") (pintype "bidirectional"))
      (node (ref "IC6") (pin "3") (pinfunction "GND_3") (pintype "power_in"))
      (node (ref "IC7") (pin "3") (pinfunction "GND_3") (pintype "power_in"))
      (node (ref "IC8") (pin "3") (pinfunction "GND_3") (pintype "power_in"))
      (node (ref "IC9") (pin "3") (pinfunction "GND_3") (pintype "power_in"))
      (node (ref "LED4") (pin "C") (pinfunction "C_C") (pintype "passive"))
      (node (ref "P8") (pin "1") (pinfunction "1_1") (pintype "passive"))
      (node (ref "P8") (pin "2") (pinfunction "2_2") (pintype "passive"))
      (node (ref "P9") (pin "1") (pinfunction "1_1") (pintype "passive"))
      (node (ref "P9") (pin "2") (pinfunction "2_2") (pintype "passive"))
      (node (ref "P9") (pin "43") (pinfunction "43_43") (pintype "passive"))
      (node (ref "P9") (pin "44") (pinfunction "44_44") (pintype "passive"))
      (node (ref "P9") (pin "45") (pinfunction "45_45") (pintype "passive"))
      (node (ref "P9") (pin "46") (pinfunction "46_46") (pintype "passive"))
      (node (ref "Q1") (pin "1") (pinfunction "S_1") (pintype "passive"))
      (node (ref "Q1") (pin "2") (pinfunction "S_2") (pintype "passive"))
      (node (ref "Q1") (pin "3") (pinfunction "S_3") (pintype "passive"))
      (node (ref "Q2") (pin "1") (pinfunction "S_1") (pintype "passive"))
      (node (ref "Q2") (pin "2") (pinfunction "S_2") (pintype "passive"))
      (node (ref "Q2") (pin "3") (pinfunction "S_3") (pintype "passive"))
      (node (ref "Q3") (pin "1") (pinfunction "S_1") (pintype "passive"))
      (node (ref "Q3") (pin "2") (pinfunction "S_2") (pintype "passive"))
      (node (ref "Q3") (pin "3") (pinfunction "S_3") (pintype "passive"))
      (node (ref "Q4") (pin "2") (pinfunction "E_2") (pintype "passive"))
      (node (ref "Q5") (pin "2") (pinfunction "E_2") (pintype "passive"))
      (node (ref "Q6") (pin "2") (pinfunction "E_2") (pintype "passive"))
      (node (ref "Q7") (pin "2") (pinfunction "E_2") (pintype "passive"))
      (node (ref "R1") (pin "1") (pinfunction "1_1") (pintype "passive"))
      (node (ref "R10") (pin "1") (pinfunction "1_1") (pintype "passive"))
      (node (ref "R2") (pin "1") (pinfunction "1_1") (pintype "passive"))
      (node (ref "R22") (pin "2") (pinfunction "2_2") (pintype "passive"))
      (node (ref "R26") (pin "2") (pinfunction "2_2") (pintype "passive"))
      (node (ref "R29") (pin "1") (pinfunction "1_1") (pintype "passive"))
      (node (ref "R3") (pin "1") (pinfunction "1_1") (pintype "passive"))
      (node (ref "R30") (pin "1") (pinfunction "1_1") (pintype "passive"))
      (node (ref "R32") (pin "1") (pinfunction "1_1") (pintype "passive"))
      (node (ref "R33") (pin "1") (pinfunction "1_1") (pintype "passive"))
      (node (ref "R34") (pin "1") (pinfunction "1_1") (pintype "passive"))
      (node (ref "R4") (pin "1") (pinfunction "1_1") (pintype "passive"))
      (node (ref "R43") (pin "2") (pinfunction "2_2") (pintype "passive"))
      (node (ref "R44") (pin "2") (pinfunction "2_2") (pintype "passive"))
      (node (ref "R46") (pin "1") (pinfunction "1_1") (pintype "passive"))
      (node (ref "R47") (pin "1") (pinfunction "1_1") (pintype "passive"))
      (node (ref "R48") (pin "1") (pinfunction "1_1") (pintype "passive"))
      (node (ref "R5") (pin "1") (pinfunction "1_1") (pintype "passive"))
      (node (ref "R7") (pin "1") (pinfunction "1_1") (pintype "passive"))
      (node (ref "R8") (pin "1") (pinfunction "1_1") (pintype "passive"))
      (node (ref "R9") (pin "1") (pinfunction "1_1") (pintype "passive"))
      (node (ref "U1") (pin "13") (pinfunction "~{OE}_13") (pintype "input"))
      (node (ref "U1") (pin "8") (pinfunction "GND_8") (pintype "passive"))
      (node (ref "U10") (pin "6") (pinfunction "GND_6") (pintype "power_in"))
      (node (ref "U10") (pin "EP") (pinfunction "EP_EP") (pintype "power_in"))
      (node (ref "U11") (pin "14") (pinfunction "VSS_14") (pintype "passive"))
      (node (ref "U18") (pin "1") (pinfunction "A0_1") (pintype "input"))
      (node (ref "U18") (pin "2") (pinfunction "A1_2") (pintype "input"))
      (node (ref "U18") (pin "4") (pinfunction "GND_4") (pintype "power_in"))
      (node (ref "U19") (pin "8") (pinfunction "VSS_8") (pintype "power_in"))
      (node (ref "U2") (pin "13") (pinfunction "~{OE}_13") (pintype "input"))
      (node (ref "U2") (pin "8") (pinfunction "GND_8") (pintype "passive"))
      (node (ref "U3") (pin "13") (pinfunction "~{OE}_13") (pintype "input"))
      (node (ref "U3") (pin "8") (pinfunction "GND_8") (pintype "passive"))
      (node (ref "U4") (pin "13") (pinfunction "~{OE}_13") (pintype "input"))
      (node (ref "U4") (pin "8") (pinfunction "GND_8") (pintype "passive"))
      (node (ref "U5") (pin "13") (pinfunction "~{OE}_13") (pintype "input"))
      (node (ref "U5") (pin "8") (pinfunction "GND_8") (pintype "passive"))
      (node (ref "U6") (pin "6") (pinfunction "GND_6") (pintype "power_in"))
      (node (ref "U6") (pin "EP") (pinfunction "EP_EP") (pintype "power_in"))
      (node (ref "U8") (pin "18") (pinfunction "18_18") (pintype "passive"))
      (node (ref "U8") (pin "23") (pinfunction "23_23") (pintype "passive"))
      (node (ref "U8") (pin "3") (pinfunction "3_3") (pintype "passive"))
      (node (ref "U8") (pin "30") (pinfunction "30_30") (pintype "passive"))
      (node (ref "U8") (pin "41") (pinfunction "41_41") (pintype "passive"))
      (node (ref "U8") (pin "9") (pinfunction "9_9") (pintype "passive"))
      (node (ref "X1") (pin "2") (pinfunction "S_2") (pintype "passive"))
      (node (ref "X10") (pin "2") (pinfunction "S_2") (pintype "passive"))
      (node (ref "X11") (pin "1") (pinfunction "S_1") (pintype "passive"))
      (node (ref "X12") (pin "2") (pinfunction "S_2") (pintype "passive"))
      (node (ref "X13") (pin "2") (pinfunction "S_2") (pintype "passive"))
      (node (ref "X19") (pin "2") (pinfunction "S_2") (pintype "passive"))
      (node (ref "X2") (pin "1") (pinfunction "1_1") (pintype "passive"))
      (node (ref "X2") (pin "2") (pinfunction "1_2") (pintype "passive"))
      (node (ref "X22") (pin "2") (pinfunction "S_2") (pintype "passive"))
      (node (ref "X23") (pin "3") (pinfunction "S_3") (pintype "passive"))
      (node (ref "X7") (pin "1") (pinfunction "S_1") (pintype "passive"))
      (node (ref "X8") (pin "1") (pinfunction "S_1") (pintype "passive"))
    )
    (net (code "83") (name "HEATER_E_OUT") (class "Default")
      (node (ref "C59") (pin "1") (pinfunction "1_1") (pintype "passive"))
      (node (ref "D1") (pin "A") (pinfunction "A_A") (pintype "passive"))
      (node (ref "LED3") (pin "C") (pinfunction "C_C") (pintype "passive"))
      (node (ref "Q3") (pin "5") (pinfunction "D_5") (pintype "passive"))
      (node (ref "Q3") (pin "6") (pinfunction "D_6") (pintype "passive"))
      (node (ref "Q3") (pin "7") (pinfunction "D_7") (pintype "passive"))
      (node (ref "Q3") (pin "8") (pinfunction "D_8") (pintype "passive"))
      (node (ref "Q3") (pin "TH") (pinfunction "D_TH") (pintype "passive"))
      (node (ref "R55") (pin "1") (pinfunction "1_1") (pintype "passive"))
      (node (ref "U8") (pin "31") (pinfunction "31_31") (pintype "passive"))
      (node (ref "U8") (pin "32") (pinfunction "32_32") (pintype "passive"))
      (node (ref "U8") (pin "33") (pinfunction "33_33") (pintype "passive"))
      (node (ref "U8") (pin "34") (pinfunction "34_34") (pintype "passive"))
      (node (ref "U8") (pin "35") (pinfunction "35_35") (pintype "passive"))
      (node (ref "X3") (pin "2") (pinfunction "1_2") (pintype "passive"))
    )
    (net (code "84") (name "Net-(C51-Pad2)") (class "Default")
      (node (ref "C51") (pin "2") (pinfunction "2_2") (pintype "passive"))
      (node (ref "R26") (pin "1") (pinfunction "1_1") (pintype "passive"))
    )
    (net (code "85") (name "Net-(C56-Pad2)") (class "Default")
      (node (ref "C56") (pin "2") (pinfunction "2_2") (pintype "passive"))
      (node (ref "R44") (pin "1") (pinfunction "1_1") (pintype "passive"))
    )
    (net (code "86") (name "Net-(C75-Pad1)") (class "Default")
      (node (ref "C75") (pin "1") (pinfunction "1_1") (pintype "passive"))
      (node (ref "R31") (pin "1") (pinfunction "1_1") (pintype "passive"))
      (node (ref "R50") (pin "2") (pinfunction "2_2") (pintype "passive"))
    )
    (net (code "87") (name "Net-(C76-Pad1)") (class "Default")
      (node (ref "C76") (pin "1") (pinfunction "1_1") (pintype "passive"))
      (node (ref "R37") (pin "1") (pinfunction "1_1") (pintype "passive"))
      (node (ref "R6") (pin "2") (pinfunction "2_2") (pintype "passive"))
    )
    (net (code "88") (name "Net-(C77-Pad1)") (class "Default")
      (node (ref "C77") (pin "1") (pinfunction "1_1") (pintype "passive"))
      (node (ref "R41") (pin "1") (pinfunction "1_1") (pintype "passive"))
      (node (ref "R49") (pin "2") (pinfunction "2_2") (pintype "passive"))
    )
    (net (code "89") (name "Net-(C78-Pad1)") (class "Default")
      (node (ref "C78") (pin "1") (pinfunction "1_1") (pintype "passive"))
      (node (ref "R27") (pin "2") (pinfunction "2_2") (pintype "passive"))
      (node (ref "R58") (pin "1") (pinfunction "1_1") (pintype "passive"))
    )
    (net (code "90") (name "Net-(C79-Pad1)") (class "Default")
      (node (ref "C79") (pin "1") (pinfunction "1_1") (pintype "passive"))
      (node (ref "R35") (pin "2") (pinfunction "2_2") (pintype "passive"))
      (node (ref "R60") (pin "1") (pinfunction "1_1") (pintype "passive"))
    )
    (net (code "91") (name "Net-(IC1-5VOUT)") (class "Default")
      (node (ref "C21") (pin "2") (pinfunction "2_2") (pintype "passive"))
      (node (ref "IC1") (pin "25") (pinfunction "5VOUT_25") (pintype "bidirectional"))
      (node (ref "R53") (pin "1") (pinfunction "1_1") (pintype "passive"))
    )
    (net (code "92") (name "Net-(IC1-AIN_IREF)") (class "Default")
      (node (ref "C12") (pin "1") (pinfunction "1_1") (pintype "passive"))
      (node (ref "IC1") (pin "23") (pinfunction "AIN_IREF_23") (pintype "bidirectional"))
      (node (ref "R49") (pin "1") (pinfunction "1_1") (pintype "passive"))
    )
    (net (code "93") (name "Net-(IC1-BRA)") (class "Default")
      (node (ref "IC1") (pin "33") (pinfunction "BRA_33") (pintype "bidirectional"))
      (node (ref "R2") (pin "2") (pinfunction "2_2") (pintype "passive"))
    )
    (net (code "94") (name "Net-(IC1-BRB)") (class "Default")
      (node (ref "IC1") (pin "14") (pinfunction "BRB_14") (pintype "bidirectional"))
      (node (ref "R1") (pin "2") (pinfunction "2_2") (pintype "passive"))
    )
    (net (code "95") (name "Net-(IC1-CPI)") (class "Default")
      (node (ref "C1") (pin "1") (pinfunction "1_1") (pintype "passive"))
      (node (ref "IC1") (pin "28") (pinfunction "CPI_28") (pintype "bidirectional"))
    )
    (net (code "96") (name "Net-(IC1-CPO)") (class "Default")
      (node (ref "C1") (pin "2") (pinfunction "2_2") (pintype "passive"))
      (node (ref "IC1") (pin "27") (pinfunction "CPO_27") (pintype "bidirectional"))
    )
    (net (code "97") (name "Net-(IC1-ENCA_DCIN_CFG5)") (class "Default")
      (node (ref "IC1") (pin "19") (pinfunction "ENCA_DCIN_CFG5_19") (pintype "bidirectional"))
      (node (ref "U1") (pin "1") (pinfunction "QB_1") (pintype "output"))
    )
    (net (code "98") (name "Net-(IC1-ENCB_DCEN_CFG4)") (class "Default")
      (node (ref "IC1") (pin "18") (pinfunction "ENCB_DCEN_CFG4_18") (pintype "bidirectional"))
      (node (ref "U1") (pin "2") (pinfunction "QC_2") (pintype "output"))
    )
    (net (code "99") (name "Net-(IC1-SCK_CFG2)") (class "Default")
      (node (ref "IC1") (pin "3") (pinfunction "SCK_CFG2_3") (pintype "bidirectional"))
      (node (ref "IC3") (pin "4") (pinfunction "O_4") (pintype "output"))
    )
    (net (code "100") (name "Net-(IC1-SDI_NAI_CFG1)") (class "Default")
      (node (ref "IC1") (pin "4") (pinfunction "SDI_NAI_CFG1_4") (pintype "bidirectional"))
      (node (ref "IC4") (pin "4") (pinfunction "O_4") (pintype "output"))
    )
    (net (code "101") (name "Net-(IC1-SDO_NAO_CFG0)") (class "Default")
      (node (ref "IC1") (pin "5") (pinfunction "SDO_NAO_CFG0_5") (pintype "bidirectional"))
      (node (ref "U1") (pin "3") (pinfunction "QD_3") (pintype "output"))
    )
    (net (code "102") (name "Net-(IC1-VCC)") (class "Default")
      (node (ref "C71") (pin "1") (pinfunction "1_1") (pintype "passive"))
      (node (ref "IC1") (pin "26") (pinfunction "VCC_26") (pintype "bidirectional"))
      (node (ref "R53") (pin "2") (pinfunction "2_2") (pintype "passive"))
    )
    (net (code "103") (name "Net-(IC1-VCP)") (class "Default")
      (node (ref "C22") (pin "1") (pinfunction "1_1") (pintype "passive"))
      (node (ref "IC1") (pin "29") (pinfunction "VCP_29") (pintype "bidirectional"))
    )
    (net (code "104") (name "Net-(IC2-5VOUT)") (class "Default")
      (node (ref "C33") (pin "2") (pinfunction "2_2") (pintype "passive"))
      (node (ref "IC2") (pin "25") (pinfunction "5VOUT_25") (pintype "bidirectional"))
      (node (ref "R59") (pin "1") (pinfunction "1_1") (pintype "passive"))
    )
    (net (code "105") (name "Net-(IC2-AIN_IREF)") (class "Default")
      (node (ref "C18") (pin "1") (pinfunction "1_1") (pintype "passive"))
      (node (ref "IC2") (pin "23") (pinfunction "AIN_IREF_23") (pintype "bidirectional"))
      (node (ref "R6") (pin "1") (pinfunction "1_1") (pintype "passive"))
    )
    (net (code "106") (name "Net-(IC2-BRA)") (class "Default")
      (node (ref "IC2") (pin "33") (pinfunction "BRA_33") (pintype "bidirectional"))
      (node (ref "R4") (pin "2") (pinfunction "2_2") (pintype "passive"))
    )
    (net (code "107") (name "Net-(IC2-BRB)") (class "Default")
      (node (ref "IC2") (pin "14") (pinfunction "BRB_14") (pintype "bidirectional"))
      (node (ref "R3") (pin "2") (pinfunction "2_2") (pintype "passive"))
    )
    (net (code "108") (name "Net-(IC2-CPI)") (class "Default")
      (node (ref "C3") (pin "1") (pinfunction "1_1") (pintype "passive"))
      (node (ref "IC2") (pin "28") (pinfunction "CPI_28") (pintype "bidirectional"))
    )
    (net (code "109") (name "Net-(IC2-CPO)") (class "Default")
      (node (ref "C3") (pin "2") (pinfunction "2_2") (pintype "passive"))
      (node (ref "IC2") (pin "27") (pinfunction "CPO_27") (pintype "bidirectional"))
    )
    (net (code "110") (name "Net-(IC2-ENCA_DCIN_CFG5)") (class "Default")
      (node (ref "IC2") (pin "19") (pinfunction "ENCA_DCIN_CFG5_19") (pintype "bidirectional"))
      (node (ref "U2") (pin "1") (pinfunction "QB_1") (pintype "output"))
    )
    (net (code "111") (name "Net-(IC2-ENCB_DCEN_CFG4)") (class "Default")
      (node (ref "IC2") (pin "18") (pinfunction "ENCB_DCEN_CFG4_18") (pintype "bidirectional"))
      (node (ref "U2") (pin "2") (pinfunction "QC_2") (pintype "output"))
    )
    (net (code "112") (name "Net-(IC2-OA1)") (class "Default")
      (node (ref "IC2") (pin "34") (pinfunction "OA1_34") (pintype "bidirectional"))
      (node (ref "X15") (pin "2") (pinfunction "S_2") (pintype "passive"))
    )
    (net (code "113") (name "Net-(IC2-OA2)") (class "Default")
      (node (ref "IC2") (pin "32") (pinfunction "OA2_32") (pintype "bidirectional"))
      (node (ref "X15") (pin "1") (pinfunction "S_1") (pintype "passive"))
    )
    (net (code "114") (name "Net-(IC2-OB1)") (class "Default")
      (node (ref "IC2") (pin "13") (pinfunction "OB1_13") (pintype "bidirectional"))
      (node (ref "X15") (pin "3") (pinfunction "S_3") (pintype "passive"))
    )
    (net (code "115") (name "Net-(IC2-OB2)") (class "Default")
      (node (ref "IC2") (pin "15") (pinfunction "OB2_15") (pintype "bidirectional"))
      (node (ref "X15") (pin "4") (pinfunction "S_4") (pintype "passive"))
    )
    (net (code "116") (name "Net-(IC2-SCK_CFG2)") (class "Default")
      (node (ref "IC2") (pin "3") (pinfunction "SCK_CFG2_3") (pintype "bidirectional"))
      (node (ref "IC8") (pin "4") (pinfunction "O_4") (pintype "output"))
    )
    (net (code "117") (name "Net-(IC2-SDI_NAI_CFG1)") (class "Default")
      (node (ref "IC2") (pin "4") (pinfunction "SDI_NAI_CFG1_4") (pintype "bidirectional"))
      (node (ref "IC9") (pin "4") (pinfunction "O_4") (pintype "output"))
    )
    (net (code "118") (name "Net-(IC2-SDO_NAO_CFG0)") (class "Default")
      (node (ref "IC2") (pin "5") (pinfunction "SDO_NAO_CFG0_5") (pintype "bidirectional"))
      (node (ref "U2") (pin "3") (pinfunction "QD_3") (pintype "output"))
    )
    (net (code "119") (name "Net-(IC2-VCC)") (class "Default")
      (node (ref "C72") (pin "1") (pinfunction "1_1") (pintype "passive"))
      (node (ref "IC2") (pin "26") (pinfunction "VCC_26") (pintype "bidirectional"))
      (node (ref "R59") (pin "2") (pinfunction "2_2") (pintype "passive"))
    )
    (net (code "120") (name "Net-(IC2-VCP)") (class "Default")
      (node (ref "C35") (pin "1") (pinfunction "1_1") (pintype "passive"))
      (node (ref "IC2") (pin "29") (pinfunction "VCP_29") (pintype "bidirectional"))
    )
    (net (code "121") (name "Net-(IC3A-I)") (class "Default")
      (node (ref "IC3") (pin "2") (pinfunction "I_2") (pintype "input"))
      (node (ref "U1") (pin "4") (pinfunction "QE_4") (pintype "output"))
    )
    (net (code "122") (name "Net-(IC3A-OE)") (class "Default")
      (node (ref "IC3") (pin "1") (pinfunction "OE_1") (pintype "input"))
      (node (ref "U1") (pin "5") (pinfunction "QF_5") (pintype "output"))
    )
    (net (code "123") (name "Net-(IC4A-I)") (class "Default")
      (node (ref "IC4") (pin "2") (pinfunction "I_2") (pintype "input"))
      (node (ref "U1") (pin "6") (pinfunction "QG_6") (pintype "output"))
    )
    (net (code "124") (name "Net-(IC4A-OE)") (class "Default")
      (node (ref "IC4") (pin "1") (pinfunction "OE_1") (pintype "input"))
      (node (ref "U1") (pin "7") (pinfunction "QH_7") (pintype "output"))
    )
    (net (code "125") (name "Net-(IC5-5VOUT)") (class "Default")
      (node (ref "C37") (pin "2") (pinfunction "2_2") (pintype "passive"))
      (node (ref "IC5") (pin "25") (pinfunction "5VOUT_25") (pintype "bidirectional"))
      (node (ref "R70") (pin "1") (pinfunction "1_1") (pintype "passive"))
    )
    (net (code "126") (name "Net-(IC5-AIN_IREF)") (class "Default")
      (node (ref "C25") (pin "1") (pinfunction "1_1") (pintype "passive"))
      (node (ref "IC5") (pin "23") (pinfunction "AIN_IREF_23") (pintype "bidirectional"))
      (node (ref "R27") (pin "1") (pinfunction "1_1") (pintype "passive"))
    )
    (net (code "127") (name "Net-(IC5-BRA)") (class "Default")
      (node (ref "IC5") (pin "33") (pinfunction "BRA_33") (pintype "bidirectional"))
      (node (ref "R8") (pin "2") (pinfunction "2_2") (pintype "passive"))
    )
    (net (code "128") (name "Net-(IC5-BRB)") (class "Default")
      (node (ref "IC5") (pin "14") (pinfunction "BRB_14") (pintype "bidirectional"))
      (node (ref "R7") (pin "2") (pinfunction "2_2") (pintype "passive"))
    )
    (net (code "129") (name "Net-(IC5-CPI)") (class "Default")
      (node (ref "C7") (pin "1") (pinfunction "1_1") (pintype "passive"))
      (node (ref "IC5") (pin "28") (pinfunction "CPI_28") (pintype "bidirectional"))
    )
    (net (code "130") (name "Net-(IC5-CPO)") (class "Default")
      (node (ref "C7") (pin "2") (pinfunction "2_2") (pintype "passive"))
      (node (ref "IC5") (pin "27") (pinfunction "CPO_27") (pintype "bidirectional"))
    )
    (net (code "131") (name "Net-(IC5-ENCA_DCIN_CFG5)") (class "Default")
      (node (ref "IC5") (pin "19") (pinfunction "ENCA_DCIN_CFG5_19") (pintype "bidirectional"))
      (node (ref "U3") (pin "1") (pinfunction "QB_1") (pintype "output"))
    )
    (net (code "132") (name "Net-(IC5-ENCB_DCEN_CFG4)") (class "Default")
      (node (ref "IC5") (pin "18") (pinfunction "ENCB_DCEN_CFG4_18") (pintype "bidirectional"))
      (node (ref "U3") (pin "2") (pinfunction "QC_2") (pintype "output"))
    )
    (net (code "133") (name "Net-(IC5-OA1)") (class "Default")
      (node (ref "IC5") (pin "34") (pinfunction "OA1_34") (pintype "bidirectional"))
      (node (ref "X16") (pin "2") (pinfunction "S_2") (pintype "passive"))
    )
    (net (code "134") (name "Net-(IC5-OA2)") (class "Default")
      (node (ref "IC5") (pin "32") (pinfunction "OA2_32") (pintype "bidirectional"))
      (node (ref "X16") (pin "1") (pinfunction "S_1") (pintype "passive"))
    )
    (net (code "135") (name "Net-(IC5-OB1)") (class "Default")
      (node (ref "IC5") (pin "13") (pinfunction "OB1_13") (pintype "bidirectional"))
      (node (ref "X16") (pin "3") (pinfunction "S_3") (pintype "passive"))
    )
    (net (code "136") (name "Net-(IC5-OB2)") (class "Default")
      (node (ref "IC5") (pin "15") (pinfunction "OB2_15") (pintype "bidirectional"))
      (node (ref "X16") (pin "4") (pinfunction "S_4") (pintype "passive"))
    )
    (net (code "137") (name "Net-(IC5-SDO_NAO_CFG0)") (class "Default")
      (node (ref "IC5") (pin "5") (pinfunction "SDO_NAO_CFG0_5") (pintype "bidirectional"))
      (node (ref "U3") (pin "3") (pinfunction "QD_3") (pintype "output"))
    )
    (net (code "138") (name "Net-(IC5-VCC)") (class "Default")
      (node (ref "C73") (pin "1") (pinfunction "1_1") (pintype "passive"))
      (node (ref "IC5") (pin "26") (pinfunction "VCC_26") (pintype "bidirectional"))
      (node (ref "R70") (pin "2") (pinfunction "2_2") (pintype "passive"))
    )
    (net (code "139") (name "Net-(IC5-VCP)") (class "Default")
      (node (ref "C38") (pin "1") (pinfunction "1_1") (pintype "passive"))
      (node (ref "IC5") (pin "29") (pinfunction "VCP_29") (pintype "bidirectional"))
    )
    (net (code "140") (name "Net-(IC8A-I)") (class "Default")
      (node (ref "IC8") (pin "2") (pinfunction "I_2") (pintype "input"))
      (node (ref "U2") (pin "4") (pinfunction "QE_4") (pintype "output"))
    )
    (net (code "141") (name "Net-(IC8A-OE)") (class "Default")
      (node (ref "IC8") (pin "1") (pinfunction "OE_1") (pintype "input"))
      (node (ref "U2") (pin "5") (pinfunction "QF_5") (pintype "output"))
    )
    (net (code "142") (name "Net-(IC9A-I)") (class "Default")
      (node (ref "IC9") (pin "2") (pinfunction "I_2") (pintype "input"))
      (node (ref "U2") (pin "6") (pinfunction "QG_6") (pintype "output"))
    )
    (net (code "143") (name "Net-(IC9A-OE)") (class "Default")
      (node (ref "IC9") (pin "1") (pinfunction "OE_1") (pintype "input"))
      (node (ref "U2") (pin "7") (pinfunction "QH_7") (pintype "output"))
    )
    (net (code "144") (name "Net-(IC10A-I)") (class "Default")
      (node (ref "IC10") (pin "2") (pinfunction "I_2") (pintype "input"))
      (node (ref "U3") (pin "4") (pinfunction "QE_4") (pintype "output"))
    )
    (net (code "145") (name "Net-(IC10A-O)") (class "Default")
      (node (ref "IC10") (pin "4") (pinfunction "O_4") (pintype "output"))
      (node (ref "IC5") (pin "3") (pinfunction "SCK_CFG2_3") (pintype "bidirectional"))
    )
    (net (code "146") (name "Net-(IC10A-OE)") (class "Default")
      (node (ref "IC10") (pin "1") (pinfunction "OE_1") (pintype "input"))
      (node (ref "U3") (pin "5") (pinfunction "QF_5") (pintype "output"))
    )
    (net (code "147") (name "Net-(IC11A-I)") (class "Default")
      (node (ref "IC11") (pin "2") (pinfunction "I_2") (pintype "input"))
      (node (ref "U3") (pin "6") (pinfunction "QG_6") (pintype "output"))
    )
    (net (code "148") (name "Net-(IC11A-O)") (class "Default")
      (node (ref "IC11") (pin "4") (pinfunction "O_4") (pintype "output"))
      (node (ref "IC5") (pin "4") (pinfunction "SDI_NAI_CFG1_4") (pintype "bidirectional"))
    )
    (net (code "149") (name "Net-(IC11A-OE)") (class "Default")
      (node (ref "IC11") (pin "1") (pinfunction "OE_1") (pintype "input"))
      (node (ref "U3") (pin "7") (pinfunction "QH_7") (pintype "output"))
    )
    (net (code "150") (name "Net-(IC12-5VOUT)") (class "Default")
      (node (ref "C65") (pin "2") (pinfunction "2_2") (pintype "passive"))
      (node (ref "IC12") (pin "25") (pinfunction "5VOUT_25") (pintype "bidirectional"))
      (node (ref "R71") (pin "1") (pinfunction "1_1") (pintype "passive"))
    )
    (net (code "151") (name "Net-(IC12-AIN_IREF)") (class "Default")
      (node (ref "C62") (pin "1") (pinfunction "1_1") (pintype "passive"))
      (node (ref "IC12") (pin "23") (pinfunction "AIN_IREF_23") (pintype "bidirectional"))
      (node (ref "R35") (pin "1") (pinfunction "1_1") (pintype "passive"))
    )
    (net (code "152") (name "Net-(IC12-BRA)") (class "Default")
      (node (ref "IC12") (pin "33") (pinfunction "BRA_33") (pintype "bidirectional"))
      (node (ref "R30") (pin "2") (pinfunction "2_2") (pintype "passive"))
    )
    (net (code "153") (name "Net-(IC12-BRB)") (class "Default")
      (node (ref "IC12") (pin "14") (pinfunction "BRB_14") (pintype "bidirectional"))
      (node (ref "R29") (pin "2") (pinfunction "2_2") (pintype "passive"))
    )
    (net (code "154") (name "Net-(IC12-CPI)") (class "Default")
      (node (ref "C39") (pin "1") (pinfunction "1_1") (pintype "passive"))
      (node (ref "IC12") (pin "28") (pinfunction "CPI_28") (pintype "bidirectional"))
    )
    (net (code "155") (name "Net-(IC12-CPO)") (class "Default")
      (node (ref "C39") (pin "2") (pinfunction "2_2") (pintype "passive"))
      (node (ref "IC12") (pin "27") (pinfunction "CPO_27") (pintype "bidirectional"))
    )
    (net (code "156") (name "Net-(IC12-ENCA_DCIN_CFG5)") (class "Default")
      (node (ref "IC12") (pin "19") (pinfunction "ENCA_DCIN_CFG5_19") (pintype "bidirectional"))
      (node (ref "U4") (pin "1") (pinfunction "QB_1") (pintype "output"))
    )
    (net (code "157") (name "Net-(IC12-ENCB_DCEN_CFG4)") (class "Default")
      (node (ref "IC12") (pin "18") (pinfunction "ENCB_DCEN_CFG4_18") (pintype "bidirectional"))
      (node (ref "U4") (pin "2") (pinfunction "QC_2") (pintype "output"))
    )
    (net (code "158") (name "Net-(IC12-SCK_CFG2)") (class "Default")
      (node (ref "IC12") (pin "3") (pinfunction "SCK_CFG2_3") (pintype "bidirectional"))
      (node (ref "IC13") (pin "4") (pinfunction "O_4") (pintype "output"))
    )
    (net (code "159") (name "Net-(IC12-SDI_NAI_CFG1)") (class "Default")
      (node (ref "IC12") (pin "4") (pinfunction "SDI_NAI_CFG1_4") (pintype "bidirectional"))
      (node (ref "IC14") (pin "4") (pinfunction "O_4") (pintype "output"))
    )
    (net (code "160") (name "Net-(IC12-SDO_NAO_CFG0)") (class "Default")
      (node (ref "IC12") (pin "5") (pinfunction "SDO_NAO_CFG0_5") (pintype "bidirectional"))
      (node (ref "U4") (pin "3") (pinfunction "QD_3") (pintype "output"))
    )
    (net (code "161") (name "Net-(IC12-VCC)") (class "Default")
      (node (ref "C74") (pin "1") (pinfunction "1_1") (pintype "passive"))
      (node (ref "IC12") (pin "26") (pinfunction "VCC_26") (pintype "bidirectional"))
      (node (ref "R71") (pin "2") (pinfunction "2_2") (pintype "passive"))
    )
    (net (code "162") (name "Net-(IC12-VCP)") (class "Default")
      (node (ref "C66") (pin "1") (pinfunction "1_1") (pintype "passive"))
      (node (ref "IC12") (pin "29") (pinfunction "VCP_29") (pintype "bidirectional"))
    )
    (net (code "163") (name "Net-(IC13A-I)") (class "Default")
      (node (ref "IC13") (pin "2") (pinfunction "I_2") (pintype "input"))
      (node (ref "U4") (pin "4") (pinfunction "QE_4") (pintype "output"))
    )
    (net (code "164") (name "Net-(IC13A-OE)") (class "Default")
      (node (ref "IC13") (pin "1") (pinfunction "OE_1") (pintype "input"))
      (node (ref "U4") (pin "5") (pinfunction "QF_5") (pintype "output"))
    )
    (net (code "165") (name "Net-(IC14A-I)") (class "Default")
      (node (ref "IC14") (pin "2") (pinfunction "I_2") (pintype "input"))
      (node (ref "U4") (pin "6") (pinfunction "QG_6") (pintype "output"))
    )
    (net (code "166") (name "Net-(IC14A-OE)") (class "Default")
      (node (ref "IC14") (pin "1") (pinfunction "OE_1") (pintype "input"))
      (node (ref "U4") (pin "7") (pinfunction "QH_7") (pintype "output"))
    )
    (net (code "167") (name "Net-(IC15-5VOUT)") (class "Default")
      (node (ref "C68") (pin "2") (pinfunction "2_2") (pintype "passive"))
      (node (ref "IC15") (pin "25") (pinfunction "5VOUT_25") (pintype "bidirectional"))
      (node (ref "R52") (pin "1") (pinfunction "1_1") (pintype "passive"))
    )
    (net (code "168") (name "Net-(IC15-AIN_IREF)") (class "Default")
      (node (ref "C36") (pin "1") (pinfunction "1_1") (pintype "passive"))
      (node (ref "IC15") (pin "23") (pinfunction "AIN_IREF_23") (pintype "bidirectional"))
      (node (ref "R50") (pin "1") (pinfunction "1_1") (pintype "passive"))
    )
    (net (code "169") (name "Net-(IC15-BRA)") (class "Default")
      (node (ref "IC15") (pin "33") (pinfunction "BRA_33") (pintype "bidirectional"))
      (node (ref "R10") (pin "2") (pinfunction "2_2") (pintype "passive"))
    )
    (net (code "170") (name "Net-(IC15-BRB)") (class "Default")
      (node (ref "IC15") (pin "14") (pinfunction "BRB_14") (pintype "bidirectional"))
      (node (ref "R9") (pin "2") (pinfunction "2_2") (pintype "passive"))
    )
    (net (code "171") (name "Net-(IC15-CPI)") (class "Default")
      (node (ref "C9") (pin "1") (pinfunction "1_1") (pintype "passive"))
      (node (ref "IC15") (pin "28") (pinfunction "CPI_28") (pintype "bidirectional"))
    )
    (net (code "172") (name "Net-(IC15-CPO)") (class "Default")
      (node (ref "C9") (pin "2") (pinfunction "2_2") (pintype "passive"))
      (node (ref "IC15") (pin "27") (pinfunction "CPO_27") (pintype "bidirectional"))
    )
    (net (code "173") (name "Net-(IC15-ENCA_DCIN_CFG5)") (class "Default")
      (node (ref "IC15") (pin "19") (pinfunction "ENCA_DCIN_CFG5_19") (pintype "bidirectional"))
      (node (ref "U5") (pin "1") (pinfunction "QB_1") (pintype "output"))
    )
    (net (code "174") (name "Net-(IC15-ENCB_DCEN_CFG4)") (class "Default")
      (node (ref "IC15") (pin "18") (pinfunction "ENCB_DCEN_CFG4_18") (pintype "bidirectional"))
      (node (ref "U5") (pin "2") (pinfunction "QC_2") (pintype "output"))
    )
    (net (code "175") (name "Net-(IC15-OA1)") (class "Default")
      (node (ref "IC15") (pin "34") (pinfunction "OA1_34") (pintype "bidirectional"))
      (node (ref "X18") (pin "2") (pinfunction "S_2") (pintype "passive"))
    )
    (net (code "176") (name "Net-(IC15-OA2)") (class "Default")
      (node (ref "IC15") (pin "32") (pinfunction "OA2_32") (pintype "bidirectional"))
      (node (ref "X18") (pin "1") (pinfunction "S_1") (pintype "passive"))
    )
    (net (code "177") (name "Net-(IC15-OB1)") (class "Default")
      (node (ref "IC15") (pin "13") (pinfunction "OB1_13") (pintype "bidirectional"))
      (node (ref "X18") (pin "3") (pinfunction "S_3") (pintype "passive"))
    )
    (net (code "178") (name "Net-(IC15-OB2)") (class "Default")
      (node (ref "IC15") (pin "15") (pinfunction "OB2_15") (pintype "bidirectional"))
      (node (ref "X18") (pin "4") (pinfunction "S_4") (pintype "passive"))
    )
    (net (code "179") (name "Net-(IC15-SCK_CFG2)") (class "Default")
      (node (ref "IC15") (pin "3") (pinfunction "SCK_CFG2_3") (pintype "bidirectional"))
      (node (ref "IC16") (pin "4") (pinfunction "O_4") (pintype "output"))
    )
    (net (code "180") (name "Net-(IC15-SDI_NAI_CFG1)") (class "Default")
      (node (ref "IC15") (pin "4") (pinfunction "SDI_NAI_CFG1_4") (pintype "bidirectional"))
      (node (ref "IC17") (pin "4") (pinfunction "O_4") (pintype "output"))
    )
    (net (code "181") (name "Net-(IC15-SDO_NAO_CFG0)") (class "Default")
      (node (ref "IC15") (pin "5") (pinfunction "SDO_NAO_CFG0_5") (pintype "bidirectional"))
      (node (ref "U5") (pin "3") (pinfunction "QD_3") (pintype "output"))
    )
    (net (code "182") (name "Net-(IC15-VCC)") (class "Default")
      (node (ref "C70") (pin "1") (pinfunction "1_1") (pintype "passive"))
      (node (ref "IC15") (pin "26") (pinfunction "VCC_26") (pintype "bidirectional"))
      (node (ref "R52") (pin "2") (pinfunction "2_2") (pintype "passive"))
    )
    (net (code "183") (name "Net-(IC15-VCP)") (class "Default")
      (node (ref "C69") (pin "1") (pinfunction "1_1") (pintype "passive"))
      (node (ref "IC15") (pin "29") (pinfunction "VCP_29") (pintype "bidirectional"))
    )
    (net (code "184") (name "Net-(IC16A-I)") (class "Default")
      (node (ref "IC16") (pin "2") (pinfunction "I_2") (pintype "input"))
      (node (ref "U5") (pin "4") (pinfunction "QE_4") (pintype "output"))
    )
    (net (code "185") (name "Net-(IC16A-OE)") (class "Default")
      (node (ref "IC16") (pin "1") (pinfunction "OE_1") (pintype "input"))
      (node (ref "U5") (pin "5") (pinfunction "QF_5") (pintype "output"))
    )
    (net (code "186") (name "Net-(IC17A-I)") (class "Default")
      (node (ref "IC17") (pin "2") (pinfunction "I_2") (pintype "input"))
      (node (ref "U5") (pin "6") (pinfunction "QG_6") (pintype "output"))
    )
    (net (code "187") (name "Net-(IC17A-OE)") (class "Default")
      (node (ref "IC17") (pin "1") (pinfunction "OE_1") (pintype "input"))
      (node (ref "U5") (pin "7") (pinfunction "QH_7") (pintype "output"))
    )
    (net (code "188") (name "Net-(LED0-PadA)") (class "Default")
      (node (ref "LED0") (pin "A") (pinfunction "A_A") (pintype "passive"))
      (node (ref "R25") (pin "1") (pinfunction "1_1") (pintype "passive"))
    )
    (net (code "189") (name "Net-(LED1-PadA)") (class "Default")
      (node (ref "LED1") (pin "A") (pinfunction "A_A") (pintype "passive"))
      (node (ref "R14") (pin "1") (pinfunction "1_1") (pintype "passive"))
    )
    (net (code "190") (name "Net-(LED2-PadA)") (class "Default")
      (node (ref "LED2") (pin "A") (pinfunction "A_A") (pintype "passive"))
      (node (ref "R16") (pin "1") (pinfunction "1_1") (pintype "passive"))
    )
    (net (code "191") (name "Net-(LED3-PadA)") (class "Default")
      (node (ref "LED3") (pin "A") (pinfunction "A_A") (pintype "passive"))
      (node (ref "R15") (pin "1") (pinfunction "1_1") (pintype "passive"))
    )
    (net (code "192") (name "Net-(LED4-PadA)") (class "Default")
      (node (ref "LED4") (pin "A") (pinfunction "A_A") (pintype "passive"))
      (node (ref "R11") (pin "1") (pinfunction "1_1") (pintype "passive"))
    )
    (net (code "193") (name "Net-(LED5-PadA)") (class "Default")
      (node (ref "LED5") (pin "A") (pinfunction "A_A") (pintype "passive"))
      (node (ref "R19") (pin "1") (pinfunction "1_1") (pintype "passive"))
    )
    (net (code "194") (name "Net-(LED6-PadA)") (class "Default")
      (node (ref "LED6") (pin "A") (pinfunction "A_A") (pintype "passive"))
      (node (ref "R20") (pin "1") (pinfunction "1_1") (pintype "passive"))
    )
    (net (code "195") (name "Net-(LED7-PadA)") (class "Default")
      (node (ref "LED7") (pin "A") (pinfunction "A_A") (pintype "passive"))
      (node (ref "R21") (pin "1") (pinfunction "1_1") (pintype "passive"))
    )
    (net (code "196") (name "Net-(LED8-PadC)") (class "Default")
      (node (ref "LED8") (pin "C") (pinfunction "C_C") (pintype "passive"))
      (node (ref "R45") (pin "2") (pinfunction "2_2") (pintype "passive"))
    )
    (net (code "197") (name "Net-(Q4-C)") (class "Default")
      (node (ref "LED6") (pin "C") (pinfunction "C_C") (pintype "passive"))
      (node (ref "Q4") (pin "3") (pinfunction "C_3") (pintype "passive"))
      (node (ref "X5") (pin "2") (pinfunction "S_2") (pintype "passive"))
    )
    (net (code "198") (name "Net-(Q5-C)") (class "Default")
      (node (ref "LED7") (pin "C") (pinfunction "C_C") (pintype "passive"))
      (node (ref "Q5") (pin "3") (pinfunction "C_3") (pintype "passive"))
      (node (ref "X6") (pin "2") (pinfunction "S_2") (pintype "passive"))
    )
    (net (code "199") (name "Net-(U6-BOOT)") (class "Default")
      (node (ref "C50") (pin "1") (pinfunction "1_1") (pintype "passive"))
      (node (ref "U6") (pin "2") (pinfunction "BOOT_2") (pintype "input"))
    )
    (net (code "200") (name "Net-(U6-COMP)") (class "Default")
      (node (ref "C51") (pin "1") (pinfunction "1_1") (pintype "passive"))
      (node (ref "U6") (pin "8") (pinfunction "COMP_8") (pintype "bidirectional"))
    )
    (net (code "201") (name "Net-(U6-FB)") (class "Default")
      (node (ref "R12") (pin "2") (pinfunction "2_2") (pintype "passive"))
      (node (ref "R22") (pin "1") (pinfunction "1_1") (pintype "passive"))
      (node (ref "U6") (pin "7") (pinfunction "FB_7") (pintype "input"))
    )
    (net (code "202") (name "Net-(U6-SS)") (class "Default")
      (node (ref "C49") (pin "1") (pinfunction "1_1") (pintype "passive"))
      (node (ref "U6") (pin "10") (pinfunction "SS_10") (pintype "bidirectional"))
    )
    (net (code "203") (name "Net-(U6-SW)") (class "Default")
      (node (ref "C50") (pin "2") (pinfunction "2_2") (pintype "passive"))
      (node (ref "D6") (pin "C") (pinfunction "C_C") (pintype "passive"))
      (node (ref "L1") (pin "P$2") (pinfunction "P$2_P$2") (pintype "passive"))
      (node (ref "U6") (pin "5") (pinfunction "SW_5") (pintype "power_in"))
    )
    (net (code "204") (name "Net-(U10-BOOT)") (class "Default")
      (node (ref "C55") (pin "1") (pinfunction "1_1") (pintype "passive"))
      (node (ref "U10") (pin "2") (pinfunction "BOOT_2") (pintype "input"))
    )
    (net (code "205") (name "Net-(U10-COMP)") (class "Default")
      (node (ref "C56") (pin "1") (pinfunction "1_1") (pintype "passive"))
      (node (ref "U10") (pin "8") (pinfunction "COMP_8") (pintype "bidirectional"))
    )
    (net (code "206") (name "Net-(U10-FB)") (class "Default")
      (node (ref "R42") (pin "2") (pinfunction "2_2") (pintype "passive"))
      (node (ref "R43") (pin "1") (pinfunction "1_1") (pintype "passive"))
      (node (ref "U10") (pin "7") (pinfunction "FB_7") (pintype "input"))
    )
    (net (code "207") (name "Net-(U10-SS)") (class "Default")
      (node (ref "C54") (pin "1") (pinfunction "1_1") (pintype "passive"))
      (node (ref "U10") (pin "10") (pinfunction "SS_10") (pintype "bidirectional"))
    )
    (net (code "208") (name "Net-(U10-SW)") (class "Default")
      (node (ref "C55") (pin "2") (pinfunction "2_2") (pintype "passive"))
      (node (ref "D4") (pin "C") (pinfunction "C_C") (pintype "passive"))
      (node (ref "L2") (pin "P$2") (pinfunction "P$2_P$2") (pintype "passive"))
      (node (ref "U10") (pin "5") (pinfunction "SW_5") (pintype "power_in"))
    )
    (net (code "209") (name "Net-(U11-LED0)") (class "Default")
      (node (ref "SV2") (pin "1") (pinfunction "1_1") (pintype "passive"))
      (node (ref "U11") (pin "6") (pinfunction "LED0_6") (pintype "output"))
    )
    (net (code "210") (name "Net-(U11-LED1)") (class "Default")
      (node (ref "SV2") (pin "2") (pinfunction "2_2") (pintype "passive"))
      (node (ref "U11") (pin "7") (pinfunction "LED1_7") (pintype "output"))
    )
    (net (code "211") (name "Net-(U11-LED2)") (class "Default")
      (node (ref "SV2") (pin "3") (pinfunction "3_3") (pintype "passive"))
      (node (ref "U11") (pin "8") (pinfunction "LED2_8") (pintype "output"))
    )
    (net (code "212") (name "Net-(X7B-S)") (class "Default")
      (node (ref "R17") (pin "1") (pinfunction "1_1") (pintype "passive"))
      (node (ref "R39") (pin "1") (pinfunction "1_1") (pintype "passive"))
      (node (ref "X7") (pin "2") (pinfunction "S_2") (pintype "passive"))
    )
    (net (code "213") (name "Net-(X11B-S)") (class "Default")
      (node (ref "R18") (pin "1") (pinfunction "1_1") (pintype "passive"))
      (node (ref "R40") (pin "1") (pinfunction "1_1") (pintype "passive"))
      (node (ref "X11") (pin "2") (pinfunction "S_2") (pintype "passive"))
    )
    (net (code "214") (name "Net-(X20C-1)") (class "Default")
      (node (ref "C58") (pin "1") (pinfunction "1_1") (pintype "passive"))
      (node (ref "D2") (pin "A") (pinfunction "A_A") (pintype "passive"))
      (node (ref "LED2") (pin "C") (pinfunction "C_C") (pintype "passive"))
      (node (ref "Q1") (pin "5") (pinfunction "D_5") (pintype "passive"))
      (node (ref "Q1") (pin "6") (pinfunction "D_6") (pintype "passive"))
      (node (ref "Q1") (pin "7") (pinfunction "D_7") (pintype "passive"))
      (node (ref "Q1") (pin "8") (pinfunction "D_8") (pintype "passive"))
      (node (ref "Q1") (pin "TH") (pinfunction "D_TH") (pintype "passive"))
      (node (ref "R56") (pin "1") (pinfunction "1_1") (pintype "passive"))
      (node (ref "X20") (pin "3") (pinfunction "1_3") (pintype "passive"))
      (node (ref "X20") (pin "4") (pinfunction "1_4") (pintype "passive"))
    )
    (net (code "215") (name "Net-(X21B-1)") (class "Default")
      (node (ref "C57") (pin "1") (pinfunction "1_1") (pintype "passive"))
      (node (ref "D3") (pin "A") (pinfunction "A_A") (pintype "passive"))
      (node (ref "LED1") (pin "C") (pinfunction "C_C") (pintype "passive"))
      (node (ref "Q2") (pin "5") (pinfunction "D_5") (pintype "passive"))
      (node (ref "Q2") (pin "6") (pinfunction "D_6") (pintype "passive"))
      (node (ref "Q2") (pin "7") (pinfunction "D_7") (pintype "passive"))
      (node (ref "Q2") (pin "8") (pinfunction "D_8") (pintype "passive"))
      (node (ref "Q2") (pin "TH") (pinfunction "D_TH") (pintype "passive"))
      (node (ref "R57") (pin "1") (pinfunction "1_1") (pintype "passive"))
      (node (ref "X21") (pin "2") (pinfunction "1_2") (pintype "passive"))
    )
    (net (code "216") (name "THERM_EXT1_IN") (class "Default")
      (node (ref "R13") (pin "1") (pinfunction "1_1") (pintype "passive"))
      (node (ref "R38") (pin "1") (pinfunction "1_1") (pintype "passive"))
      (node (ref "U8") (pin "28") (pinfunction "28_28") (pintype "passive"))
      (node (ref "X8") (pin "2") (pinfunction "S_2") (pintype "passive"))
    )
    (net (code "217") (name "VDD_12V") (class "Default")
      (node (ref "12V") (pin "TP") (pinfunction "TP_TP") (pintype "input"))
      (node (ref "C53") (pin "1") (pinfunction "1_1") (pintype "passive"))
      (node (ref "C81") (pin "1") (pinfunction "1_1") (pintype "passive"))
      (node (ref "L2") (pin "P$1") (pinfunction "P$1_P$1") (pintype "passive"))
      (node (ref "R11") (pin "2") (pinfunction "2_2") (pintype "passive"))
      (node (ref "R42") (pin "1") (pinfunction "1_1") (pintype "passive"))
      (node (ref "U8") (pin "12") (pinfunction "12_12") (pintype "passive"))
      (node (ref "U8") (pin "16") (pinfunction "16_16") (pintype "passive"))
      (node (ref "U8") (pin "17") (pinfunction "17_17") (pintype "passive"))
      (node (ref "X12") (pin "4") (pinfunction "S_4") (pintype "passive"))
    )
    (net (code "218") (name "VDD_IN") (class "Default")
      (node (ref "12..24V") (pin "TP") (pinfunction "TP_TP") (pintype "input"))
      (node (ref "C10") (pin "1") (pinfunction "1_1") (pintype "passive"))
      (node (ref "C19") (pin "1") (pinfunction "1_1") (pintype "passive"))
      (node (ref "C20") (pin "2") (pinfunction "2_2") (pintype "passive"))
      (node (ref "C22") (pin "2") (pinfunction "2_2") (pintype "passive"))
      (node (ref "C27") (pin "1") (pinfunction "1_1") (pintype "passive"))
      (node (ref "C28") (pin "2") (pinfunction "2_2") (pintype "passive"))
      (node (ref "C29") (pin "1") (pinfunction "1_1") (pintype "passive"))
      (node (ref "C31") (pin "1") (pinfunction "1_1") (pintype "passive"))
      (node (ref "C32") (pin "2") (pinfunction "2_2") (pintype "passive"))
      (node (ref "C35") (pin "2") (pinfunction "2_2") (pintype "passive"))
      (node (ref "C38") (pin "2") (pinfunction "2_2") (pintype "passive"))
      (node (ref "C4") (pin "1") (pinfunction "1_1") (pintype "passive"))
      (node (ref "C40") (pin "1") (pinfunction "1_1") (pintype "passive"))
      (node (ref "C43") (pin "1") (pinfunction "1_1") (pintype "passive"))
      (node (ref "C47") (pin "1") (pinfunction "1_1") (pintype "passive"))
      (node (ref "C52") (pin "1") (pinfunction "1_1") (pintype "passive"))
      (node (ref "C6") (pin "1") (pinfunction "1_1") (pintype "passive"))
      (node (ref "C64") (pin "2") (pinfunction "2_2") (pintype "passive"))
      (node (ref "C66") (pin "2") (pinfunction "2_2") (pintype "passive"))
      (node (ref "C67") (pin "2") (pinfunction "2_2") (pintype "passive"))
      (node (ref "C69") (pin "2") (pinfunction "2_2") (pintype "passive"))
      (node (ref "C8") (pin "1") (pinfunction "1_1") (pintype "passive"))
      (node (ref "C89") (pin "1") (pinfunction "1_1") (pintype "passive"))
      (node (ref "C90") (pin "1") (pinfunction "1_1") (pintype "passive"))
      (node (ref "C91") (pin "1") (pinfunction "1_1") (pintype "passive"))
      (node (ref "C92") (pin "1") (pinfunction "1_1") (pintype "passive"))
      (node (ref "C93") (pin "1") (pinfunction "1_1") (pintype "passive"))
      (node (ref "C94") (pin "+") (pinfunction "+_+") (pintype "passive"))
      (node (ref "C95") (pin "+") (pinfunction "+_+") (pintype "passive"))
      (node (ref "C96") (pin "+") (pinfunction "+_+") (pintype "passive"))
      (node (ref "C97") (pin "+") (pinfunction "+_+") (pintype "passive"))
      (node (ref "C98") (pin "+") (pinfunction "+_+") (pintype "passive"))
      (node (ref "D1") (pin "C") (pinfunction "C_C") (pintype "passive"))
      (node (ref "D2") (pin "C") (pinfunction "C_C") (pintype "passive"))
      (node (ref "D3") (pin "C") (pinfunction "C_C") (pintype "passive"))
      (node (ref "D5") (pin "C") (pinfunction "C_C") (pintype "passive"))
      (node (ref "F1") (pin "P$3") (pinfunction "2_P$3") (pintype "passive"))
      (node (ref "F1") (pin "P$4") (pinfunction "2_P$4") (pintype "passive"))
      (node (ref "IC1") (pin "16") (pinfunction "VS_16") (pintype "bidirectional"))
      (node (ref "IC1") (pin "30") (pinfunction "VSA_30") (pintype "bidirectional"))
      (node (ref "IC1") (pin "31") (pinfunction "VS_31") (pintype "bidirectional"))
      (node (ref "IC12") (pin "16") (pinfunction "VS_16") (pintype "bidirectional"))
      (node (ref "IC12") (pin "30") (pinfunction "VSA_30") (pintype "bidirectional"))
      (node (ref "IC12") (pin "31") (pinfunction "VS_31") (pintype "bidirectional"))
      (node (ref "IC15") (pin "16") (pinfunction "VS_16") (pintype "bidirectional"))
      (node (ref "IC15") (pin "30") (pinfunction "VSA_30") (pintype "bidirectional"))
      (node (ref "IC15") (pin "31") (pinfunction "VS_31") (pintype "bidirectional"))
      (node (ref "IC2") (pin "16") (pinfunction "VS_16") (pintype "bidirectional"))
      (node (ref "IC2") (pin "30") (pinfunction "VSA_30") (pintype "bidirectional"))
      (node (ref "IC2") (pin "31") (pinfunction "VS_31") (pintype "bidirectional"))
      (node (ref "IC5") (pin "16") (pinfunction "VS_16") (pintype "bidirectional"))
      (node (ref "IC5") (pin "30") (pinfunction "VSA_30") (pintype "bidirectional"))
      (node (ref "IC5") (pin "31") (pinfunction "VS_31") (pintype "bidirectional"))
      (node (ref "R14") (pin "2") (pinfunction "2_2") (pintype "passive"))
      (node (ref "R15") (pin "2") (pinfunction "2_2") (pintype "passive"))
      (node (ref "R16") (pin "2") (pinfunction "2_2") (pintype "passive"))
      (node (ref "R19") (pin "2") (pinfunction "2_2") (pintype "passive"))
      (node (ref "R20") (pin "2") (pinfunction "2_2") (pintype "passive"))
      (node (ref "R21") (pin "2") (pinfunction "2_2") (pintype "passive"))
      (node (ref "R25") (pin "2") (pinfunction "2_2") (pintype "passive"))
      (node (ref "R45") (pin "1") (pinfunction "1_1") (pintype "passive"))
      (node (ref "R55") (pin "2") (pinfunction "2_2") (pintype "passive"))
      (node (ref "R56") (pin "2") (pinfunction "2_2") (pintype "passive"))
      (node (ref "R57") (pin "2") (pinfunction "2_2") (pintype "passive"))
      (node (ref "U10") (pin "4") (pinfunction "VIN_4") (pintype "power_in"))
      (node (ref "U6") (pin "4") (pinfunction "VIN_4") (pintype "power_in"))
      (node (ref "U8") (pin "36") (pinfunction "36_36") (pintype "passive"))
      (node (ref "U8") (pin "37") (pinfunction "37_37") (pintype "passive"))
      (node (ref "U8") (pin "38") (pinfunction "38_38") (pintype "passive"))
      (node (ref "U8") (pin "39") (pinfunction "39_39") (pintype "passive"))
      (node (ref "U8") (pin "40") (pinfunction "40_40") (pintype "passive"))
      (node (ref "X20") (pin "1") (pinfunction "1_1") (pintype "passive"))
      (node (ref "X20") (pin "2") (pinfunction "1_2") (pintype "passive"))
      (node (ref "X21") (pin "1") (pinfunction "1_1") (pintype "passive"))
      (node (ref "X3") (pin "1") (pinfunction "1_1") (pintype "passive"))
      (node (ref "X5") (pin "1") (pinfunction "S_1") (pintype "passive"))
      (node (ref "X6") (pin "1") (pinfunction "S_1") (pintype "passive"))
    )
    (net (code "219") (name "X_A1") (class "Default")
      (node (ref "IC1") (pin "34") (pinfunction "OA1_34") (pintype "bidirectional"))
      (node (ref "U8") (pin "8") (pinfunction "8_8") (pintype "passive"))
      (node (ref "X4") (pin "2") (pinfunction "S_2") (pintype "passive"))
    )
    (net (code "220") (name "X_A2") (class "Default")
      (node (ref "IC1") (pin "32") (pinfunction "OA2_32") (pintype "bidirectional"))
      (node (ref "U8") (pin "7") (pinfunction "7_7") (pintype "passive"))
      (node (ref "X4") (pin "1") (pinfunction "S_1") (pintype "passive"))
    )
    (net (code "221") (name "X_B1") (class "Default")
      (node (ref "IC1") (pin "13") (pinfunction "OB1_13") (pintype "bidirectional"))
      (node (ref "U8") (pin "6") (pinfunction "6_6") (pintype "passive"))
      (node (ref "X4") (pin "3") (pinfunction "S_3") (pintype "passive"))
    )
    (net (code "222") (name "X_B2") (class "Default")
      (node (ref "IC1") (pin "15") (pinfunction "OB2_15") (pintype "bidirectional"))
      (node (ref "U8") (pin "5") (pinfunction "5_5") (pintype "passive"))
      (node (ref "X4") (pin "4") (pinfunction "S_4") (pintype "passive"))
    )
    (net (code "223") (name "unconnected-(IC1-CSN_CFG3-Pad2)") (class "Default")
      (node (ref "IC1") (pin "2") (pinfunction "CSN_CFG3_2") (pintype "bidirectional"))
    )
    (net (code "224") (name "unconnected-(IC1-ENCN_DCO-Pad17)") (class "Default")
      (node (ref "IC1") (pin "17") (pinfunction "ENCN_DCO_17") (pintype "bidirectional"))
    )
    (net (code "225") (name "unconnected-(IC1-SD_MODE-Pad9)") (class "Default")
      (node (ref "IC1") (pin "9") (pinfunction "SD_MODE_9") (pintype "bidirectional"))
    )
    (net (code "226") (name "unconnected-(IC1-SWP_DIAG1-Pad21)") (class "Default")
      (node (ref "IC1") (pin "21") (pinfunction "SWP_DIAG1_21") (pintype "bidirectional"))
    )
    (net (code "227") (name "unconnected-(IC2-CSN_CFG3-Pad2)") (class "Default")
      (node (ref "IC2") (pin "2") (pinfunction "CSN_CFG3_2") (pintype "bidirectional"))
    )
    (net (code "228") (name "unconnected-(IC2-ENCN_DCO-Pad17)") (class "Default")
      (node (ref "IC2") (pin "17") (pinfunction "ENCN_DCO_17") (pintype "bidirectional"))
    )
    (net (code "229") (name "unconnected-(IC2-SD_MODE-Pad9)") (class "Default")
      (node (ref "IC2") (pin "9") (pinfunction "SD_MODE_9") (pintype "bidirectional"))
    )
    (net (code "230") (name "unconnected-(IC2-SWP_DIAG1-Pad21)") (class "Default")
      (node (ref "IC2") (pin "21") (pinfunction "SWP_DIAG1_21") (pintype "bidirectional"))
    )
    (net (code "231") (name "unconnected-(IC5-CSN_CFG3-Pad2)") (class "Default")
      (node (ref "IC5") (pin "2") (pinfunction "CSN_CFG3_2") (pintype "bidirectional"))
    )
    (net (code "232") (name "unconnected-(IC5-ENCN_DCO-Pad17)") (class "Default")
      (node (ref "IC5") (pin "17") (pinfunction "ENCN_DCO_17") (pintype "bidirectional"))
    )
    (net (code "233") (name "unconnected-(IC5-SD_MODE-Pad9)") (class "Default")
      (node (ref "IC5") (pin "9") (pinfunction "SD_MODE_9") (pintype "bidirectional"))
    )
    (net (code "234") (name "unconnected-(IC5-SWP_DIAG1-Pad21)") (class "Default")
      (node (ref "IC5") (pin "21") (pinfunction "SWP_DIAG1_21") (pintype "bidirectional"))
    )
    (net (code "235") (name "unconnected-(IC12-CSN_CFG3-Pad2)") (class "Default")
      (node (ref "IC12") (pin "2") (pinfunction "CSN_CFG3_2") (pintype "bidirectional"))
    )
    (net (code "236") (name "unconnected-(IC12-ENCN_DCO-Pad17)") (class "Default")
      (node (ref "IC12") (pin "17") (pinfunction "ENCN_DCO_17") (pintype "bidirectional"))
    )
    (net (code "237") (name "unconnected-(IC12-SD_MODE-Pad9)") (class "Default")
      (node (ref "IC12") (pin "9") (pinfunction "SD_MODE_9") (pintype "bidirectional"))
    )
    (net (code "238") (name "unconnected-(IC12-SWP_DIAG1-Pad21)") (class "Default")
      (node (ref "IC12") (pin "21") (pinfunction "SWP_DIAG1_21") (pintype "bidirectional"))
    )
    (net (code "239") (name "unconnected-(IC15-CSN_CFG3-Pad2)") (class "Default")
      (node (ref "IC15") (pin "2") (pinfunction "CSN_CFG3_2") (pintype "bidirectional"))
    )
    (net (code "240") (name "unconnected-(IC15-ENCN_DCO-Pad17)") (class "Default")
      (node (ref "IC15") (pin "17") (pinfunction "ENCN_DCO_17") (pintype "bidirectional"))
    )
    (net (code "241") (name "unconnected-(IC15-SD_MODE-Pad9)") (class "Default")
      (node (ref "IC15") (pin "9") (pinfunction "SD_MODE_9") (pintype "bidirectional"))
    )
    (net (code "242") (name "unconnected-(IC15-SWP_DIAG1-Pad21)") (class "Default")
      (node (ref "IC15") (pin "21") (pinfunction "SWP_DIAG1_21") (pintype "bidirectional"))
    )
    (net (code "243") (name "unconnected-(P8-Pad3)") (class "Default")
      (node (ref "P8") (pin "3") (pinfunction "3_3") (pintype "passive"))
    )
    (net (code "244") (name "unconnected-(P8-Pad4)") (class "Default")
      (node (ref "P8") (pin "4") (pinfunction "4_4") (pintype "passive"))
    )
    (net (code "245") (name "unconnected-(P8-Pad5)") (class "Default")
      (node (ref "P8") (pin "5") (pinfunction "5_5") (pintype "passive"))
    )
    (net (code "246") (name "unconnected-(P8-Pad6)") (class "Default")
      (node (ref "P8") (pin "6") (pinfunction "6_6") (pintype "passive"))
    )
    (net (code "247") (name "unconnected-(P8-Pad7)") (class "Default")
      (node (ref "P8") (pin "7") (pinfunction "7_7") (pintype "passive"))
    )
    (net (code "248") (name "unconnected-(P8-Pad20)") (class "Default")
      (node (ref "P8") (pin "20") (pinfunction "20_20") (pintype "passive"))
    )
    (net (code "249") (name "unconnected-(P8-Pad21)") (class "Default")
      (node (ref "P8") (pin "21") (pinfunction "21_21") (pintype "passive"))
    )
    (net (code "250") (name "unconnected-(P8-Pad22)") (class "Default")
      (node (ref "P8") (pin "22") (pinfunction "22_22") (pintype "passive"))
    )
    (net (code "251") (name "unconnected-(P8-Pad23)") (class "Default")
      (node (ref "P8") (pin "23") (pinfunction "23_23") (pintype "passive"))
    )
    (net (code "252") (name "unconnected-(P8-Pad24)") (class "Default")
      (node (ref "P8") (pin "24") (pinfunction "24_24") (pintype "passive"))
    )
    (net (code "253") (name "unconnected-(P8-Pad25)") (class "Default")
      (node (ref "P8") (pin "25") (pinfunction "25_25") (pintype "passive"))
    )
    (net (code "254") (name "unconnected-(P8-Pad27)") (class "Default")
      (node (ref "P8") (pin "27") (pinfunction "27_27") (pintype "passive"))
    )
    (net (code "255") (name "unconnected-(P8-Pad28)") (class "Default")
      (node (ref "P8") (pin "28") (pinfunction "28_28") (pintype "passive"))
    )
    (net (code "256") (name "unconnected-(P8-Pad29)") (class "Default")
      (node (ref "P8") (pin "29") (pinfunction "29_29") (pintype "passive"))
    )
    (net (code "257") (name "unconnected-(P8-Pad30)") (class "Default")
      (node (ref "P8") (pin "30") (pinfunction "30_30") (pintype "passive"))
    )
    (net (code "258") (name "unconnected-(P8-Pad31)") (class "Default")
      (node (ref "P8") (pin "31") (pinfunction "31_31") (pintype "passive"))
    )
    (net (code "259") (name "unconnected-(P8-Pad32)") (class "Default")
      (node (ref "P8") (pin "32") (pinfunction "32_32") (pintype "passive"))
    )
    (net (code "260") (name "unconnected-(P8-Pad33)") (class "Default")
      (node (ref "P8") (pin "33") (pinfunction "33_33") (pintype "passive"))
    )
    (net (code "261") (name "unconnected-(P8-Pad34)") (class "Default")
      (node (ref "P8") (pin "34") (pinfunction "34_34") (pintype "passive"))
    )
    (net (code "262") (name "unconnected-(P8-Pad35)") (class "Default")
      (node (ref "P8") (pin "35") (pinfunction "35_35") (pintype "passive"))
    )
    (net (code "263") (name "unconnected-(P8-Pad36)") (class "Default")
      (node (ref "P8") (pin "36") (pinfunction "36_36") (pintype "passive"))
    )
    (net (code "264") (name "unconnected-(P8-Pad37)") (class "Default")
      (node (ref "P8") (pin "37") (pinfunction "37_37") (pintype "passive"))
    )
    (net (code "265") (name "unconnected-(P8-Pad38)") (class "Default")
      (node (ref "P8") (pin "38") (pinfunction "38_38") (pintype "passive"))
    )
    (net (code "266") (name "unconnected-(P8-Pad39)") (class "Default")
      (node (ref "P8") (pin "39") (pinfunction "39_39") (pintype "passive"))
    )
    (net (code "267") (name "unconnected-(P8-Pad40)") (class "Default")
      (node (ref "P8") (pin "40") (pinfunction "40_40") (pintype "passive"))
    )
    (net (code "268") (name "unconnected-(P8-Pad41)") (class "Default")
      (node (ref "P8") (pin "41") (pinfunction "41_41") (pintype "passive"))
    )
    (net (code "269") (name "unconnected-(P8-Pad42)") (class "Default")
      (node (ref "P8") (pin "42") (pinfunction "42_42") (pintype "passive"))
    )
    (net (code "270") (name "unconnected-(P8-Pad43)") (class "Default")
      (node (ref "P8") (pin "43") (pinfunction "43_43") (pintype "passive"))
    )
    (net (code "271") (name "unconnected-(P8-Pad44)") (class "Default")
      (node (ref "P8") (pin "44") (pinfunction "44_44") (pintype "passive"))
    )
    (net (code "272") (name "unconnected-(P8-Pad45)") (class "Default")
      (node (ref "P8") (pin "45") (pinfunction "45_45") (pintype "passive"))
    )
    (net (code "273") (name "unconnected-(P8-Pad46)") (class "Default")
      (node (ref "P8") (pin "46") (pinfunction "46_46") (pintype "passive"))
    )
    (net (code "274") (name "unconnected-(P9-Pad9)") (class "Default")
      (node (ref "P9") (pin "9") (pinfunction "9_9") (pintype "passive"))
    )
    (net (code "275") (name "unconnected-(P9-Pad10)") (class "Default")
      (node (ref "P9") (pin "10") (pinfunction "10_10") (pintype "passive"))
    )
    (net (code "276") (name "unconnected-(P9-Pad15)") (class "Default")
      (node (ref "P9") (pin "15") (pinfunction "15_15") (pintype "passive"))
    )
    (net (code "277") (name "unconnected-(P9-Pad17)") (class "Default")
      (node (ref "P9") (pin "17") (pinfunction "17_17") (pintype "passive"))
    )
    (net (code "278") (name "unconnected-(P9-Pad21)") (class "Default")
      (node (ref "P9") (pin "21") (pinfunction "21_21") (pintype "passive"))
    )
    (net (code "279") (name "unconnected-(P9-Pad26)") (class "Default")
      (node (ref "P9") (pin "26") (pinfunction "26_26") (pintype "passive"))
    )
    (net (code "280") (name "unconnected-(P9-Pad27)") (class "Default")
      (node (ref "P9") (pin "27") (pinfunction "27_27") (pintype "passive"))
    )
    (net (code "281") (name "unconnected-(P9-Pad29)") (class "Default")
      (node (ref "P9") (pin "29") (pinfunction "29_29") (pintype "passive"))
    )
    (net (code "282") (name "unconnected-(P9-Pad34)") (class "Default")
      (node (ref "P9") (pin "34") (pinfunction "34_34") (pintype "passive"))
    )
    (net (code "283") (name "unconnected-(P9-Pad37)") (class "Default")
      (node (ref "P9") (pin "37") (pinfunction "37_37") (pintype "passive"))
    )
    (net (code "284") (name "unconnected-(P9-Pad38)") (class "Default")
      (node (ref "P9") (pin "38") (pinfunction "38_38") (pintype "passive"))
    )
    (net (code "285") (name "unconnected-(P9-Pad39)") (class "Default")
      (node (ref "P9") (pin "39") (pinfunction "39_39") (pintype "passive"))
    )
    (net (code "286") (name "unconnected-(P9-Pad40)") (class "Default")
      (node (ref "P9") (pin "40") (pinfunction "40_40") (pintype "passive"))
    )
    (net (code "287") (name "unconnected-(U5-QH_2-Pad9)") (class "Default")
      (node (ref "U5") (pin "9") (pinfunction "QH_2_9") (pintype "output"))
    )
    (net (code "288") (name "unconnected-(U6-EN-Pad9)") (class "Default")
      (node (ref "U6") (pin "9") (pinfunction "EN_9") (pintype "input"))
    )
    (net (code "289") (name "unconnected-(U8-Pad1)") (class "Default")
      (node (ref "U8") (pin "1") (pinfunction "1_1") (pintype "passive"))
    )
    (net (code "290") (name "unconnected-(U8-Pad2)") (class "Default")
      (node (ref "U8") (pin "2") (pinfunction "2_2") (pintype "passive"))
    )
    (net (code "291") (name "unconnected-(U8-Pad29)") (class "Default")
      (node (ref "U8") (pin "29") (pinfunction "29_29") (pintype "passive"))
    )
    (net (code "292") (name "unconnected-(U10-EN-Pad9)") (class "Default")
      (node (ref "U10") (pin "9") (pinfunction "EN_9") (pintype "input"))
    )
    (net (code "293") (name "unconnected-(U11-EXTCLK-Pad25)") (class "Default")
      (node (ref "U11") (pin "25") (pinfunction "EXTCLK_25") (pintype "input"))
    )
    (net (code "294") (name "unconnected-(U11-LED6-Pad12)") (class "Default")
      (node (ref "U11") (pin "12") (pinfunction "LED6_12") (pintype "output"))
    )
    (net (code "295") (name "unconnected-(U18-~{WC}-Pad7)") (class "Default")
      (node (ref "U18") (pin "7") (pinfunction "~{WC}_7") (pintype "no_connect"))
    )
    (net (code "296") (name "unconnected-(U19-NC-Pad16)") (class "Default")
      (node (ref "U19") (pin "16") (pinfunction "NC_16") (pintype "no_connect"))
    )
    (net (code "297") (name "unconnected-(U19-NC_2-Pad13)") (class "Default")
      (node (ref "U19") (pin "13") (pinfunction "NC_2_13") (pintype "no_connect"))
    )
  )
)
